# UCirKitBreadboardTop-08231908.net
KiCad netlist of a schematic drawn in EAGLE
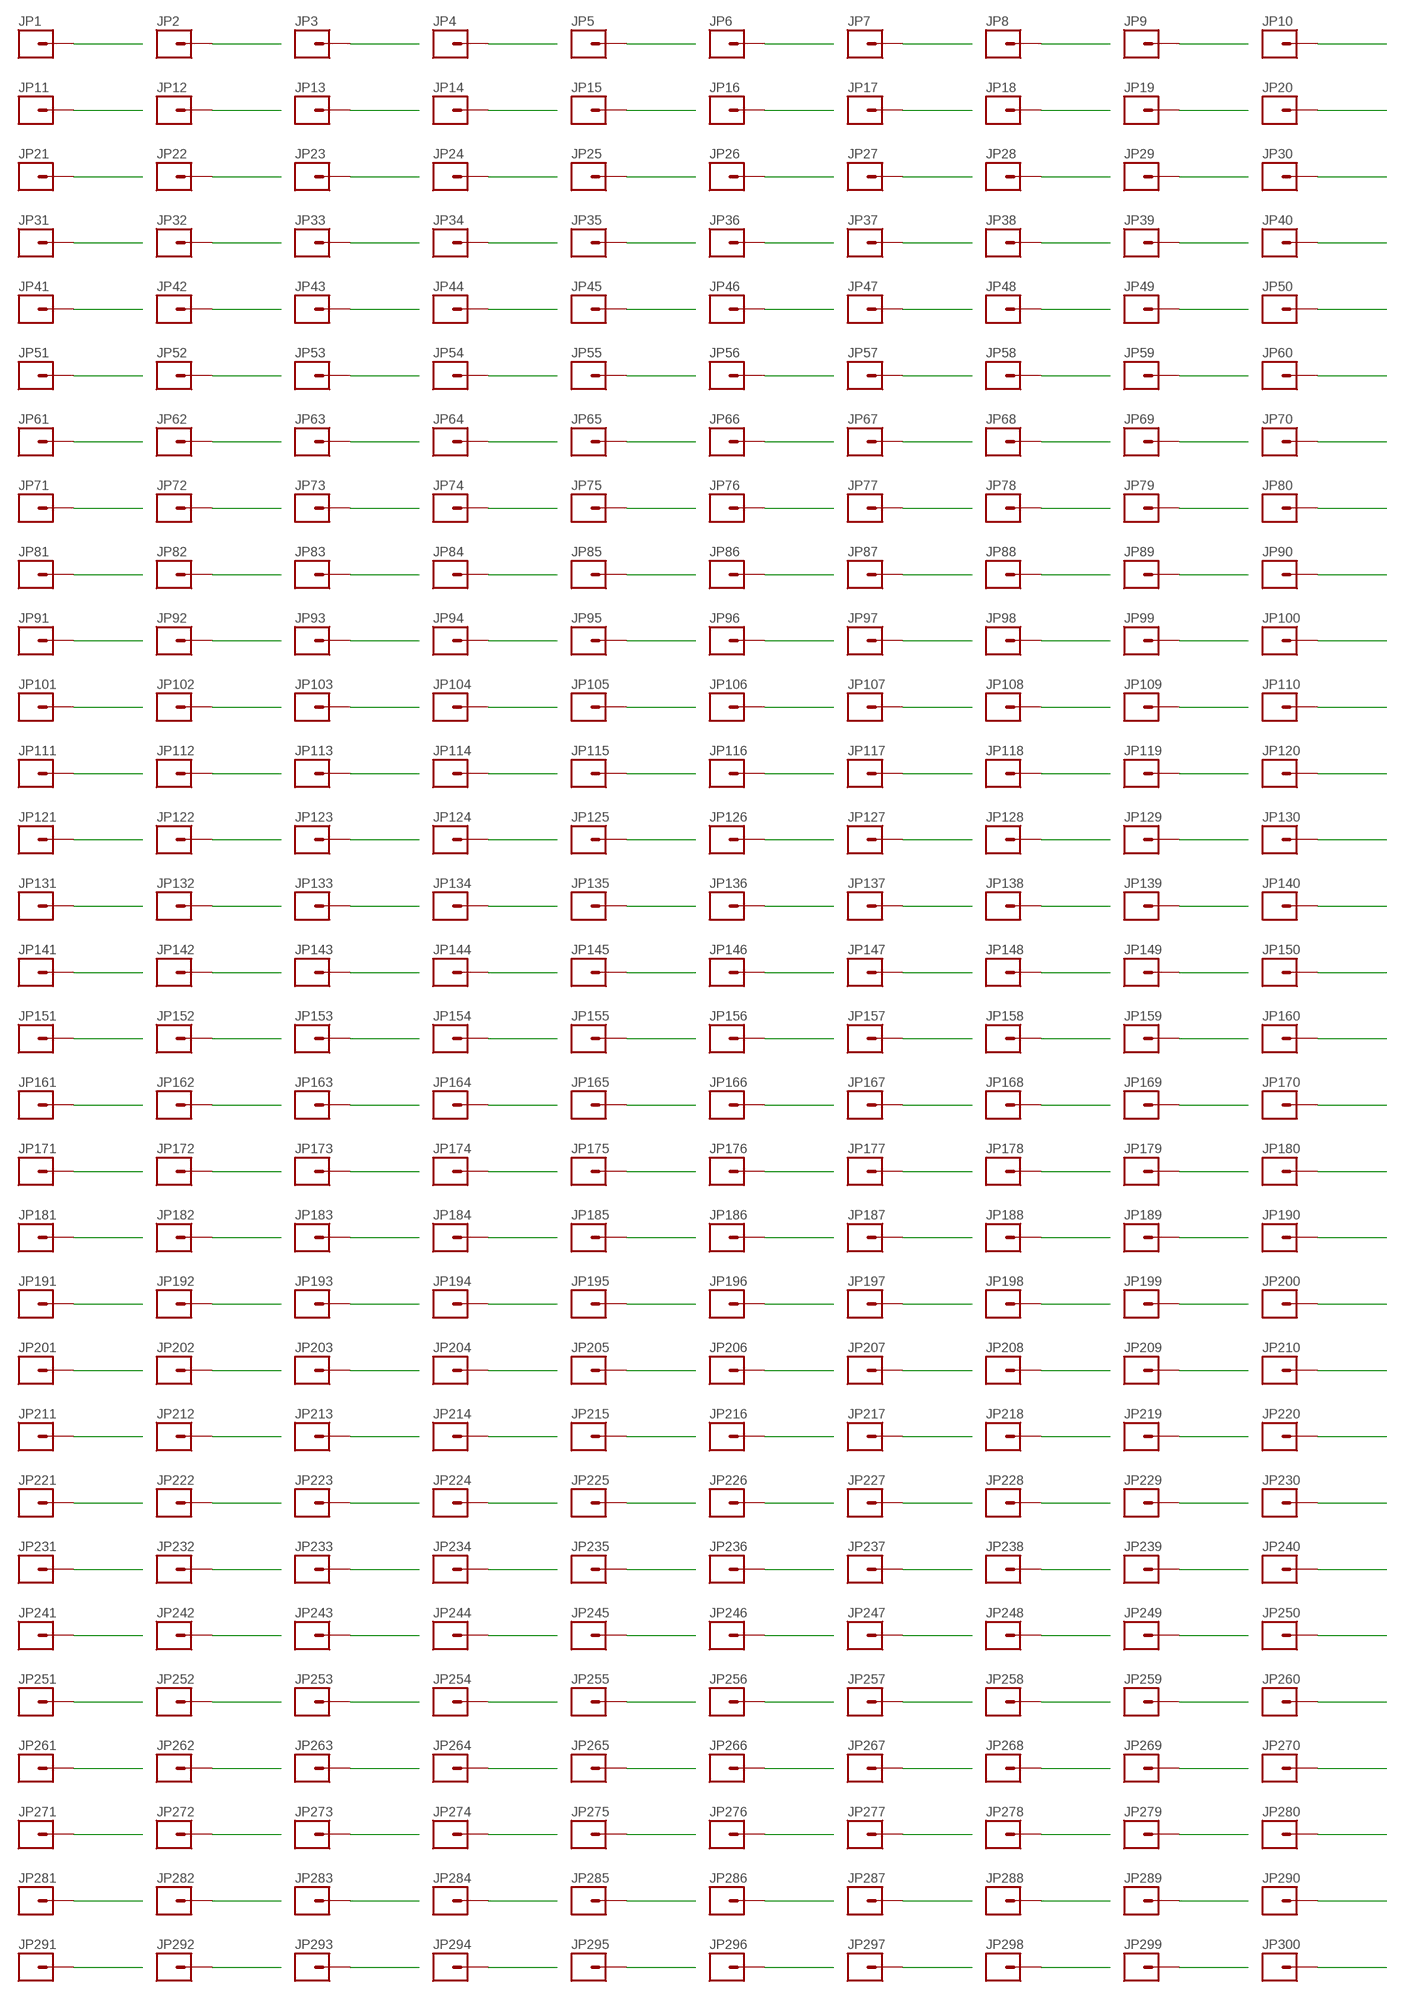
[diagram p0: schematic, sheet 1, part 1 of 2]
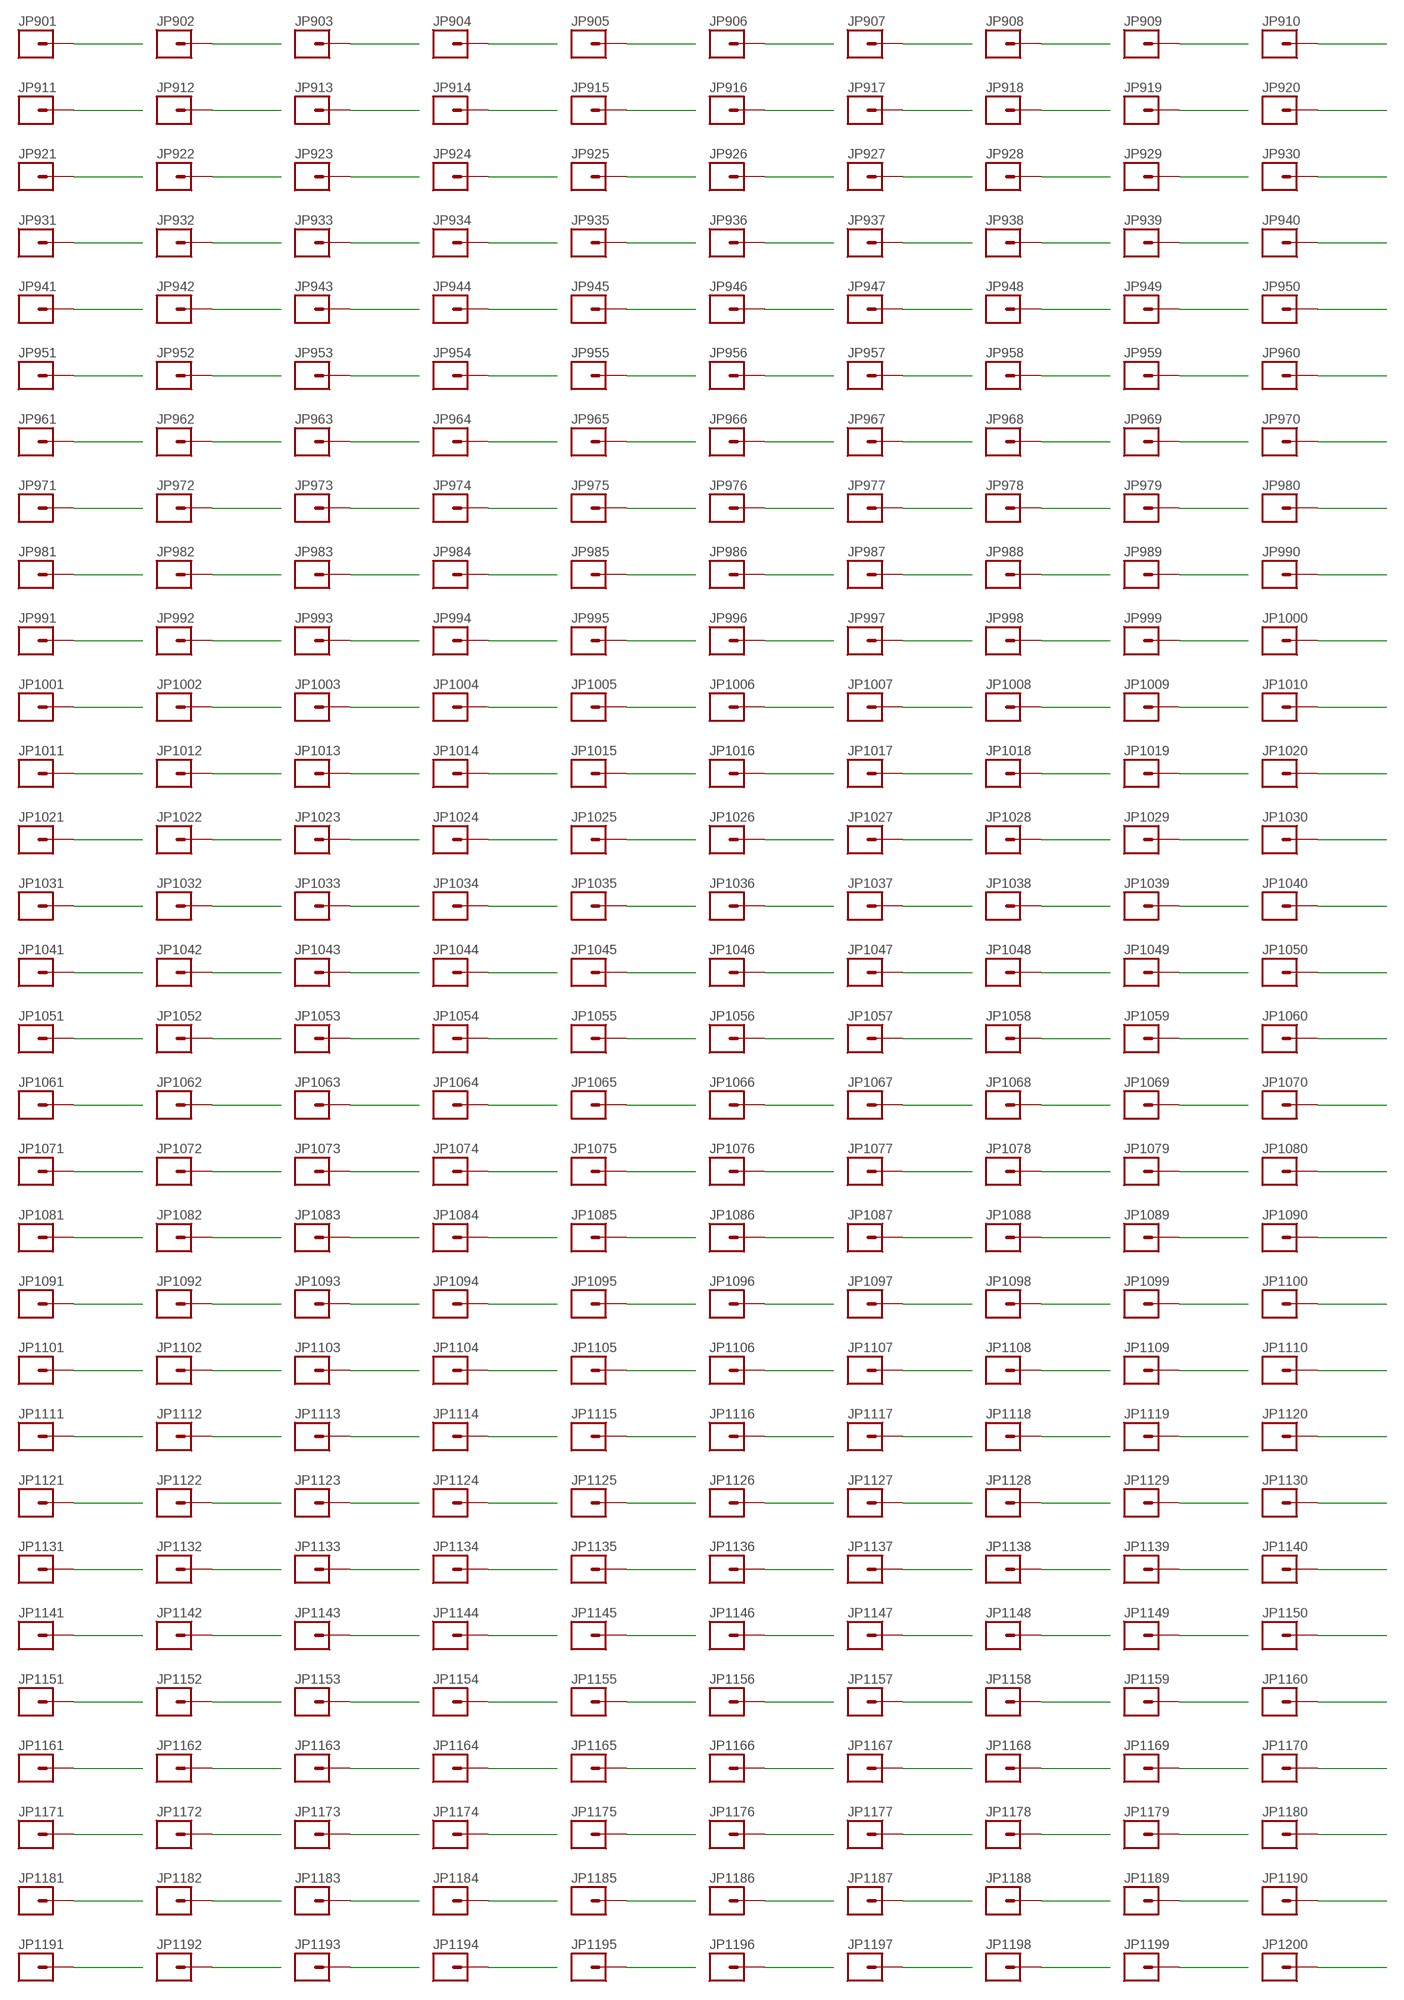
[diagram p1: schematic, sheet 1, part 2 of 2]

(export (version "E")
  (design (tool "Eeschema 10.0.6"))
  (components
    (comp (ref "JP1")
      (value "M01PTH_WITHOUT_TEXT")
      (footprint "eagle-import:1X01_WITHOUT_TEXT")
      (libsource (lib "eagle-import") (part "M01PTH_WITHOUT_TEXT"))
    )
    (comp (ref "JP2")
      (value "M01PTH_WITHOUT_TEXT")
      (footprint "eagle-import:1X01_WITHOUT_TEXT")
      (libsource (lib "eagle-import") (part "M01PTH_WITHOUT_TEXT"))
    )
    (comp (ref "JP3")
      (value "M01PTH_WITHOUT_TEXT")
      (footprint "eagle-import:1X01_WITHOUT_TEXT")
      (libsource (lib "eagle-import") (part "M01PTH_WITHOUT_TEXT"))
    )
    (comp (ref "JP4")
      (value "M01PTH_WITHOUT_TEXT")
      (footprint "eagle-import:1X01_WITHOUT_TEXT")
      (libsource (lib "eagle-import") (part "M01PTH_WITHOUT_TEXT"))
    )
    (comp (ref "JP5")
      (value "M01PTH_WITHOUT_TEXT")
      (footprint "eagle-import:1X01_WITHOUT_TEXT")
      (libsource (lib "eagle-import") (part "M01PTH_WITHOUT_TEXT"))
    )
    (comp (ref "JP6")
      (value "M01PTH_WITHOUT_TEXT")
      (footprint "eagle-import:1X01_WITHOUT_TEXT")
      (libsource (lib "eagle-import") (part "M01PTH_WITHOUT_TEXT"))
    )
    (comp (ref "JP7")
      (value "M01PTH_WITHOUT_TEXT")
      (footprint "eagle-import:1X01_WITHOUT_TEXT")
      (libsource (lib "eagle-import") (part "M01PTH_WITHOUT_TEXT"))
    )
    (comp (ref "JP8")
      (value "M01PTH_WITHOUT_TEXT")
      (footprint "eagle-import:1X01_WITHOUT_TEXT")
      (libsource (lib "eagle-import") (part "M01PTH_WITHOUT_TEXT"))
    )
    (comp (ref "JP9")
      (value "M01PTH_WITHOUT_TEXT")
      (footprint "eagle-import:1X01_WITHOUT_TEXT")
      (libsource (lib "eagle-import") (part "M01PTH_WITHOUT_TEXT"))
    )
    (comp (ref "JP10")
      (value "M01PTH_WITHOUT_TEXT")
      (footprint "eagle-import:1X01_WITHOUT_TEXT")
      (libsource (lib "eagle-import") (part "M01PTH_WITHOUT_TEXT"))
    )
    (comp (ref "JP11")
      (value "M01PTH_WITHOUT_TEXT")
      (footprint "eagle-import:1X01_WITHOUT_TEXT")
      (libsource (lib "eagle-import") (part "M01PTH_WITHOUT_TEXT"))
    )
    (comp (ref "JP12")
      (value "M01PTH_WITHOUT_TEXT")
      (footprint "eagle-import:1X01_WITHOUT_TEXT")
      (libsource (lib "eagle-import") (part "M01PTH_WITHOUT_TEXT"))
    )
    (comp (ref "JP13")
      (value "M01PTH_WITHOUT_TEXT")
      (footprint "eagle-import:1X01_WITHOUT_TEXT")
      (libsource (lib "eagle-import") (part "M01PTH_WITHOUT_TEXT"))
    )
    (comp (ref "JP14")
      (value "M01PTH_WITHOUT_TEXT")
      (footprint "eagle-import:1X01_WITHOUT_TEXT")
      (libsource (lib "eagle-import") (part "M01PTH_WITHOUT_TEXT"))
    )
    (comp (ref "JP15")
      (value "M01PTH_WITHOUT_TEXT")
      (footprint "eagle-import:1X01_WITHOUT_TEXT")
      (libsource (lib "eagle-import") (part "M01PTH_WITHOUT_TEXT"))
    )
    (comp (ref "JP16")
      (value "M01PTH_WITHOUT_TEXT")
      (footprint "eagle-import:1X01_WITHOUT_TEXT")
      (libsource (lib "eagle-import") (part "M01PTH_WITHOUT_TEXT"))
    )
    (comp (ref "JP17")
      (value "M01PTH_WITHOUT_TEXT")
      (footprint "eagle-import:1X01_WITHOUT_TEXT")
      (libsource (lib "eagle-import") (part "M01PTH_WITHOUT_TEXT"))
    )
    (comp (ref "JP18")
      (value "M01PTH_WITHOUT_TEXT")
      (footprint "eagle-import:1X01_WITHOUT_TEXT")
      (libsource (lib "eagle-import") (part "M01PTH_WITHOUT_TEXT"))
    )
    (comp (ref "JP19")
      (value "M01PTH_WITHOUT_TEXT")
      (footprint "eagle-import:1X01_WITHOUT_TEXT")
      (libsource (lib "eagle-import") (part "M01PTH_WITHOUT_TEXT"))
    )
    (comp (ref "JP20")
      (value "M01PTH_WITHOUT_TEXT")
      (footprint "eagle-import:1X01_WITHOUT_TEXT")
      (libsource (lib "eagle-import") (part "M01PTH_WITHOUT_TEXT"))
    )
    (comp (ref "JP21")
      (value "M01PTH_WITHOUT_TEXT")
      (footprint "eagle-import:1X01_WITHOUT_TEXT")
      (libsource (lib "eagle-import") (part "M01PTH_WITHOUT_TEXT"))
    )
    (comp (ref "JP22")
      (value "M01PTH_WITHOUT_TEXT")
      (footprint "eagle-import:1X01_WITHOUT_TEXT")
      (libsource (lib "eagle-import") (part "M01PTH_WITHOUT_TEXT"))
    )
    (comp (ref "JP23")
      (value "M01PTH_WITHOUT_TEXT")
      (footprint "eagle-import:1X01_WITHOUT_TEXT")
      (libsource (lib "eagle-import") (part "M01PTH_WITHOUT_TEXT"))
    )
    (comp (ref "JP24")
      (value "M01PTH_WITHOUT_TEXT")
      (footprint "eagle-import:1X01_WITHOUT_TEXT")
      (libsource (lib "eagle-import") (part "M01PTH_WITHOUT_TEXT"))
    )
    (comp (ref "JP25")
      (value "M01PTH_WITHOUT_TEXT")
      (footprint "eagle-import:1X01_WITHOUT_TEXT")
      (libsource (lib "eagle-import") (part "M01PTH_WITHOUT_TEXT"))
    )
    (comp (ref "JP26")
      (value "M01PTH_WITHOUT_TEXT")
      (footprint "eagle-import:1X01_WITHOUT_TEXT")
      (libsource (lib "eagle-import") (part "M01PTH_WITHOUT_TEXT"))
    )
    (comp (ref "JP27")
      (value "M01PTH_WITHOUT_TEXT")
      (footprint "eagle-import:1X01_WITHOUT_TEXT")
      (libsource (lib "eagle-import") (part "M01PTH_WITHOUT_TEXT"))
    )
    (comp (ref "JP28")
      (value "M01PTH_WITHOUT_TEXT")
      (footprint "eagle-import:1X01_WITHOUT_TEXT")
      (libsource (lib "eagle-import") (part "M01PTH_WITHOUT_TEXT"))
    )
    (comp (ref "JP29")
      (value "M01PTH_WITHOUT_TEXT")
      (footprint "eagle-import:1X01_WITHOUT_TEXT")
      (libsource (lib "eagle-import") (part "M01PTH_WITHOUT_TEXT"))
    )
    (comp (ref "JP30")
      (value "M01PTH_WITHOUT_TEXT")
      (footprint "eagle-import:1X01_WITHOUT_TEXT")
      (libsource (lib "eagle-import") (part "M01PTH_WITHOUT_TEXT"))
    )
    (comp (ref "JP31")
      (value "M01PTH_WITHOUT_TEXT")
      (footprint "eagle-import:1X01_WITHOUT_TEXT")
      (libsource (lib "eagle-import") (part "M01PTH_WITHOUT_TEXT"))
    )
    (comp (ref "JP32")
      (value "M01PTH_WITHOUT_TEXT")
      (footprint "eagle-import:1X01_WITHOUT_TEXT")
      (libsource (lib "eagle-import") (part "M01PTH_WITHOUT_TEXT"))
    )
    (comp (ref "JP33")
      (value "M01PTH_WITHOUT_TEXT")
      (footprint "eagle-import:1X01_WITHOUT_TEXT")
      (libsource (lib "eagle-import") (part "M01PTH_WITHOUT_TEXT"))
    )
    (comp (ref "JP34")
      (value "M01PTH_WITHOUT_TEXT")
      (footprint "eagle-import:1X01_WITHOUT_TEXT")
      (libsource (lib "eagle-import") (part "M01PTH_WITHOUT_TEXT"))
    )
    (comp (ref "JP35")
      (value "M01PTH_WITHOUT_TEXT")
      (footprint "eagle-import:1X01_WITHOUT_TEXT")
      (libsource (lib "eagle-import") (part "M01PTH_WITHOUT_TEXT"))
    )
    (comp (ref "JP36")
      (value "M01PTH_WITHOUT_TEXT")
      (footprint "eagle-import:1X01_WITHOUT_TEXT")
      (libsource (lib "eagle-import") (part "M01PTH_WITHOUT_TEXT"))
    )
    (comp (ref "JP37")
      (value "M01PTH_WITHOUT_TEXT")
      (footprint "eagle-import:1X01_WITHOUT_TEXT")
      (libsource (lib "eagle-import") (part "M01PTH_WITHOUT_TEXT"))
    )
    (comp (ref "JP38")
      (value "M01PTH_WITHOUT_TEXT")
      (footprint "eagle-import:1X01_WITHOUT_TEXT")
      (libsource (lib "eagle-import") (part "M01PTH_WITHOUT_TEXT"))
    )
    (comp (ref "JP39")
      (value "M01PTH_WITHOUT_TEXT")
      (footprint "eagle-import:1X01_WITHOUT_TEXT")
      (libsource (lib "eagle-import") (part "M01PTH_WITHOUT_TEXT"))
    )
    (comp (ref "JP40")
      (value "M01PTH_WITHOUT_TEXT")
      (footprint "eagle-import:1X01_WITHOUT_TEXT")
      (libsource (lib "eagle-import") (part "M01PTH_WITHOUT_TEXT"))
    )
    (comp (ref "JP41")
      (value "M01PTH_WITHOUT_TEXT")
      (footprint "eagle-import:1X01_WITHOUT_TEXT")
      (libsource (lib "eagle-import") (part "M01PTH_WITHOUT_TEXT"))
    )
    (comp (ref "JP42")
      (value "M01PTH_WITHOUT_TEXT")
      (footprint "eagle-import:1X01_WITHOUT_TEXT")
      (libsource (lib "eagle-import") (part "M01PTH_WITHOUT_TEXT"))
    )
    (comp (ref "JP43")
      (value "M01PTH_WITHOUT_TEXT")
      (footprint "eagle-import:1X01_WITHOUT_TEXT")
      (libsource (lib "eagle-import") (part "M01PTH_WITHOUT_TEXT"))
    )
    (comp (ref "JP44")
      (value "M01PTH_WITHOUT_TEXT")
      (footprint "eagle-import:1X01_WITHOUT_TEXT")
      (libsource (lib "eagle-import") (part "M01PTH_WITHOUT_TEXT"))
    )
    (comp (ref "JP45")
      (value "M01PTH_WITHOUT_TEXT")
      (footprint "eagle-import:1X01_WITHOUT_TEXT")
      (libsource (lib "eagle-import") (part "M01PTH_WITHOUT_TEXT"))
    )
    (comp (ref "JP46")
      (value "M01PTH_WITHOUT_TEXT")
      (footprint "eagle-import:1X01_WITHOUT_TEXT")
      (libsource (lib "eagle-import") (part "M01PTH_WITHOUT_TEXT"))
    )
    (comp (ref "JP47")
      (value "M01PTH_WITHOUT_TEXT")
      (footprint "eagle-import:1X01_WITHOUT_TEXT")
      (libsource (lib "eagle-import") (part "M01PTH_WITHOUT_TEXT"))
    )
    (comp (ref "JP48")
      (value "M01PTH_WITHOUT_TEXT")
      (footprint "eagle-import:1X01_WITHOUT_TEXT")
      (libsource (lib "eagle-import") (part "M01PTH_WITHOUT_TEXT"))
    )
    (comp (ref "JP49")
      (value "M01PTH_WITHOUT_TEXT")
      (footprint "eagle-import:1X01_WITHOUT_TEXT")
      (libsource (lib "eagle-import") (part "M01PTH_WITHOUT_TEXT"))
    )
    (comp (ref "JP50")
      (value "M01PTH_WITHOUT_TEXT")
      (footprint "eagle-import:1X01_WITHOUT_TEXT")
      (libsource (lib "eagle-import") (part "M01PTH_WITHOUT_TEXT"))
    )
    (comp (ref "JP51")
      (value "M01PTH_WITHOUT_TEXT")
      (footprint "eagle-import:1X01_WITHOUT_TEXT")
      (libsource (lib "eagle-import") (part "M01PTH_WITHOUT_TEXT"))
    )
    (comp (ref "JP52")
      (value "M01PTH_WITHOUT_TEXT")
      (footprint "eagle-import:1X01_WITHOUT_TEXT")
      (libsource (lib "eagle-import") (part "M01PTH_WITHOUT_TEXT"))
    )
    (comp (ref "JP53")
      (value "M01PTH_WITHOUT_TEXT")
      (footprint "eagle-import:1X01_WITHOUT_TEXT")
      (libsource (lib "eagle-import") (part "M01PTH_WITHOUT_TEXT"))
    )
    (comp (ref "JP54")
      (value "M01PTH_WITHOUT_TEXT")
      (footprint "eagle-import:1X01_WITHOUT_TEXT")
      (libsource (lib "eagle-import") (part "M01PTH_WITHOUT_TEXT"))
    )
    (comp (ref "JP55")
      (value "M01PTH_WITHOUT_TEXT")
      (footprint "eagle-import:1X01_WITHOUT_TEXT")
      (libsource (lib "eagle-import") (part "M01PTH_WITHOUT_TEXT"))
    )
    (comp (ref "JP56")
      (value "M01PTH_WITHOUT_TEXT")
      (footprint "eagle-import:1X01_WITHOUT_TEXT")
      (libsource (lib "eagle-import") (part "M01PTH_WITHOUT_TEXT"))
    )
    (comp (ref "JP57")
      (value "M01PTH_WITHOUT_TEXT")
      (footprint "eagle-import:1X01_WITHOUT_TEXT")
      (libsource (lib "eagle-import") (part "M01PTH_WITHOUT_TEXT"))
    )
    (comp (ref "JP58")
      (value "M01PTH_WITHOUT_TEXT")
      (footprint "eagle-import:1X01_WITHOUT_TEXT")
      (libsource (lib "eagle-import") (part "M01PTH_WITHOUT_TEXT"))
    )
    (comp (ref "JP59")
      (value "M01PTH_WITHOUT_TEXT")
      (footprint "eagle-import:1X01_WITHOUT_TEXT")
      (libsource (lib "eagle-import") (part "M01PTH_WITHOUT_TEXT"))
    )
    (comp (ref "JP60")
      (value "M01PTH_WITHOUT_TEXT")
      (footprint "eagle-import:1X01_WITHOUT_TEXT")
      (libsource (lib "eagle-import") (part "M01PTH_WITHOUT_TEXT"))
    )
    (comp (ref "JP61")
      (value "M01PTH_WITHOUT_TEXT")
      (footprint "eagle-import:1X01_WITHOUT_TEXT")
      (libsource (lib "eagle-import") (part "M01PTH_WITHOUT_TEXT"))
    )
    (comp (ref "JP62")
      (value "M01PTH_WITHOUT_TEXT")
      (footprint "eagle-import:1X01_WITHOUT_TEXT")
      (libsource (lib "eagle-import") (part "M01PTH_WITHOUT_TEXT"))
    )
    (comp (ref "JP63")
      (value "M01PTH_WITHOUT_TEXT")
      (footprint "eagle-import:1X01_WITHOUT_TEXT")
      (libsource (lib "eagle-import") (part "M01PTH_WITHOUT_TEXT"))
    )
    (comp (ref "JP64")
      (value "M01PTH_WITHOUT_TEXT")
      (footprint "eagle-import:1X01_WITHOUT_TEXT")
      (libsource (lib "eagle-import") (part "M01PTH_WITHOUT_TEXT"))
    )
    (comp (ref "JP65")
      (value "M01PTH_WITHOUT_TEXT")
      (footprint "eagle-import:1X01_WITHOUT_TEXT")
      (libsource (lib "eagle-import") (part "M01PTH_WITHOUT_TEXT"))
    )
    (comp (ref "JP66")
      (value "M01PTH_WITHOUT_TEXT")
      (footprint "eagle-import:1X01_WITHOUT_TEXT")
      (libsource (lib "eagle-import") (part "M01PTH_WITHOUT_TEXT"))
    )
    (comp (ref "JP67")
      (value "M01PTH_WITHOUT_TEXT")
      (footprint "eagle-import:1X01_WITHOUT_TEXT")
      (libsource (lib "eagle-import") (part "M01PTH_WITHOUT_TEXT"))
    )
    (comp (ref "JP68")
      (value "M01PTH_WITHOUT_TEXT")
      (footprint "eagle-import:1X01_WITHOUT_TEXT")
      (libsource (lib "eagle-import") (part "M01PTH_WITHOUT_TEXT"))
    )
    (comp (ref "JP69")
      (value "M01PTH_WITHOUT_TEXT")
      (footprint "eagle-import:1X01_WITHOUT_TEXT")
      (libsource (lib "eagle-import") (part "M01PTH_WITHOUT_TEXT"))
    )
    (comp (ref "JP70")
      (value "M01PTH_WITHOUT_TEXT")
      (footprint "eagle-import:1X01_WITHOUT_TEXT")
      (libsource (lib "eagle-import") (part "M01PTH_WITHOUT_TEXT"))
    )
    (comp (ref "JP71")
      (value "M01PTH_WITHOUT_TEXT")
      (footprint "eagle-import:1X01_WITHOUT_TEXT")
      (libsource (lib "eagle-import") (part "M01PTH_WITHOUT_TEXT"))
    )
    (comp (ref "JP72")
      (value "M01PTH_WITHOUT_TEXT")
      (footprint "eagle-import:1X01_WITHOUT_TEXT")
      (libsource (lib "eagle-import") (part "M01PTH_WITHOUT_TEXT"))
    )
    (comp (ref "JP73")
      (value "M01PTH_WITHOUT_TEXT")
      (footprint "eagle-import:1X01_WITHOUT_TEXT")
      (libsource (lib "eagle-import") (part "M01PTH_WITHOUT_TEXT"))
    )
    (comp (ref "JP74")
      (value "M01PTH_WITHOUT_TEXT")
      (footprint "eagle-import:1X01_WITHOUT_TEXT")
      (libsource (lib "eagle-import") (part "M01PTH_WITHOUT_TEXT"))
    )
    (comp (ref "JP75")
      (value "M01PTH_WITHOUT_TEXT")
      (footprint "eagle-import:1X01_WITHOUT_TEXT")
      (libsource (lib "eagle-import") (part "M01PTH_WITHOUT_TEXT"))
    )
    (comp (ref "JP76")
      (value "M01PTH_WITHOUT_TEXT")
      (footprint "eagle-import:1X01_WITHOUT_TEXT")
      (libsource (lib "eagle-import") (part "M01PTH_WITHOUT_TEXT"))
    )
    (comp (ref "JP77")
      (value "M01PTH_WITHOUT_TEXT")
      (footprint "eagle-import:1X01_WITHOUT_TEXT")
      (libsource (lib "eagle-import") (part "M01PTH_WITHOUT_TEXT"))
    )
    (comp (ref "JP78")
      (value "M01PTH_WITHOUT_TEXT")
      (footprint "eagle-import:1X01_WITHOUT_TEXT")
      (libsource (lib "eagle-import") (part "M01PTH_WITHOUT_TEXT"))
    )
    (comp (ref "JP79")
      (value "M01PTH_WITHOUT_TEXT")
      (footprint "eagle-import:1X01_WITHOUT_TEXT")
      (libsource (lib "eagle-import") (part "M01PTH_WITHOUT_TEXT"))
    )
    (comp (ref "JP80")
      (value "M01PTH_WITHOUT_TEXT")
      (footprint "eagle-import:1X01_WITHOUT_TEXT")
      (libsource (lib "eagle-import") (part "M01PTH_WITHOUT_TEXT"))
    )
    (comp (ref "JP81")
      (value "M01PTH_WITHOUT_TEXT")
      (footprint "eagle-import:1X01_WITHOUT_TEXT")
      (libsource (lib "eagle-import") (part "M01PTH_WITHOUT_TEXT"))
    )
    (comp (ref "JP82")
      (value "M01PTH_WITHOUT_TEXT")
      (footprint "eagle-import:1X01_WITHOUT_TEXT")
      (libsource (lib "eagle-import") (part "M01PTH_WITHOUT_TEXT"))
    )
    (comp (ref "JP83")
      (value "M01PTH_WITHOUT_TEXT")
      (footprint "eagle-import:1X01_WITHOUT_TEXT")
      (libsource (lib "eagle-import") (part "M01PTH_WITHOUT_TEXT"))
    )
    (comp (ref "JP84")
      (value "M01PTH_WITHOUT_TEXT")
      (footprint "eagle-import:1X01_WITHOUT_TEXT")
      (libsource (lib "eagle-import") (part "M01PTH_WITHOUT_TEXT"))
    )
    (comp (ref "JP85")
      (value "M01PTH_WITHOUT_TEXT")
      (footprint "eagle-import:1X01_WITHOUT_TEXT")
      (libsource (lib "eagle-import") (part "M01PTH_WITHOUT_TEXT"))
    )
    (comp (ref "JP86")
      (value "M01PTH_WITHOUT_TEXT")
      (footprint "eagle-import:1X01_WITHOUT_TEXT")
      (libsource (lib "eagle-import") (part "M01PTH_WITHOUT_TEXT"))
    )
    (comp (ref "JP87")
      (value "M01PTH_WITHOUT_TEXT")
      (footprint "eagle-import:1X01_WITHOUT_TEXT")
      (libsource (lib "eagle-import") (part "M01PTH_WITHOUT_TEXT"))
    )
    (comp (ref "JP88")
      (value "M01PTH_WITHOUT_TEXT")
      (footprint "eagle-import:1X01_WITHOUT_TEXT")
      (libsource (lib "eagle-import") (part "M01PTH_WITHOUT_TEXT"))
    )
    (comp (ref "JP89")
      (value "M01PTH_WITHOUT_TEXT")
      (footprint "eagle-import:1X01_WITHOUT_TEXT")
      (libsource (lib "eagle-import") (part "M01PTH_WITHOUT_TEXT"))
    )
    (comp (ref "JP90")
      (value "M01PTH_WITHOUT_TEXT")
      (footprint "eagle-import:1X01_WITHOUT_TEXT")
      (libsource (lib "eagle-import") (part "M01PTH_WITHOUT_TEXT"))
    )
    (comp (ref "JP91")
      (value "M01PTH_WITHOUT_TEXT")
      (footprint "eagle-import:1X01_WITHOUT_TEXT")
      (libsource (lib "eagle-import") (part "M01PTH_WITHOUT_TEXT"))
    )
    (comp (ref "JP92")
      (value "M01PTH_WITHOUT_TEXT")
      (footprint "eagle-import:1X01_WITHOUT_TEXT")
      (libsource (lib "eagle-import") (part "M01PTH_WITHOUT_TEXT"))
    )
    (comp (ref "JP93")
      (value "M01PTH_WITHOUT_TEXT")
      (footprint "eagle-import:1X01_WITHOUT_TEXT")
      (libsource (lib "eagle-import") (part "M01PTH_WITHOUT_TEXT"))
    )
    (comp (ref "JP94")
      (value "M01PTH_WITHOUT_TEXT")
      (footprint "eagle-import:1X01_WITHOUT_TEXT")
      (libsource (lib "eagle-import") (part "M01PTH_WITHOUT_TEXT"))
    )
    (comp (ref "JP95")
      (value "M01PTH_WITHOUT_TEXT")
      (footprint "eagle-import:1X01_WITHOUT_TEXT")
      (libsource (lib "eagle-import") (part "M01PTH_WITHOUT_TEXT"))
    )
    (comp (ref "JP96")
      (value "M01PTH_WITHOUT_TEXT")
      (footprint "eagle-import:1X01_WITHOUT_TEXT")
      (libsource (lib "eagle-import") (part "M01PTH_WITHOUT_TEXT"))
    )
    (comp (ref "JP97")
      (value "M01PTH_WITHOUT_TEXT")
      (footprint "eagle-import:1X01_WITHOUT_TEXT")
      (libsource (lib "eagle-import") (part "M01PTH_WITHOUT_TEXT"))
    )
    (comp (ref "JP98")
      (value "M01PTH_WITHOUT_TEXT")
      (footprint "eagle-import:1X01_WITHOUT_TEXT")
      (libsource (lib "eagle-import") (part "M01PTH_WITHOUT_TEXT"))
    )
    (comp (ref "JP99")
      (value "M01PTH_WITHOUT_TEXT")
      (footprint "eagle-import:1X01_WITHOUT_TEXT")
      (libsource (lib "eagle-import") (part "M01PTH_WITHOUT_TEXT"))
    )
    (comp (ref "JP100")
      (value "M01PTH_WITHOUT_TEXT")
      (footprint "eagle-import:1X01_WITHOUT_TEXT")
      (libsource (lib "eagle-import") (part "M01PTH_WITHOUT_TEXT"))
    )
    (comp (ref "JP101")
      (value "M01PTH_WITHOUT_TEXT")
      (footprint "eagle-import:1X01_WITHOUT_TEXT")
      (libsource (lib "eagle-import") (part "M01PTH_WITHOUT_TEXT"))
    )
    (comp (ref "JP102")
      (value "M01PTH_WITHOUT_TEXT")
      (footprint "eagle-import:1X01_WITHOUT_TEXT")
      (libsource (lib "eagle-import") (part "M01PTH_WITHOUT_TEXT"))
    )
    (comp (ref "JP103")
      (value "M01PTH_WITHOUT_TEXT")
      (footprint "eagle-import:1X01_WITHOUT_TEXT")
      (libsource (lib "eagle-import") (part "M01PTH_WITHOUT_TEXT"))
    )
    (comp (ref "JP104")
      (value "M01PTH_WITHOUT_TEXT")
      (footprint "eagle-import:1X01_WITHOUT_TEXT")
      (libsource (lib "eagle-import") (part "M01PTH_WITHOUT_TEXT"))
    )
    (comp (ref "JP105")
      (value "M01PTH_WITHOUT_TEXT")
      (footprint "eagle-import:1X01_WITHOUT_TEXT")
      (libsource (lib "eagle-import") (part "M01PTH_WITHOUT_TEXT"))
    )
    (comp (ref "JP106")
      (value "M01PTH_WITHOUT_TEXT")
      (footprint "eagle-import:1X01_WITHOUT_TEXT")
      (libsource (lib "eagle-import") (part "M01PTH_WITHOUT_TEXT"))
    )
    (comp (ref "JP107")
      (value "M01PTH_WITHOUT_TEXT")
      (footprint "eagle-import:1X01_WITHOUT_TEXT")
      (libsource (lib "eagle-import") (part "M01PTH_WITHOUT_TEXT"))
    )
    (comp (ref "JP108")
      (value "M01PTH_WITHOUT_TEXT")
      (footprint "eagle-import:1X01_WITHOUT_TEXT")
      (libsource (lib "eagle-import") (part "M01PTH_WITHOUT_TEXT"))
    )
    (comp (ref "JP109")
      (value "M01PTH_WITHOUT_TEXT")
      (footprint "eagle-import:1X01_WITHOUT_TEXT")
      (libsource (lib "eagle-import") (part "M01PTH_WITHOUT_TEXT"))
    )
    (comp (ref "JP110")
      (value "M01PTH_WITHOUT_TEXT")
      (footprint "eagle-import:1X01_WITHOUT_TEXT")
      (libsource (lib "eagle-import") (part "M01PTH_WITHOUT_TEXT"))
    )
    (comp (ref "JP111")
      (value "M01PTH_WITHOUT_TEXT")
      (footprint "eagle-import:1X01_WITHOUT_TEXT")
      (libsource (lib "eagle-import") (part "M01PTH_WITHOUT_TEXT"))
    )
    (comp (ref "JP112")
      (value "M01PTH_WITHOUT_TEXT")
      (footprint "eagle-import:1X01_WITHOUT_TEXT")
      (libsource (lib "eagle-import") (part "M01PTH_WITHOUT_TEXT"))
    )
    (comp (ref "JP113")
      (value "M01PTH_WITHOUT_TEXT")
      (footprint "eagle-import:1X01_WITHOUT_TEXT")
      (libsource (lib "eagle-import") (part "M01PTH_WITHOUT_TEXT"))
    )
    (comp (ref "JP114")
      (value "M01PTH_WITHOUT_TEXT")
      (footprint "eagle-import:1X01_WITHOUT_TEXT")
      (libsource (lib "eagle-import") (part "M01PTH_WITHOUT_TEXT"))
    )
    (comp (ref "JP115")
      (value "M01PTH_WITHOUT_TEXT")
      (footprint "eagle-import:1X01_WITHOUT_TEXT")
      (libsource (lib "eagle-import") (part "M01PTH_WITHOUT_TEXT"))
    )
    (comp (ref "JP116")
      (value "M01PTH_WITHOUT_TEXT")
      (footprint "eagle-import:1X01_WITHOUT_TEXT")
      (libsource (lib "eagle-import") (part "M01PTH_WITHOUT_TEXT"))
    )
    (comp (ref "JP117")
      (value "M01PTH_WITHOUT_TEXT")
      (footprint "eagle-import:1X01_WITHOUT_TEXT")
      (libsource (lib "eagle-import") (part "M01PTH_WITHOUT_TEXT"))
    )
    (comp (ref "JP118")
      (value "M01PTH_WITHOUT_TEXT")
      (footprint "eagle-import:1X01_WITHOUT_TEXT")
      (libsource (lib "eagle-import") (part "M01PTH_WITHOUT_TEXT"))
    )
    (comp (ref "JP119")
      (value "M01PTH_WITHOUT_TEXT")
      (footprint "eagle-import:1X01_WITHOUT_TEXT")
      (libsource (lib "eagle-import") (part "M01PTH_WITHOUT_TEXT"))
    )
    (comp (ref "JP120")
      (value "M01PTH_WITHOUT_TEXT")
      (footprint "eagle-import:1X01_WITHOUT_TEXT")
      (libsource (lib "eagle-import") (part "M01PTH_WITHOUT_TEXT"))
    )
    (comp (ref "JP121")
      (value "M01PTH_WITHOUT_TEXT")
      (footprint "eagle-import:1X01_WITHOUT_TEXT")
      (libsource (lib "eagle-import") (part "M01PTH_WITHOUT_TEXT"))
    )
    (comp (ref "JP122")
      (value "M01PTH_WITHOUT_TEXT")
      (footprint "eagle-import:1X01_WITHOUT_TEXT")
      (libsource (lib "eagle-import") (part "M01PTH_WITHOUT_TEXT"))
    )
    (comp (ref "JP123")
      (value "M01PTH_WITHOUT_TEXT")
      (footprint "eagle-import:1X01_WITHOUT_TEXT")
      (libsource (lib "eagle-import") (part "M01PTH_WITHOUT_TEXT"))
    )
    (comp (ref "JP124")
      (value "M01PTH_WITHOUT_TEXT")
      (footprint "eagle-import:1X01_WITHOUT_TEXT")
      (libsource (lib "eagle-import") (part "M01PTH_WITHOUT_TEXT"))
    )
    (comp (ref "JP125")
      (value "M01PTH_WITHOUT_TEXT")
      (footprint "eagle-import:1X01_WITHOUT_TEXT")
      (libsource (lib "eagle-import") (part "M01PTH_WITHOUT_TEXT"))
    )
    (comp (ref "JP126")
      (value "M01PTH_WITHOUT_TEXT")
      (footprint "eagle-import:1X01_WITHOUT_TEXT")
      (libsource (lib "eagle-import") (part "M01PTH_WITHOUT_TEXT"))
    )
    (comp (ref "JP127")
      (value "M01PTH_WITHOUT_TEXT")
      (footprint "eagle-import:1X01_WITHOUT_TEXT")
      (libsource (lib "eagle-import") (part "M01PTH_WITHOUT_TEXT"))
    )
    (comp (ref "JP128")
      (value "M01PTH_WITHOUT_TEXT")
      (footprint "eagle-import:1X01_WITHOUT_TEXT")
      (libsource (lib "eagle-import") (part "M01PTH_WITHOUT_TEXT"))
    )
    (comp (ref "JP129")
      (value "M01PTH_WITHOUT_TEXT")
      (footprint "eagle-import:1X01_WITHOUT_TEXT")
      (libsource (lib "eagle-import") (part "M01PTH_WITHOUT_TEXT"))
    )
    (comp (ref "JP130")
      (value "M01PTH_WITHOUT_TEXT")
      (footprint "eagle-import:1X01_WITHOUT_TEXT")
      (libsource (lib "eagle-import") (part "M01PTH_WITHOUT_TEXT"))
    )
    (comp (ref "JP131")
      (value "M01PTH_WITHOUT_TEXT")
      (footprint "eagle-import:1X01_WITHOUT_TEXT")
      (libsource (lib "eagle-import") (part "M01PTH_WITHOUT_TEXT"))
    )
    (comp (ref "JP132")
      (value "M01PTH_WITHOUT_TEXT")
      (footprint "eagle-import:1X01_WITHOUT_TEXT")
      (libsource (lib "eagle-import") (part "M01PTH_WITHOUT_TEXT"))
    )
    (comp (ref "JP133")
      (value "M01PTH_WITHOUT_TEXT")
      (footprint "eagle-import:1X01_WITHOUT_TEXT")
      (libsource (lib "eagle-import") (part "M01PTH_WITHOUT_TEXT"))
    )
    (comp (ref "JP134")
      (value "M01PTH_WITHOUT_TEXT")
      (footprint "eagle-import:1X01_WITHOUT_TEXT")
      (libsource (lib "eagle-import") (part "M01PTH_WITHOUT_TEXT"))
    )
    (comp (ref "JP135")
      (value "M01PTH_WITHOUT_TEXT")
      (footprint "eagle-import:1X01_WITHOUT_TEXT")
      (libsource (lib "eagle-import") (part "M01PTH_WITHOUT_TEXT"))
    )
    (comp (ref "JP136")
      (value "M01PTH_WITHOUT_TEXT")
      (footprint "eagle-import:1X01_WITHOUT_TEXT")
      (libsource (lib "eagle-import") (part "M01PTH_WITHOUT_TEXT"))
    )
    (comp (ref "JP137")
      (value "M01PTH_WITHOUT_TEXT")
      (footprint "eagle-import:1X01_WITHOUT_TEXT")
      (libsource (lib "eagle-import") (part "M01PTH_WITHOUT_TEXT"))
    )
    (comp (ref "JP138")
      (value "M01PTH_WITHOUT_TEXT")
      (footprint "eagle-import:1X01_WITHOUT_TEXT")
      (libsource (lib "eagle-import") (part "M01PTH_WITHOUT_TEXT"))
    )
    (comp (ref "JP139")
      (value "M01PTH_WITHOUT_TEXT")
      (footprint "eagle-import:1X01_WITHOUT_TEXT")
      (libsource (lib "eagle-import") (part "M01PTH_WITHOUT_TEXT"))
    )
    (comp (ref "JP140")
      (value "M01PTH_WITHOUT_TEXT")
      (footprint "eagle-import:1X01_WITHOUT_TEXT")
      (libsource (lib "eagle-import") (part "M01PTH_WITHOUT_TEXT"))
    )
    (comp (ref "JP141")
      (value "M01PTH_WITHOUT_TEXT")
      (footprint "eagle-import:1X01_WITHOUT_TEXT")
      (libsource (lib "eagle-import") (part "M01PTH_WITHOUT_TEXT"))
    )
    (comp (ref "JP142")
      (value "M01PTH_WITHOUT_TEXT")
      (footprint "eagle-import:1X01_WITHOUT_TEXT")
      (libsource (lib "eagle-import") (part "M01PTH_WITHOUT_TEXT"))
    )
    (comp (ref "JP143")
      (value "M01PTH_WITHOUT_TEXT")
      (footprint "eagle-import:1X01_WITHOUT_TEXT")
      (libsource (lib "eagle-import") (part "M01PTH_WITHOUT_TEXT"))
    )
    (comp (ref "JP144")
      (value "M01PTH_WITHOUT_TEXT")
      (footprint "eagle-import:1X01_WITHOUT_TEXT")
      (libsource (lib "eagle-import") (part "M01PTH_WITHOUT_TEXT"))
    )
    (comp (ref "JP145")
      (value "M01PTH_WITHOUT_TEXT")
      (footprint "eagle-import:1X01_WITHOUT_TEXT")
      (libsource (lib "eagle-import") (part "M01PTH_WITHOUT_TEXT"))
    )
    (comp (ref "JP146")
      (value "M01PTH_WITHOUT_TEXT")
      (footprint "eagle-import:1X01_WITHOUT_TEXT")
      (libsource (lib "eagle-import") (part "M01PTH_WITHOUT_TEXT"))
    )
    (comp (ref "JP147")
      (value "M01PTH_WITHOUT_TEXT")
      (footprint "eagle-import:1X01_WITHOUT_TEXT")
      (libsource (lib "eagle-import") (part "M01PTH_WITHOUT_TEXT"))
    )
    (comp (ref "JP148")
      (value "M01PTH_WITHOUT_TEXT")
      (footprint "eagle-import:1X01_WITHOUT_TEXT")
      (libsource (lib "eagle-import") (part "M01PTH_WITHOUT_TEXT"))
    )
    (comp (ref "JP149")
      (value "M01PTH_WITHOUT_TEXT")
      (footprint "eagle-import:1X01_WITHOUT_TEXT")
      (libsource (lib "eagle-import") (part "M01PTH_WITHOUT_TEXT"))
    )
    (comp (ref "JP150")
      (value "M01PTH_WITHOUT_TEXT")
      (footprint "eagle-import:1X01_WITHOUT_TEXT")
      (libsource (lib "eagle-import") (part "M01PTH_WITHOUT_TEXT"))
    )
    (comp (ref "JP151")
      (value "M01PTH_WITHOUT_TEXT")
      (footprint "eagle-import:1X01_WITHOUT_TEXT")
      (libsource (lib "eagle-import") (part "M01PTH_WITHOUT_TEXT"))
    )
    (comp (ref "JP152")
      (value "M01PTH_WITHOUT_TEXT")
      (footprint "eagle-import:1X01_WITHOUT_TEXT")
      (libsource (lib "eagle-import") (part "M01PTH_WITHOUT_TEXT"))
    )
    (comp (ref "JP153")
      (value "M01PTH_WITHOUT_TEXT")
      (footprint "eagle-import:1X01_WITHOUT_TEXT")
      (libsource (lib "eagle-import") (part "M01PTH_WITHOUT_TEXT"))
    )
    (comp (ref "JP154")
      (value "M01PTH_WITHOUT_TEXT")
      (footprint "eagle-import:1X01_WITHOUT_TEXT")
      (libsource (lib "eagle-import") (part "M01PTH_WITHOUT_TEXT"))
    )
    (comp (ref "JP155")
      (value "M01PTH_WITHOUT_TEXT")
      (footprint "eagle-import:1X01_WITHOUT_TEXT")
      (libsource (lib "eagle-import") (part "M01PTH_WITHOUT_TEXT"))
    )
    (comp (ref "JP156")
      (value "M01PTH_WITHOUT_TEXT")
      (footprint "eagle-import:1X01_WITHOUT_TEXT")
      (libsource (lib "eagle-import") (part "M01PTH_WITHOUT_TEXT"))
    )
    (comp (ref "JP157")
      (value "M01PTH_WITHOUT_TEXT")
      (footprint "eagle-import:1X01_WITHOUT_TEXT")
      (libsource (lib "eagle-import") (part "M01PTH_WITHOUT_TEXT"))
    )
    (comp (ref "JP158")
      (value "M01PTH_WITHOUT_TEXT")
      (footprint "eagle-import:1X01_WITHOUT_TEXT")
      (libsource (lib "eagle-import") (part "M01PTH_WITHOUT_TEXT"))
    )
    (comp (ref "JP159")
      (value "M01PTH_WITHOUT_TEXT")
      (footprint "eagle-import:1X01_WITHOUT_TEXT")
      (libsource (lib "eagle-import") (part "M01PTH_WITHOUT_TEXT"))
    )
    (comp (ref "JP160")
      (value "M01PTH_WITHOUT_TEXT")
      (footprint "eagle-import:1X01_WITHOUT_TEXT")
      (libsource (lib "eagle-import") (part "M01PTH_WITHOUT_TEXT"))
    )
    (comp (ref "JP161")
      (value "M01PTH_WITHOUT_TEXT")
      (footprint "eagle-import:1X01_WITHOUT_TEXT")
      (libsource (lib "eagle-import") (part "M01PTH_WITHOUT_TEXT"))
    )
    (comp (ref "JP162")
      (value "M01PTH_WITHOUT_TEXT")
      (footprint "eagle-import:1X01_WITHOUT_TEXT")
      (libsource (lib "eagle-import") (part "M01PTH_WITHOUT_TEXT"))
    )
    (comp (ref "JP163")
      (value "M01PTH_WITHOUT_TEXT")
      (footprint "eagle-import:1X01_WITHOUT_TEXT")
      (libsource (lib "eagle-import") (part "M01PTH_WITHOUT_TEXT"))
    )
    (comp (ref "JP164")
      (value "M01PTH_WITHOUT_TEXT")
      (footprint "eagle-import:1X01_WITHOUT_TEXT")
      (libsource (lib "eagle-import") (part "M01PTH_WITHOUT_TEXT"))
    )
    (comp (ref "JP165")
      (value "M01PTH_WITHOUT_TEXT")
      (footprint "eagle-import:1X01_WITHOUT_TEXT")
      (libsource (lib "eagle-import") (part "M01PTH_WITHOUT_TEXT"))
    )
    (comp (ref "JP166")
      (value "M01PTH_WITHOUT_TEXT")
      (footprint "eagle-import:1X01_WITHOUT_TEXT")
      (libsource (lib "eagle-import") (part "M01PTH_WITHOUT_TEXT"))
    )
    (comp (ref "JP167")
      (value "M01PTH_WITHOUT_TEXT")
      (footprint "eagle-import:1X01_WITHOUT_TEXT")
      (libsource (lib "eagle-import") (part "M01PTH_WITHOUT_TEXT"))
    )
    (comp (ref "JP168")
      (value "M01PTH_WITHOUT_TEXT")
      (footprint "eagle-import:1X01_WITHOUT_TEXT")
      (libsource (lib "eagle-import") (part "M01PTH_WITHOUT_TEXT"))
    )
    (comp (ref "JP169")
      (value "M01PTH_WITHOUT_TEXT")
      (footprint "eagle-import:1X01_WITHOUT_TEXT")
      (libsource (lib "eagle-import") (part "M01PTH_WITHOUT_TEXT"))
    )
    (comp (ref "JP170")
      (value "M01PTH_WITHOUT_TEXT")
      (footprint "eagle-import:1X01_WITHOUT_TEXT")
      (libsource (lib "eagle-import") (part "M01PTH_WITHOUT_TEXT"))
    )
    (comp (ref "JP171")
      (value "M01PTH_WITHOUT_TEXT")
      (footprint "eagle-import:1X01_WITHOUT_TEXT")
      (libsource (lib "eagle-import") (part "M01PTH_WITHOUT_TEXT"))
    )
    (comp (ref "JP172")
      (value "M01PTH_WITHOUT_TEXT")
      (footprint "eagle-import:1X01_WITHOUT_TEXT")
      (libsource (lib "eagle-import") (part "M01PTH_WITHOUT_TEXT"))
    )
    (comp (ref "JP173")
      (value "M01PTH_WITHOUT_TEXT")
      (footprint "eagle-import:1X01_WITHOUT_TEXT")
      (libsource (lib "eagle-import") (part "M01PTH_WITHOUT_TEXT"))
    )
    (comp (ref "JP174")
      (value "M01PTH_WITHOUT_TEXT")
      (footprint "eagle-import:1X01_WITHOUT_TEXT")
      (libsource (lib "eagle-import") (part "M01PTH_WITHOUT_TEXT"))
    )
    (comp (ref "JP175")
      (value "M01PTH_WITHOUT_TEXT")
      (footprint "eagle-import:1X01_WITHOUT_TEXT")
      (libsource (lib "eagle-import") (part "M01PTH_WITHOUT_TEXT"))
    )
    (comp (ref "JP176")
      (value "M01PTH_WITHOUT_TEXT")
      (footprint "eagle-import:1X01_WITHOUT_TEXT")
      (libsource (lib "eagle-import") (part "M01PTH_WITHOUT_TEXT"))
    )
    (comp (ref "JP177")
      (value "M01PTH_WITHOUT_TEXT")
      (footprint "eagle-import:1X01_WITHOUT_TEXT")
      (libsource (lib "eagle-import") (part "M01PTH_WITHOUT_TEXT"))
    )
    (comp (ref "JP178")
      (value "M01PTH_WITHOUT_TEXT")
      (footprint "eagle-import:1X01_WITHOUT_TEXT")
      (libsource (lib "eagle-import") (part "M01PTH_WITHOUT_TEXT"))
    )
    (comp (ref "JP179")
      (value "M01PTH_WITHOUT_TEXT")
      (footprint "eagle-import:1X01_WITHOUT_TEXT")
      (libsource (lib "eagle-import") (part "M01PTH_WITHOUT_TEXT"))
    )
    (comp (ref "JP180")
      (value "M01PTH_WITHOUT_TEXT")
      (footprint "eagle-import:1X01_WITHOUT_TEXT")
      (libsource (lib "eagle-import") (part "M01PTH_WITHOUT_TEXT"))
    )
    (comp (ref "JP181")
      (value "M01PTH_WITHOUT_TEXT")
      (footprint "eagle-import:1X01_WITHOUT_TEXT")
      (libsource (lib "eagle-import") (part "M01PTH_WITHOUT_TEXT"))
    )
    (comp (ref "JP182")
      (value "M01PTH_WITHOUT_TEXT")
      (footprint "eagle-import:1X01_WITHOUT_TEXT")
      (libsource (lib "eagle-import") (part "M01PTH_WITHOUT_TEXT"))
    )
    (comp (ref "JP183")
      (value "M01PTH_WITHOUT_TEXT")
      (footprint "eagle-import:1X01_WITHOUT_TEXT")
      (libsource (lib "eagle-import") (part "M01PTH_WITHOUT_TEXT"))
    )
    (comp (ref "JP184")
      (value "M01PTH_WITHOUT_TEXT")
      (footprint "eagle-import:1X01_WITHOUT_TEXT")
      (libsource (lib "eagle-import") (part "M01PTH_WITHOUT_TEXT"))
    )
    (comp (ref "JP185")
      (value "M01PTH_WITHOUT_TEXT")
      (footprint "eagle-import:1X01_WITHOUT_TEXT")
      (libsource (lib "eagle-import") (part "M01PTH_WITHOUT_TEXT"))
    )
    (comp (ref "JP186")
      (value "M01PTH_WITHOUT_TEXT")
      (footprint "eagle-import:1X01_WITHOUT_TEXT")
      (libsource (lib "eagle-import") (part "M01PTH_WITHOUT_TEXT"))
    )
    (comp (ref "JP187")
      (value "M01PTH_WITHOUT_TEXT")
      (footprint "eagle-import:1X01_WITHOUT_TEXT")
      (libsource (lib "eagle-import") (part "M01PTH_WITHOUT_TEXT"))
    )
    (comp (ref "JP188")
      (value "M01PTH_WITHOUT_TEXT")
      (footprint "eagle-import:1X01_WITHOUT_TEXT")
      (libsource (lib "eagle-import") (part "M01PTH_WITHOUT_TEXT"))
    )
    (comp (ref "JP189")
      (value "M01PTH_WITHOUT_TEXT")
      (footprint "eagle-import:1X01_WITHOUT_TEXT")
      (libsource (lib "eagle-import") (part "M01PTH_WITHOUT_TEXT"))
    )
    (comp (ref "JP190")
      (value "M01PTH_WITHOUT_TEXT")
      (footprint "eagle-import:1X01_WITHOUT_TEXT")
      (libsource (lib "eagle-import") (part "M01PTH_WITHOUT_TEXT"))
    )
    (comp (ref "JP191")
      (value "M01PTH_WITHOUT_TEXT")
      (footprint "eagle-import:1X01_WITHOUT_TEXT")
      (libsource (lib "eagle-import") (part "M01PTH_WITHOUT_TEXT"))
    )
    (comp (ref "JP192")
      (value "M01PTH_WITHOUT_TEXT")
      (footprint "eagle-import:1X01_WITHOUT_TEXT")
      (libsource (lib "eagle-import") (part "M01PTH_WITHOUT_TEXT"))
    )
    (comp (ref "JP193")
      (value "M01PTH_WITHOUT_TEXT")
      (footprint "eagle-import:1X01_WITHOUT_TEXT")
      (libsource (lib "eagle-import") (part "M01PTH_WITHOUT_TEXT"))
    )
    (comp (ref "JP194")
      (value "M01PTH_WITHOUT_TEXT")
      (footprint "eagle-import:1X01_WITHOUT_TEXT")
      (libsource (lib "eagle-import") (part "M01PTH_WITHOUT_TEXT"))
    )
    (comp (ref "JP195")
      (value "M01PTH_WITHOUT_TEXT")
      (footprint "eagle-import:1X01_WITHOUT_TEXT")
      (libsource (lib "eagle-import") (part "M01PTH_WITHOUT_TEXT"))
    )
    (comp (ref "JP196")
      (value "M01PTH_WITHOUT_TEXT")
      (footprint "eagle-import:1X01_WITHOUT_TEXT")
      (libsource (lib "eagle-import") (part "M01PTH_WITHOUT_TEXT"))
    )
    (comp (ref "JP197")
      (value "M01PTH_WITHOUT_TEXT")
      (footprint "eagle-import:1X01_WITHOUT_TEXT")
      (libsource (lib "eagle-import") (part "M01PTH_WITHOUT_TEXT"))
    )
    (comp (ref "JP198")
      (value "M01PTH_WITHOUT_TEXT")
      (footprint "eagle-import:1X01_WITHOUT_TEXT")
      (libsource (lib "eagle-import") (part "M01PTH_WITHOUT_TEXT"))
    )
    (comp (ref "JP199")
      (value "M01PTH_WITHOUT_TEXT")
      (footprint "eagle-import:1X01_WITHOUT_TEXT")
      (libsource (lib "eagle-import") (part "M01PTH_WITHOUT_TEXT"))
    )
    (comp (ref "JP200")
      (value "M01PTH_WITHOUT_TEXT")
      (footprint "eagle-import:1X01_WITHOUT_TEXT")
      (libsource (lib "eagle-import") (part "M01PTH_WITHOUT_TEXT"))
    )
    (comp (ref "JP201")
      (value "M01PTH_WITHOUT_TEXT")
      (footprint "eagle-import:1X01_WITHOUT_TEXT")
      (libsource (lib "eagle-import") (part "M01PTH_WITHOUT_TEXT"))
    )
    (comp (ref "JP202")
      (value "M01PTH_WITHOUT_TEXT")
      (footprint "eagle-import:1X01_WITHOUT_TEXT")
      (libsource (lib "eagle-import") (part "M01PTH_WITHOUT_TEXT"))
    )
    (comp (ref "JP203")
      (value "M01PTH_WITHOUT_TEXT")
      (footprint "eagle-import:1X01_WITHOUT_TEXT")
      (libsource (lib "eagle-import") (part "M01PTH_WITHOUT_TEXT"))
    )
    (comp (ref "JP204")
      (value "M01PTH_WITHOUT_TEXT")
      (footprint "eagle-import:1X01_WITHOUT_TEXT")
      (libsource (lib "eagle-import") (part "M01PTH_WITHOUT_TEXT"))
    )
    (comp (ref "JP205")
      (value "M01PTH_WITHOUT_TEXT")
      (footprint "eagle-import:1X01_WITHOUT_TEXT")
      (libsource (lib "eagle-import") (part "M01PTH_WITHOUT_TEXT"))
    )
    (comp (ref "JP206")
      (value "M01PTH_WITHOUT_TEXT")
      (footprint "eagle-import:1X01_WITHOUT_TEXT")
      (libsource (lib "eagle-import") (part "M01PTH_WITHOUT_TEXT"))
    )
    (comp (ref "JP207")
      (value "M01PTH_WITHOUT_TEXT")
      (footprint "eagle-import:1X01_WITHOUT_TEXT")
      (libsource (lib "eagle-import") (part "M01PTH_WITHOUT_TEXT"))
    )
    (comp (ref "JP208")
      (value "M01PTH_WITHOUT_TEXT")
      (footprint "eagle-import:1X01_WITHOUT_TEXT")
      (libsource (lib "eagle-import") (part "M01PTH_WITHOUT_TEXT"))
    )
    (comp (ref "JP209")
      (value "M01PTH_WITHOUT_TEXT")
      (footprint "eagle-import:1X01_WITHOUT_TEXT")
      (libsource (lib "eagle-import") (part "M01PTH_WITHOUT_TEXT"))
    )
    (comp (ref "JP210")
      (value "M01PTH_WITHOUT_TEXT")
      (footprint "eagle-import:1X01_WITHOUT_TEXT")
      (libsource (lib "eagle-import") (part "M01PTH_WITHOUT_TEXT"))
    )
    (comp (ref "JP211")
      (value "M01PTH_WITHOUT_TEXT")
      (footprint "eagle-import:1X01_WITHOUT_TEXT")
      (libsource (lib "eagle-import") (part "M01PTH_WITHOUT_TEXT"))
    )
    (comp (ref "JP212")
      (value "M01PTH_WITHOUT_TEXT")
      (footprint "eagle-import:1X01_WITHOUT_TEXT")
      (libsource (lib "eagle-import") (part "M01PTH_WITHOUT_TEXT"))
    )
    (comp (ref "JP213")
      (value "M01PTH_WITHOUT_TEXT")
      (footprint "eagle-import:1X01_WITHOUT_TEXT")
      (libsource (lib "eagle-import") (part "M01PTH_WITHOUT_TEXT"))
    )
    (comp (ref "JP214")
      (value "M01PTH_WITHOUT_TEXT")
      (footprint "eagle-import:1X01_WITHOUT_TEXT")
      (libsource (lib "eagle-import") (part "M01PTH_WITHOUT_TEXT"))
    )
    (comp (ref "JP215")
      (value "M01PTH_WITHOUT_TEXT")
      (footprint "eagle-import:1X01_WITHOUT_TEXT")
      (libsource (lib "eagle-import") (part "M01PTH_WITHOUT_TEXT"))
    )
    (comp (ref "JP216")
      (value "M01PTH_WITHOUT_TEXT")
      (footprint "eagle-import:1X01_WITHOUT_TEXT")
      (libsource (lib "eagle-import") (part "M01PTH_WITHOUT_TEXT"))
    )
    (comp (ref "JP217")
      (value "M01PTH_WITHOUT_TEXT")
      (footprint "eagle-import:1X01_WITHOUT_TEXT")
      (libsource (lib "eagle-import") (part "M01PTH_WITHOUT_TEXT"))
    )
    (comp (ref "JP218")
      (value "M01PTH_WITHOUT_TEXT")
      (footprint "eagle-import:1X01_WITHOUT_TEXT")
      (libsource (lib "eagle-import") (part "M01PTH_WITHOUT_TEXT"))
    )
    (comp (ref "JP219")
      (value "M01PTH_WITHOUT_TEXT")
      (footprint "eagle-import:1X01_WITHOUT_TEXT")
      (libsource (lib "eagle-import") (part "M01PTH_WITHOUT_TEXT"))
    )
    (comp (ref "JP220")
      (value "M01PTH_WITHOUT_TEXT")
      (footprint "eagle-import:1X01_WITHOUT_TEXT")
      (libsource (lib "eagle-import") (part "M01PTH_WITHOUT_TEXT"))
    )
    (comp (ref "JP221")
      (value "M01PTH_WITHOUT_TEXT")
      (footprint "eagle-import:1X01_WITHOUT_TEXT")
      (libsource (lib "eagle-import") (part "M01PTH_WITHOUT_TEXT"))
    )
    (comp (ref "JP222")
      (value "M01PTH_WITHOUT_TEXT")
      (footprint "eagle-import:1X01_WITHOUT_TEXT")
      (libsource (lib "eagle-import") (part "M01PTH_WITHOUT_TEXT"))
    )
    (comp (ref "JP223")
      (value "M01PTH_WITHOUT_TEXT")
      (footprint "eagle-import:1X01_WITHOUT_TEXT")
      (libsource (lib "eagle-import") (part "M01PTH_WITHOUT_TEXT"))
    )
    (comp (ref "JP224")
      (value "M01PTH_WITHOUT_TEXT")
      (footprint "eagle-import:1X01_WITHOUT_TEXT")
      (libsource (lib "eagle-import") (part "M01PTH_WITHOUT_TEXT"))
    )
    (comp (ref "JP225")
      (value "M01PTH_WITHOUT_TEXT")
      (footprint "eagle-import:1X01_WITHOUT_TEXT")
      (libsource (lib "eagle-import") (part "M01PTH_WITHOUT_TEXT"))
    )
    (comp (ref "JP226")
      (value "M01PTH_WITHOUT_TEXT")
      (footprint "eagle-import:1X01_WITHOUT_TEXT")
      (libsource (lib "eagle-import") (part "M01PTH_WITHOUT_TEXT"))
    )
    (comp (ref "JP227")
      (value "M01PTH_WITHOUT_TEXT")
      (footprint "eagle-import:1X01_WITHOUT_TEXT")
      (libsource (lib "eagle-import") (part "M01PTH_WITHOUT_TEXT"))
    )
    (comp (ref "JP228")
      (value "M01PTH_WITHOUT_TEXT")
      (footprint "eagle-import:1X01_WITHOUT_TEXT")
      (libsource (lib "eagle-import") (part "M01PTH_WITHOUT_TEXT"))
    )
    (comp (ref "JP229")
      (value "M01PTH_WITHOUT_TEXT")
      (footprint "eagle-import:1X01_WITHOUT_TEXT")
      (libsource (lib "eagle-import") (part "M01PTH_WITHOUT_TEXT"))
    )
    (comp (ref "JP230")
      (value "M01PTH_WITHOUT_TEXT")
      (footprint "eagle-import:1X01_WITHOUT_TEXT")
      (libsource (lib "eagle-import") (part "M01PTH_WITHOUT_TEXT"))
    )
    (comp (ref "JP231")
      (value "M01PTH_WITHOUT_TEXT")
      (footprint "eagle-import:1X01_WITHOUT_TEXT")
      (libsource (lib "eagle-import") (part "M01PTH_WITHOUT_TEXT"))
    )
    (comp (ref "JP232")
      (value "M01PTH_WITHOUT_TEXT")
      (footprint "eagle-import:1X01_WITHOUT_TEXT")
      (libsource (lib "eagle-import") (part "M01PTH_WITHOUT_TEXT"))
    )
    (comp (ref "JP233")
      (value "M01PTH_WITHOUT_TEXT")
      (footprint "eagle-import:1X01_WITHOUT_TEXT")
      (libsource (lib "eagle-import") (part "M01PTH_WITHOUT_TEXT"))
    )
    (comp (ref "JP234")
      (value "M01PTH_WITHOUT_TEXT")
      (footprint "eagle-import:1X01_WITHOUT_TEXT")
      (libsource (lib "eagle-import") (part "M01PTH_WITHOUT_TEXT"))
    )
    (comp (ref "JP235")
      (value "M01PTH_WITHOUT_TEXT")
      (footprint "eagle-import:1X01_WITHOUT_TEXT")
      (libsource (lib "eagle-import") (part "M01PTH_WITHOUT_TEXT"))
    )
    (comp (ref "JP236")
      (value "M01PTH_WITHOUT_TEXT")
      (footprint "eagle-import:1X01_WITHOUT_TEXT")
      (libsource (lib "eagle-import") (part "M01PTH_WITHOUT_TEXT"))
    )
    (comp (ref "JP237")
      (value "M01PTH_WITHOUT_TEXT")
      (footprint "eagle-import:1X01_WITHOUT_TEXT")
      (libsource (lib "eagle-import") (part "M01PTH_WITHOUT_TEXT"))
    )
    (comp (ref "JP238")
      (value "M01PTH_WITHOUT_TEXT")
      (footprint "eagle-import:1X01_WITHOUT_TEXT")
      (libsource (lib "eagle-import") (part "M01PTH_WITHOUT_TEXT"))
    )
    (comp (ref "JP239")
      (value "M01PTH_WITHOUT_TEXT")
      (footprint "eagle-import:1X01_WITHOUT_TEXT")
      (libsource (lib "eagle-import") (part "M01PTH_WITHOUT_TEXT"))
    )
    (comp (ref "JP240")
      (value "M01PTH_WITHOUT_TEXT")
      (footprint "eagle-import:1X01_WITHOUT_TEXT")
      (libsource (lib "eagle-import") (part "M01PTH_WITHOUT_TEXT"))
    )
    (comp (ref "JP241")
      (value "M01PTH_WITHOUT_TEXT")
      (footprint "eagle-import:1X01_WITHOUT_TEXT")
      (libsource (lib "eagle-import") (part "M01PTH_WITHOUT_TEXT"))
    )
    (comp (ref "JP242")
      (value "M01PTH_WITHOUT_TEXT")
      (footprint "eagle-import:1X01_WITHOUT_TEXT")
      (libsource (lib "eagle-import") (part "M01PTH_WITHOUT_TEXT"))
    )
    (comp (ref "JP243")
      (value "M01PTH_WITHOUT_TEXT")
      (footprint "eagle-import:1X01_WITHOUT_TEXT")
      (libsource (lib "eagle-import") (part "M01PTH_WITHOUT_TEXT"))
    )
    (comp (ref "JP244")
      (value "M01PTH_WITHOUT_TEXT")
      (footprint "eagle-import:1X01_WITHOUT_TEXT")
      (libsource (lib "eagle-import") (part "M01PTH_WITHOUT_TEXT"))
    )
    (comp (ref "JP245")
      (value "M01PTH_WITHOUT_TEXT")
      (footprint "eagle-import:1X01_WITHOUT_TEXT")
      (libsource (lib "eagle-import") (part "M01PTH_WITHOUT_TEXT"))
    )
    (comp (ref "JP246")
      (value "M01PTH_WITHOUT_TEXT")
      (footprint "eagle-import:1X01_WITHOUT_TEXT")
      (libsource (lib "eagle-import") (part "M01PTH_WITHOUT_TEXT"))
    )
    (comp (ref "JP247")
      (value "M01PTH_WITHOUT_TEXT")
      (footprint "eagle-import:1X01_WITHOUT_TEXT")
      (libsource (lib "eagle-import") (part "M01PTH_WITHOUT_TEXT"))
    )
    (comp (ref "JP248")
      (value "M01PTH_WITHOUT_TEXT")
      (footprint "eagle-import:1X01_WITHOUT_TEXT")
      (libsource (lib "eagle-import") (part "M01PTH_WITHOUT_TEXT"))
    )
    (comp (ref "JP249")
      (value "M01PTH_WITHOUT_TEXT")
      (footprint "eagle-import:1X01_WITHOUT_TEXT")
      (libsource (lib "eagle-import") (part "M01PTH_WITHOUT_TEXT"))
    )
    (comp (ref "JP250")
      (value "M01PTH_WITHOUT_TEXT")
      (footprint "eagle-import:1X01_WITHOUT_TEXT")
      (libsource (lib "eagle-import") (part "M01PTH_WITHOUT_TEXT"))
    )
    (comp (ref "JP251")
      (value "M01PTH_WITHOUT_TEXT")
      (footprint "eagle-import:1X01_WITHOUT_TEXT")
      (libsource (lib "eagle-import") (part "M01PTH_WITHOUT_TEXT"))
    )
    (comp (ref "JP252")
      (value "M01PTH_WITHOUT_TEXT")
      (footprint "eagle-import:1X01_WITHOUT_TEXT")
      (libsource (lib "eagle-import") (part "M01PTH_WITHOUT_TEXT"))
    )
    (comp (ref "JP253")
      (value "M01PTH_WITHOUT_TEXT")
      (footprint "eagle-import:1X01_WITHOUT_TEXT")
      (libsource (lib "eagle-import") (part "M01PTH_WITHOUT_TEXT"))
    )
    (comp (ref "JP254")
      (value "M01PTH_WITHOUT_TEXT")
      (footprint "eagle-import:1X01_WITHOUT_TEXT")
      (libsource (lib "eagle-import") (part "M01PTH_WITHOUT_TEXT"))
    )
    (comp (ref "JP255")
      (value "M01PTH_WITHOUT_TEXT")
      (footprint "eagle-import:1X01_WITHOUT_TEXT")
      (libsource (lib "eagle-import") (part "M01PTH_WITHOUT_TEXT"))
    )
    (comp (ref "JP256")
      (value "M01PTH_WITHOUT_TEXT")
      (footprint "eagle-import:1X01_WITHOUT_TEXT")
      (libsource (lib "eagle-import") (part "M01PTH_WITHOUT_TEXT"))
    )
    (comp (ref "JP257")
      (value "M01PTH_WITHOUT_TEXT")
      (footprint "eagle-import:1X01_WITHOUT_TEXT")
      (libsource (lib "eagle-import") (part "M01PTH_WITHOUT_TEXT"))
    )
    (comp (ref "JP258")
      (value "M01PTH_WITHOUT_TEXT")
      (footprint "eagle-import:1X01_WITHOUT_TEXT")
      (libsource (lib "eagle-import") (part "M01PTH_WITHOUT_TEXT"))
    )
    (comp (ref "JP259")
      (value "M01PTH_WITHOUT_TEXT")
      (footprint "eagle-import:1X01_WITHOUT_TEXT")
      (libsource (lib "eagle-import") (part "M01PTH_WITHOUT_TEXT"))
    )
    (comp (ref "JP260")
      (value "M01PTH_WITHOUT_TEXT")
      (footprint "eagle-import:1X01_WITHOUT_TEXT")
      (libsource (lib "eagle-import") (part "M01PTH_WITHOUT_TEXT"))
    )
    (comp (ref "JP261")
      (value "M01PTH_WITHOUT_TEXT")
      (footprint "eagle-import:1X01_WITHOUT_TEXT")
      (libsource (lib "eagle-import") (part "M01PTH_WITHOUT_TEXT"))
    )
    (comp (ref "JP262")
      (value "M01PTH_WITHOUT_TEXT")
      (footprint "eagle-import:1X01_WITHOUT_TEXT")
      (libsource (lib "eagle-import") (part "M01PTH_WITHOUT_TEXT"))
    )
    (comp (ref "JP263")
      (value "M01PTH_WITHOUT_TEXT")
      (footprint "eagle-import:1X01_WITHOUT_TEXT")
      (libsource (lib "eagle-import") (part "M01PTH_WITHOUT_TEXT"))
    )
    (comp (ref "JP264")
      (value "M01PTH_WITHOUT_TEXT")
      (footprint "eagle-import:1X01_WITHOUT_TEXT")
      (libsource (lib "eagle-import") (part "M01PTH_WITHOUT_TEXT"))
    )
    (comp (ref "JP265")
      (value "M01PTH_WITHOUT_TEXT")
      (footprint "eagle-import:1X01_WITHOUT_TEXT")
      (libsource (lib "eagle-import") (part "M01PTH_WITHOUT_TEXT"))
    )
    (comp (ref "JP266")
      (value "M01PTH_WITHOUT_TEXT")
      (footprint "eagle-import:1X01_WITHOUT_TEXT")
      (libsource (lib "eagle-import") (part "M01PTH_WITHOUT_TEXT"))
    )
    (comp (ref "JP267")
      (value "M01PTH_WITHOUT_TEXT")
      (footprint "eagle-import:1X01_WITHOUT_TEXT")
      (libsource (lib "eagle-import") (part "M01PTH_WITHOUT_TEXT"))
    )
    (comp (ref "JP268")
      (value "M01PTH_WITHOUT_TEXT")
      (footprint "eagle-import:1X01_WITHOUT_TEXT")
      (libsource (lib "eagle-import") (part "M01PTH_WITHOUT_TEXT"))
    )
    (comp (ref "JP269")
      (value "M01PTH_WITHOUT_TEXT")
      (footprint "eagle-import:1X01_WITHOUT_TEXT")
      (libsource (lib "eagle-import") (part "M01PTH_WITHOUT_TEXT"))
    )
    (comp (ref "JP270")
      (value "M01PTH_WITHOUT_TEXT")
      (footprint "eagle-import:1X01_WITHOUT_TEXT")
      (libsource (lib "eagle-import") (part "M01PTH_WITHOUT_TEXT"))
    )
    (comp (ref "JP271")
      (value "M01PTH_WITHOUT_TEXT")
      (footprint "eagle-import:1X01_WITHOUT_TEXT")
      (libsource (lib "eagle-import") (part "M01PTH_WITHOUT_TEXT"))
    )
    (comp (ref "JP272")
      (value "M01PTH_WITHOUT_TEXT")
      (footprint "eagle-import:1X01_WITHOUT_TEXT")
      (libsource (lib "eagle-import") (part "M01PTH_WITHOUT_TEXT"))
    )
    (comp (ref "JP273")
      (value "M01PTH_WITHOUT_TEXT")
      (footprint "eagle-import:1X01_WITHOUT_TEXT")
      (libsource (lib "eagle-import") (part "M01PTH_WITHOUT_TEXT"))
    )
    (comp (ref "JP274")
      (value "M01PTH_WITHOUT_TEXT")
      (footprint "eagle-import:1X01_WITHOUT_TEXT")
      (libsource (lib "eagle-import") (part "M01PTH_WITHOUT_TEXT"))
    )
    (comp (ref "JP275")
      (value "M01PTH_WITHOUT_TEXT")
      (footprint "eagle-import:1X01_WITHOUT_TEXT")
      (libsource (lib "eagle-import") (part "M01PTH_WITHOUT_TEXT"))
    )
    (comp (ref "JP276")
      (value "M01PTH_WITHOUT_TEXT")
      (footprint "eagle-import:1X01_WITHOUT_TEXT")
      (libsource (lib "eagle-import") (part "M01PTH_WITHOUT_TEXT"))
    )
    (comp (ref "JP277")
      (value "M01PTH_WITHOUT_TEXT")
      (footprint "eagle-import:1X01_WITHOUT_TEXT")
      (libsource (lib "eagle-import") (part "M01PTH_WITHOUT_TEXT"))
    )
    (comp (ref "JP278")
      (value "M01PTH_WITHOUT_TEXT")
      (footprint "eagle-import:1X01_WITHOUT_TEXT")
      (libsource (lib "eagle-import") (part "M01PTH_WITHOUT_TEXT"))
    )
    (comp (ref "JP279")
      (value "M01PTH_WITHOUT_TEXT")
      (footprint "eagle-import:1X01_WITHOUT_TEXT")
      (libsource (lib "eagle-import") (part "M01PTH_WITHOUT_TEXT"))
    )
    (comp (ref "JP280")
      (value "M01PTH_WITHOUT_TEXT")
      (footprint "eagle-import:1X01_WITHOUT_TEXT")
      (libsource (lib "eagle-import") (part "M01PTH_WITHOUT_TEXT"))
    )
    (comp (ref "JP281")
      (value "M01PTH_WITHOUT_TEXT")
      (footprint "eagle-import:1X01_WITHOUT_TEXT")
      (libsource (lib "eagle-import") (part "M01PTH_WITHOUT_TEXT"))
    )
    (comp (ref "JP282")
      (value "M01PTH_WITHOUT_TEXT")
      (footprint "eagle-import:1X01_WITHOUT_TEXT")
      (libsource (lib "eagle-import") (part "M01PTH_WITHOUT_TEXT"))
    )
    (comp (ref "JP283")
      (value "M01PTH_WITHOUT_TEXT")
      (footprint "eagle-import:1X01_WITHOUT_TEXT")
      (libsource (lib "eagle-import") (part "M01PTH_WITHOUT_TEXT"))
    )
    (comp (ref "JP284")
      (value "M01PTH_WITHOUT_TEXT")
      (footprint "eagle-import:1X01_WITHOUT_TEXT")
      (libsource (lib "eagle-import") (part "M01PTH_WITHOUT_TEXT"))
    )
    (comp (ref "JP285")
      (value "M01PTH_WITHOUT_TEXT")
      (footprint "eagle-import:1X01_WITHOUT_TEXT")
      (libsource (lib "eagle-import") (part "M01PTH_WITHOUT_TEXT"))
    )
    (comp (ref "JP286")
      (value "M01PTH_WITHOUT_TEXT")
      (footprint "eagle-import:1X01_WITHOUT_TEXT")
      (libsource (lib "eagle-import") (part "M01PTH_WITHOUT_TEXT"))
    )
    (comp (ref "JP287")
      (value "M01PTH_WITHOUT_TEXT")
      (footprint "eagle-import:1X01_WITHOUT_TEXT")
      (libsource (lib "eagle-import") (part "M01PTH_WITHOUT_TEXT"))
    )
    (comp (ref "JP288")
      (value "M01PTH_WITHOUT_TEXT")
      (footprint "eagle-import:1X01_WITHOUT_TEXT")
      (libsource (lib "eagle-import") (part "M01PTH_WITHOUT_TEXT"))
    )
    (comp (ref "JP289")
      (value "M01PTH_WITHOUT_TEXT")
      (footprint "eagle-import:1X01_WITHOUT_TEXT")
      (libsource (lib "eagle-import") (part "M01PTH_WITHOUT_TEXT"))
    )
    (comp (ref "JP290")
      (value "M01PTH_WITHOUT_TEXT")
      (footprint "eagle-import:1X01_WITHOUT_TEXT")
      (libsource (lib "eagle-import") (part "M01PTH_WITHOUT_TEXT"))
    )
    (comp (ref "JP291")
      (value "M01PTH_WITHOUT_TEXT")
      (footprint "eagle-import:1X01_WITHOUT_TEXT")
      (libsource (lib "eagle-import") (part "M01PTH_WITHOUT_TEXT"))
    )
    (comp (ref "JP292")
      (value "M01PTH_WITHOUT_TEXT")
      (footprint "eagle-import:1X01_WITHOUT_TEXT")
      (libsource (lib "eagle-import") (part "M01PTH_WITHOUT_TEXT"))
    )
    (comp (ref "JP293")
      (value "M01PTH_WITHOUT_TEXT")
      (footprint "eagle-import:1X01_WITHOUT_TEXT")
      (libsource (lib "eagle-import") (part "M01PTH_WITHOUT_TEXT"))
    )
    (comp (ref "JP294")
      (value "M01PTH_WITHOUT_TEXT")
      (footprint "eagle-import:1X01_WITHOUT_TEXT")
      (libsource (lib "eagle-import") (part "M01PTH_WITHOUT_TEXT"))
    )
    (comp (ref "JP295")
      (value "M01PTH_WITHOUT_TEXT")
      (footprint "eagle-import:1X01_WITHOUT_TEXT")
      (libsource (lib "eagle-import") (part "M01PTH_WITHOUT_TEXT"))
    )
    (comp (ref "JP296")
      (value "M01PTH_WITHOUT_TEXT")
      (footprint "eagle-import:1X01_WITHOUT_TEXT")
      (libsource (lib "eagle-import") (part "M01PTH_WITHOUT_TEXT"))
    )
    (comp (ref "JP297")
      (value "M01PTH_WITHOUT_TEXT")
      (footprint "eagle-import:1X01_WITHOUT_TEXT")
      (libsource (lib "eagle-import") (part "M01PTH_WITHOUT_TEXT"))
    )
    (comp (ref "JP298")
      (value "M01PTH_WITHOUT_TEXT")
      (footprint "eagle-import:1X01_WITHOUT_TEXT")
      (libsource (lib "eagle-import") (part "M01PTH_WITHOUT_TEXT"))
    )
    (comp (ref "JP299")
      (value "M01PTH_WITHOUT_TEXT")
      (footprint "eagle-import:1X01_WITHOUT_TEXT")
      (libsource (lib "eagle-import") (part "M01PTH_WITHOUT_TEXT"))
    )
    (comp (ref "JP300")
      (value "M01PTH_WITHOUT_TEXT")
      (footprint "eagle-import:1X01_WITHOUT_TEXT")
      (libsource (lib "eagle-import") (part "M01PTH_WITHOUT_TEXT"))
    )
    (comp (ref "JP901")
      (value "M01PTH_SMD_3.25X0.85MM_NO_SILK")
      (footprint "eagle-import:1X01_SMD_3.25X0.85MM_NO_SILK")
      (libsource (lib "eagle-import") (part "M01PTH_SMD_3.25X0.85MM_NO_SILK"))
    )
    (comp (ref "JP902")
      (value "M01PTH_SMD_3.25X0.85MM_NO_SILK")
      (footprint "eagle-import:1X01_SMD_3.25X0.85MM_NO_SILK")
      (libsource (lib "eagle-import") (part "M01PTH_SMD_3.25X0.85MM_NO_SILK"))
    )
    (comp (ref "JP903")
      (value "M01PTH_SMD_3.25X0.85MM_NO_SILK")
      (footprint "eagle-import:1X01_SMD_3.25X0.85MM_NO_SILK")
      (libsource (lib "eagle-import") (part "M01PTH_SMD_3.25X0.85MM_NO_SILK"))
    )
    (comp (ref "JP904")
      (value "M01PTH_SMD_3.25X0.85MM_NO_SILK")
      (footprint "eagle-import:1X01_SMD_3.25X0.85MM_NO_SILK")
      (libsource (lib "eagle-import") (part "M01PTH_SMD_3.25X0.85MM_NO_SILK"))
    )
    (comp (ref "JP905")
      (value "M01PTH_SMD_3.25X0.85MM_NO_SILK")
      (footprint "eagle-import:1X01_SMD_3.25X0.85MM_NO_SILK")
      (libsource (lib "eagle-import") (part "M01PTH_SMD_3.25X0.85MM_NO_SILK"))
    )
    (comp (ref "JP906")
      (value "M01PTH_SMD_3.25X0.85MM_NO_SILK")
      (footprint "eagle-import:1X01_SMD_3.25X0.85MM_NO_SILK")
      (libsource (lib "eagle-import") (part "M01PTH_SMD_3.25X0.85MM_NO_SILK"))
    )
    (comp (ref "JP907")
      (value "M01PTH_SMD_3.25X0.85MM_NO_SILK")
      (footprint "eagle-import:1X01_SMD_3.25X0.85MM_NO_SILK")
      (libsource (lib "eagle-import") (part "M01PTH_SMD_3.25X0.85MM_NO_SILK"))
    )
    (comp (ref "JP908")
      (value "M01PTH_SMD_3.25X0.85MM_NO_SILK")
      (footprint "eagle-import:1X01_SMD_3.25X0.85MM_NO_SILK")
      (libsource (lib "eagle-import") (part "M01PTH_SMD_3.25X0.85MM_NO_SILK"))
    )
    (comp (ref "JP909")
      (value "M01PTH_SMD_3.25X0.85MM_NO_SILK")
      (footprint "eagle-import:1X01_SMD_3.25X0.85MM_NO_SILK")
      (libsource (lib "eagle-import") (part "M01PTH_SMD_3.25X0.85MM_NO_SILK"))
    )
    (comp (ref "JP910")
      (value "M01PTH_SMD_3.25X0.85MM_NO_SILK")
      (footprint "eagle-import:1X01_SMD_3.25X0.85MM_NO_SILK")
      (libsource (lib "eagle-import") (part "M01PTH_SMD_3.25X0.85MM_NO_SILK"))
    )
    (comp (ref "JP911")
      (value "M01PTH_SMD_3.25X0.85MM_NO_SILK")
      (footprint "eagle-import:1X01_SMD_3.25X0.85MM_NO_SILK")
      (libsource (lib "eagle-import") (part "M01PTH_SMD_3.25X0.85MM_NO_SILK"))
    )
    (comp (ref "JP912")
      (value "M01PTH_SMD_3.25X0.85MM_NO_SILK")
      (footprint "eagle-import:1X01_SMD_3.25X0.85MM_NO_SILK")
      (libsource (lib "eagle-import") (part "M01PTH_SMD_3.25X0.85MM_NO_SILK"))
    )
    (comp (ref "JP913")
      (value "M01PTH_SMD_3.25X0.85MM_NO_SILK")
      (footprint "eagle-import:1X01_SMD_3.25X0.85MM_NO_SILK")
      (libsource (lib "eagle-import") (part "M01PTH_SMD_3.25X0.85MM_NO_SILK"))
    )
    (comp (ref "JP914")
      (value "M01PTH_SMD_3.25X0.85MM_NO_SILK")
      (footprint "eagle-import:1X01_SMD_3.25X0.85MM_NO_SILK")
      (libsource (lib "eagle-import") (part "M01PTH_SMD_3.25X0.85MM_NO_SILK"))
    )
    (comp (ref "JP915")
      (value "M01PTH_SMD_3.25X0.85MM_NO_SILK")
      (footprint "eagle-import:1X01_SMD_3.25X0.85MM_NO_SILK")
      (libsource (lib "eagle-import") (part "M01PTH_SMD_3.25X0.85MM_NO_SILK"))
    )
    (comp (ref "JP916")
      (value "M01PTH_SMD_3.25X0.85MM_NO_SILK")
      (footprint "eagle-import:1X01_SMD_3.25X0.85MM_NO_SILK")
      (libsource (lib "eagle-import") (part "M01PTH_SMD_3.25X0.85MM_NO_SILK"))
    )
    (comp (ref "JP917")
      (value "M01PTH_SMD_3.25X0.85MM_NO_SILK")
      (footprint "eagle-import:1X01_SMD_3.25X0.85MM_NO_SILK")
      (libsource (lib "eagle-import") (part "M01PTH_SMD_3.25X0.85MM_NO_SILK"))
    )
    (comp (ref "JP918")
      (value "M01PTH_SMD_3.25X0.85MM_NO_SILK")
      (footprint "eagle-import:1X01_SMD_3.25X0.85MM_NO_SILK")
      (libsource (lib "eagle-import") (part "M01PTH_SMD_3.25X0.85MM_NO_SILK"))
    )
    (comp (ref "JP919")
      (value "M01PTH_SMD_3.25X0.85MM_NO_SILK")
      (footprint "eagle-import:1X01_SMD_3.25X0.85MM_NO_SILK")
      (libsource (lib "eagle-import") (part "M01PTH_SMD_3.25X0.85MM_NO_SILK"))
    )
    (comp (ref "JP920")
      (value "M01PTH_SMD_3.25X0.85MM_NO_SILK")
      (footprint "eagle-import:1X01_SMD_3.25X0.85MM_NO_SILK")
      (libsource (lib "eagle-import") (part "M01PTH_SMD_3.25X0.85MM_NO_SILK"))
    )
    (comp (ref "JP921")
      (value "M01PTH_SMD_3.25X0.85MM_NO_SILK")
      (footprint "eagle-import:1X01_SMD_3.25X0.85MM_NO_SILK")
      (libsource (lib "eagle-import") (part "M01PTH_SMD_3.25X0.85MM_NO_SILK"))
    )
    (comp (ref "JP922")
      (value "M01PTH_SMD_3.25X0.85MM_NO_SILK")
      (footprint "eagle-import:1X01_SMD_3.25X0.85MM_NO_SILK")
      (libsource (lib "eagle-import") (part "M01PTH_SMD_3.25X0.85MM_NO_SILK"))
    )
    (comp (ref "JP923")
      (value "M01PTH_SMD_3.25X0.85MM_NO_SILK")
      (footprint "eagle-import:1X01_SMD_3.25X0.85MM_NO_SILK")
      (libsource (lib "eagle-import") (part "M01PTH_SMD_3.25X0.85MM_NO_SILK"))
    )
    (comp (ref "JP924")
      (value "M01PTH_SMD_3.25X0.85MM_NO_SILK")
      (footprint "eagle-import:1X01_SMD_3.25X0.85MM_NO_SILK")
      (libsource (lib "eagle-import") (part "M01PTH_SMD_3.25X0.85MM_NO_SILK"))
    )
    (comp (ref "JP925")
      (value "M01PTH_SMD_3.25X0.85MM_NO_SILK")
      (footprint "eagle-import:1X01_SMD_3.25X0.85MM_NO_SILK")
      (libsource (lib "eagle-import") (part "M01PTH_SMD_3.25X0.85MM_NO_SILK"))
    )
    (comp (ref "JP926")
      (value "M01PTH_SMD_3.25X0.85MM_NO_SILK")
      (footprint "eagle-import:1X01_SMD_3.25X0.85MM_NO_SILK")
      (libsource (lib "eagle-import") (part "M01PTH_SMD_3.25X0.85MM_NO_SILK"))
    )
    (comp (ref "JP927")
      (value "M01PTH_SMD_3.25X0.85MM_NO_SILK")
      (footprint "eagle-import:1X01_SMD_3.25X0.85MM_NO_SILK")
      (libsource (lib "eagle-import") (part "M01PTH_SMD_3.25X0.85MM_NO_SILK"))
    )
    (comp (ref "JP928")
      (value "M01PTH_SMD_3.25X0.85MM_NO_SILK")
      (footprint "eagle-import:1X01_SMD_3.25X0.85MM_NO_SILK")
      (libsource (lib "eagle-import") (part "M01PTH_SMD_3.25X0.85MM_NO_SILK"))
    )
    (comp (ref "JP929")
      (value "M01PTH_SMD_3.25X0.85MM_NO_SILK")
      (footprint "eagle-import:1X01_SMD_3.25X0.85MM_NO_SILK")
      (libsource (lib "eagle-import") (part "M01PTH_SMD_3.25X0.85MM_NO_SILK"))
    )
    (comp (ref "JP930")
      (value "M01PTH_SMD_3.25X0.85MM_NO_SILK")
      (footprint "eagle-import:1X01_SMD_3.25X0.85MM_NO_SILK")
      (libsource (lib "eagle-import") (part "M01PTH_SMD_3.25X0.85MM_NO_SILK"))
    )
    (comp (ref "JP931")
      (value "M01PTH_SMD_3.25X0.85MM_NO_SILK")
      (footprint "eagle-import:1X01_SMD_3.25X0.85MM_NO_SILK")
      (libsource (lib "eagle-import") (part "M01PTH_SMD_3.25X0.85MM_NO_SILK"))
    )
    (comp (ref "JP932")
      (value "M01PTH_SMD_3.25X0.85MM_NO_SILK")
      (footprint "eagle-import:1X01_SMD_3.25X0.85MM_NO_SILK")
      (libsource (lib "eagle-import") (part "M01PTH_SMD_3.25X0.85MM_NO_SILK"))
    )
    (comp (ref "JP933")
      (value "M01PTH_SMD_3.25X0.85MM_NO_SILK")
      (footprint "eagle-import:1X01_SMD_3.25X0.85MM_NO_SILK")
      (libsource (lib "eagle-import") (part "M01PTH_SMD_3.25X0.85MM_NO_SILK"))
    )
    (comp (ref "JP934")
      (value "M01PTH_SMD_3.25X0.85MM_NO_SILK")
      (footprint "eagle-import:1X01_SMD_3.25X0.85MM_NO_SILK")
      (libsource (lib "eagle-import") (part "M01PTH_SMD_3.25X0.85MM_NO_SILK"))
    )
    (comp (ref "JP935")
      (value "M01PTH_SMD_3.25X0.85MM_NO_SILK")
      (footprint "eagle-import:1X01_SMD_3.25X0.85MM_NO_SILK")
      (libsource (lib "eagle-import") (part "M01PTH_SMD_3.25X0.85MM_NO_SILK"))
    )
    (comp (ref "JP936")
      (value "M01PTH_SMD_3.25X0.85MM_NO_SILK")
      (footprint "eagle-import:1X01_SMD_3.25X0.85MM_NO_SILK")
      (libsource (lib "eagle-import") (part "M01PTH_SMD_3.25X0.85MM_NO_SILK"))
    )
    (comp (ref "JP937")
      (value "M01PTH_SMD_3.25X0.85MM_NO_SILK")
      (footprint "eagle-import:1X01_SMD_3.25X0.85MM_NO_SILK")
      (libsource (lib "eagle-import") (part "M01PTH_SMD_3.25X0.85MM_NO_SILK"))
    )
    (comp (ref "JP938")
      (value "M01PTH_SMD_3.25X0.85MM_NO_SILK")
      (footprint "eagle-import:1X01_SMD_3.25X0.85MM_NO_SILK")
      (libsource (lib "eagle-import") (part "M01PTH_SMD_3.25X0.85MM_NO_SILK"))
    )
    (comp (ref "JP939")
      (value "M01PTH_SMD_3.25X0.85MM_NO_SILK")
      (footprint "eagle-import:1X01_SMD_3.25X0.85MM_NO_SILK")
      (libsource (lib "eagle-import") (part "M01PTH_SMD_3.25X0.85MM_NO_SILK"))
    )
    (comp (ref "JP940")
      (value "M01PTH_SMD_3.25X0.85MM_NO_SILK")
      (footprint "eagle-import:1X01_SMD_3.25X0.85MM_NO_SILK")
      (libsource (lib "eagle-import") (part "M01PTH_SMD_3.25X0.85MM_NO_SILK"))
    )
    (comp (ref "JP941")
      (value "M01PTH_SMD_3.25X0.85MM_NO_SILK")
      (footprint "eagle-import:1X01_SMD_3.25X0.85MM_NO_SILK")
      (libsource (lib "eagle-import") (part "M01PTH_SMD_3.25X0.85MM_NO_SILK"))
    )
    (comp (ref "JP942")
      (value "M01PTH_SMD_3.25X0.85MM_NO_SILK")
      (footprint "eagle-import:1X01_SMD_3.25X0.85MM_NO_SILK")
      (libsource (lib "eagle-import") (part "M01PTH_SMD_3.25X0.85MM_NO_SILK"))
    )
    (comp (ref "JP943")
      (value "M01PTH_SMD_3.25X0.85MM_NO_SILK")
      (footprint "eagle-import:1X01_SMD_3.25X0.85MM_NO_SILK")
      (libsource (lib "eagle-import") (part "M01PTH_SMD_3.25X0.85MM_NO_SILK"))
    )
    (comp (ref "JP944")
      (value "M01PTH_SMD_3.25X0.85MM_NO_SILK")
      (footprint "eagle-import:1X01_SMD_3.25X0.85MM_NO_SILK")
      (libsource (lib "eagle-import") (part "M01PTH_SMD_3.25X0.85MM_NO_SILK"))
    )
    (comp (ref "JP945")
      (value "M01PTH_SMD_3.25X0.85MM_NO_SILK")
      (footprint "eagle-import:1X01_SMD_3.25X0.85MM_NO_SILK")
      (libsource (lib "eagle-import") (part "M01PTH_SMD_3.25X0.85MM_NO_SILK"))
    )
    (comp (ref "JP946")
      (value "M01PTH_SMD_3.25X0.85MM_NO_SILK")
      (footprint "eagle-import:1X01_SMD_3.25X0.85MM_NO_SILK")
      (libsource (lib "eagle-import") (part "M01PTH_SMD_3.25X0.85MM_NO_SILK"))
    )
    (comp (ref "JP947")
      (value "M01PTH_SMD_3.25X0.85MM_NO_SILK")
      (footprint "eagle-import:1X01_SMD_3.25X0.85MM_NO_SILK")
      (libsource (lib "eagle-import") (part "M01PTH_SMD_3.25X0.85MM_NO_SILK"))
    )
    (comp (ref "JP948")
      (value "M01PTH_SMD_3.25X0.85MM_NO_SILK")
      (footprint "eagle-import:1X01_SMD_3.25X0.85MM_NO_SILK")
      (libsource (lib "eagle-import") (part "M01PTH_SMD_3.25X0.85MM_NO_SILK"))
    )
    (comp (ref "JP949")
      (value "M01PTH_SMD_3.25X0.85MM_NO_SILK")
      (footprint "eagle-import:1X01_SMD_3.25X0.85MM_NO_SILK")
      (libsource (lib "eagle-import") (part "M01PTH_SMD_3.25X0.85MM_NO_SILK"))
    )
    (comp (ref "JP950")
      (value "M01PTH_SMD_3.25X0.85MM_NO_SILK")
      (footprint "eagle-import:1X01_SMD_3.25X0.85MM_NO_SILK")
      (libsource (lib "eagle-import") (part "M01PTH_SMD_3.25X0.85MM_NO_SILK"))
    )
    (comp (ref "JP951")
      (value "M01PTH_SMD_3.25X0.85MM_NO_SILK")
      (footprint "eagle-import:1X01_SMD_3.25X0.85MM_NO_SILK")
      (libsource (lib "eagle-import") (part "M01PTH_SMD_3.25X0.85MM_NO_SILK"))
    )
    (comp (ref "JP952")
      (value "M01PTH_SMD_3.25X0.85MM_NO_SILK")
      (footprint "eagle-import:1X01_SMD_3.25X0.85MM_NO_SILK")
      (libsource (lib "eagle-import") (part "M01PTH_SMD_3.25X0.85MM_NO_SILK"))
    )
    (comp (ref "JP953")
      (value "M01PTH_SMD_3.25X0.85MM_NO_SILK")
      (footprint "eagle-import:1X01_SMD_3.25X0.85MM_NO_SILK")
      (libsource (lib "eagle-import") (part "M01PTH_SMD_3.25X0.85MM_NO_SILK"))
    )
    (comp (ref "JP954")
      (value "M01PTH_SMD_3.25X0.85MM_NO_SILK")
      (footprint "eagle-import:1X01_SMD_3.25X0.85MM_NO_SILK")
      (libsource (lib "eagle-import") (part "M01PTH_SMD_3.25X0.85MM_NO_SILK"))
    )
    (comp (ref "JP955")
      (value "M01PTH_SMD_3.25X0.85MM_NO_SILK")
      (footprint "eagle-import:1X01_SMD_3.25X0.85MM_NO_SILK")
      (libsource (lib "eagle-import") (part "M01PTH_SMD_3.25X0.85MM_NO_SILK"))
    )
    (comp (ref "JP956")
      (value "M01PTH_SMD_3.25X0.85MM_NO_SILK")
      (footprint "eagle-import:1X01_SMD_3.25X0.85MM_NO_SILK")
      (libsource (lib "eagle-import") (part "M01PTH_SMD_3.25X0.85MM_NO_SILK"))
    )
    (comp (ref "JP957")
      (value "M01PTH_SMD_3.25X0.85MM_NO_SILK")
      (footprint "eagle-import:1X01_SMD_3.25X0.85MM_NO_SILK")
      (libsource (lib "eagle-import") (part "M01PTH_SMD_3.25X0.85MM_NO_SILK"))
    )
    (comp (ref "JP958")
      (value "M01PTH_SMD_3.25X0.85MM_NO_SILK")
      (footprint "eagle-import:1X01_SMD_3.25X0.85MM_NO_SILK")
      (libsource (lib "eagle-import") (part "M01PTH_SMD_3.25X0.85MM_NO_SILK"))
    )
    (comp (ref "JP959")
      (value "M01PTH_SMD_3.25X0.85MM_NO_SILK")
      (footprint "eagle-import:1X01_SMD_3.25X0.85MM_NO_SILK")
      (libsource (lib "eagle-import") (part "M01PTH_SMD_3.25X0.85MM_NO_SILK"))
    )
    (comp (ref "JP960")
      (value "M01PTH_SMD_3.25X0.85MM_NO_SILK")
      (footprint "eagle-import:1X01_SMD_3.25X0.85MM_NO_SILK")
      (libsource (lib "eagle-import") (part "M01PTH_SMD_3.25X0.85MM_NO_SILK"))
    )
    (comp (ref "JP961")
      (value "M01PTH_SMD_3.25X0.85MM_NO_SILK")
      (footprint "eagle-import:1X01_SMD_3.25X0.85MM_NO_SILK")
      (libsource (lib "eagle-import") (part "M01PTH_SMD_3.25X0.85MM_NO_SILK"))
    )
    (comp (ref "JP962")
      (value "M01PTH_SMD_3.25X0.85MM_NO_SILK")
      (footprint "eagle-import:1X01_SMD_3.25X0.85MM_NO_SILK")
      (libsource (lib "eagle-import") (part "M01PTH_SMD_3.25X0.85MM_NO_SILK"))
    )
    (comp (ref "JP963")
      (value "M01PTH_SMD_3.25X0.85MM_NO_SILK")
      (footprint "eagle-import:1X01_SMD_3.25X0.85MM_NO_SILK")
      (libsource (lib "eagle-import") (part "M01PTH_SMD_3.25X0.85MM_NO_SILK"))
    )
    (comp (ref "JP964")
      (value "M01PTH_SMD_3.25X0.85MM_NO_SILK")
      (footprint "eagle-import:1X01_SMD_3.25X0.85MM_NO_SILK")
      (libsource (lib "eagle-import") (part "M01PTH_SMD_3.25X0.85MM_NO_SILK"))
    )
    (comp (ref "JP965")
      (value "M01PTH_SMD_3.25X0.85MM_NO_SILK")
      (footprint "eagle-import:1X01_SMD_3.25X0.85MM_NO_SILK")
      (libsource (lib "eagle-import") (part "M01PTH_SMD_3.25X0.85MM_NO_SILK"))
    )
    (comp (ref "JP966")
      (value "M01PTH_SMD_3.25X0.85MM_NO_SILK")
      (footprint "eagle-import:1X01_SMD_3.25X0.85MM_NO_SILK")
      (libsource (lib "eagle-import") (part "M01PTH_SMD_3.25X0.85MM_NO_SILK"))
    )
    (comp (ref "JP967")
      (value "M01PTH_SMD_3.25X0.85MM_NO_SILK")
      (footprint "eagle-import:1X01_SMD_3.25X0.85MM_NO_SILK")
      (libsource (lib "eagle-import") (part "M01PTH_SMD_3.25X0.85MM_NO_SILK"))
    )
    (comp (ref "JP968")
      (value "M01PTH_SMD_3.25X0.85MM_NO_SILK")
      (footprint "eagle-import:1X01_SMD_3.25X0.85MM_NO_SILK")
      (libsource (lib "eagle-import") (part "M01PTH_SMD_3.25X0.85MM_NO_SILK"))
    )
    (comp (ref "JP969")
      (value "M01PTH_SMD_3.25X0.85MM_NO_SILK")
      (footprint "eagle-import:1X01_SMD_3.25X0.85MM_NO_SILK")
      (libsource (lib "eagle-import") (part "M01PTH_SMD_3.25X0.85MM_NO_SILK"))
    )
    (comp (ref "JP970")
      (value "M01PTH_SMD_3.25X0.85MM_NO_SILK")
      (footprint "eagle-import:1X01_SMD_3.25X0.85MM_NO_SILK")
      (libsource (lib "eagle-import") (part "M01PTH_SMD_3.25X0.85MM_NO_SILK"))
    )
    (comp (ref "JP971")
      (value "M01PTH_SMD_3.25X0.85MM_NO_SILK")
      (footprint "eagle-import:1X01_SMD_3.25X0.85MM_NO_SILK")
      (libsource (lib "eagle-import") (part "M01PTH_SMD_3.25X0.85MM_NO_SILK"))
    )
    (comp (ref "JP972")
      (value "M01PTH_SMD_3.25X0.85MM_NO_SILK")
      (footprint "eagle-import:1X01_SMD_3.25X0.85MM_NO_SILK")
      (libsource (lib "eagle-import") (part "M01PTH_SMD_3.25X0.85MM_NO_SILK"))
    )
    (comp (ref "JP973")
      (value "M01PTH_SMD_3.25X0.85MM_NO_SILK")
      (footprint "eagle-import:1X01_SMD_3.25X0.85MM_NO_SILK")
      (libsource (lib "eagle-import") (part "M01PTH_SMD_3.25X0.85MM_NO_SILK"))
    )
    (comp (ref "JP974")
      (value "M01PTH_SMD_3.25X0.85MM_NO_SILK")
      (footprint "eagle-import:1X01_SMD_3.25X0.85MM_NO_SILK")
      (libsource (lib "eagle-import") (part "M01PTH_SMD_3.25X0.85MM_NO_SILK"))
    )
    (comp (ref "JP975")
      (value "M01PTH_SMD_3.25X0.85MM_NO_SILK")
      (footprint "eagle-import:1X01_SMD_3.25X0.85MM_NO_SILK")
      (libsource (lib "eagle-import") (part "M01PTH_SMD_3.25X0.85MM_NO_SILK"))
    )
    (comp (ref "JP976")
      (value "M01PTH_SMD_3.25X0.85MM_NO_SILK")
      (footprint "eagle-import:1X01_SMD_3.25X0.85MM_NO_SILK")
      (libsource (lib "eagle-import") (part "M01PTH_SMD_3.25X0.85MM_NO_SILK"))
    )
    (comp (ref "JP977")
      (value "M01PTH_SMD_3.25X0.85MM_NO_SILK")
      (footprint "eagle-import:1X01_SMD_3.25X0.85MM_NO_SILK")
      (libsource (lib "eagle-import") (part "M01PTH_SMD_3.25X0.85MM_NO_SILK"))
    )
    (comp (ref "JP978")
      (value "M01PTH_SMD_3.25X0.85MM_NO_SILK")
      (footprint "eagle-import:1X01_SMD_3.25X0.85MM_NO_SILK")
      (libsource (lib "eagle-import") (part "M01PTH_SMD_3.25X0.85MM_NO_SILK"))
    )
    (comp (ref "JP979")
      (value "M01PTH_SMD_3.25X0.85MM_NO_SILK")
      (footprint "eagle-import:1X01_SMD_3.25X0.85MM_NO_SILK")
      (libsource (lib "eagle-import") (part "M01PTH_SMD_3.25X0.85MM_NO_SILK"))
    )
    (comp (ref "JP980")
      (value "M01PTH_SMD_3.25X0.85MM_NO_SILK")
      (footprint "eagle-import:1X01_SMD_3.25X0.85MM_NO_SILK")
      (libsource (lib "eagle-import") (part "M01PTH_SMD_3.25X0.85MM_NO_SILK"))
    )
    (comp (ref "JP981")
      (value "M01PTH_SMD_3.25X0.85MM_NO_SILK")
      (footprint "eagle-import:1X01_SMD_3.25X0.85MM_NO_SILK")
      (libsource (lib "eagle-import") (part "M01PTH_SMD_3.25X0.85MM_NO_SILK"))
    )
    (comp (ref "JP982")
      (value "M01PTH_SMD_3.25X0.85MM_NO_SILK")
      (footprint "eagle-import:1X01_SMD_3.25X0.85MM_NO_SILK")
      (libsource (lib "eagle-import") (part "M01PTH_SMD_3.25X0.85MM_NO_SILK"))
    )
    (comp (ref "JP983")
      (value "M01PTH_SMD_3.25X0.85MM_NO_SILK")
      (footprint "eagle-import:1X01_SMD_3.25X0.85MM_NO_SILK")
      (libsource (lib "eagle-import") (part "M01PTH_SMD_3.25X0.85MM_NO_SILK"))
    )
    (comp (ref "JP984")
      (value "M01PTH_SMD_3.25X0.85MM_NO_SILK")
      (footprint "eagle-import:1X01_SMD_3.25X0.85MM_NO_SILK")
      (libsource (lib "eagle-import") (part "M01PTH_SMD_3.25X0.85MM_NO_SILK"))
    )
    (comp (ref "JP985")
      (value "M01PTH_SMD_3.25X0.85MM_NO_SILK")
      (footprint "eagle-import:1X01_SMD_3.25X0.85MM_NO_SILK")
      (libsource (lib "eagle-import") (part "M01PTH_SMD_3.25X0.85MM_NO_SILK"))
    )
    (comp (ref "JP986")
      (value "M01PTH_SMD_3.25X0.85MM_NO_SILK")
      (footprint "eagle-import:1X01_SMD_3.25X0.85MM_NO_SILK")
      (libsource (lib "eagle-import") (part "M01PTH_SMD_3.25X0.85MM_NO_SILK"))
    )
    (comp (ref "JP987")
      (value "M01PTH_SMD_3.25X0.85MM_NO_SILK")
      (footprint "eagle-import:1X01_SMD_3.25X0.85MM_NO_SILK")
      (libsource (lib "eagle-import") (part "M01PTH_SMD_3.25X0.85MM_NO_SILK"))
    )
    (comp (ref "JP988")
      (value "M01PTH_SMD_3.25X0.85MM_NO_SILK")
      (footprint "eagle-import:1X01_SMD_3.25X0.85MM_NO_SILK")
      (libsource (lib "eagle-import") (part "M01PTH_SMD_3.25X0.85MM_NO_SILK"))
    )
    (comp (ref "JP989")
      (value "M01PTH_SMD_3.25X0.85MM_NO_SILK")
      (footprint "eagle-import:1X01_SMD_3.25X0.85MM_NO_SILK")
      (libsource (lib "eagle-import") (part "M01PTH_SMD_3.25X0.85MM_NO_SILK"))
    )
    (comp (ref "JP990")
      (value "M01PTH_SMD_3.25X0.85MM_NO_SILK")
      (footprint "eagle-import:1X01_SMD_3.25X0.85MM_NO_SILK")
      (libsource (lib "eagle-import") (part "M01PTH_SMD_3.25X0.85MM_NO_SILK"))
    )
    (comp (ref "JP991")
      (value "M01PTH_SMD_3.25X0.85MM_NO_SILK")
      (footprint "eagle-import:1X01_SMD_3.25X0.85MM_NO_SILK")
      (libsource (lib "eagle-import") (part "M01PTH_SMD_3.25X0.85MM_NO_SILK"))
    )
    (comp (ref "JP992")
      (value "M01PTH_SMD_3.25X0.85MM_NO_SILK")
      (footprint "eagle-import:1X01_SMD_3.25X0.85MM_NO_SILK")
      (libsource (lib "eagle-import") (part "M01PTH_SMD_3.25X0.85MM_NO_SILK"))
    )
    (comp (ref "JP993")
      (value "M01PTH_SMD_3.25X0.85MM_NO_SILK")
      (footprint "eagle-import:1X01_SMD_3.25X0.85MM_NO_SILK")
      (libsource (lib "eagle-import") (part "M01PTH_SMD_3.25X0.85MM_NO_SILK"))
    )
    (comp (ref "JP994")
      (value "M01PTH_SMD_3.25X0.85MM_NO_SILK")
      (footprint "eagle-import:1X01_SMD_3.25X0.85MM_NO_SILK")
      (libsource (lib "eagle-import") (part "M01PTH_SMD_3.25X0.85MM_NO_SILK"))
    )
    (comp (ref "JP995")
      (value "M01PTH_SMD_3.25X0.85MM_NO_SILK")
      (footprint "eagle-import:1X01_SMD_3.25X0.85MM_NO_SILK")
      (libsource (lib "eagle-import") (part "M01PTH_SMD_3.25X0.85MM_NO_SILK"))
    )
    (comp (ref "JP996")
      (value "M01PTH_SMD_3.25X0.85MM_NO_SILK")
      (footprint "eagle-import:1X01_SMD_3.25X0.85MM_NO_SILK")
      (libsource (lib "eagle-import") (part "M01PTH_SMD_3.25X0.85MM_NO_SILK"))
    )
    (comp (ref "JP997")
      (value "M01PTH_SMD_3.25X0.85MM_NO_SILK")
      (footprint "eagle-import:1X01_SMD_3.25X0.85MM_NO_SILK")
      (libsource (lib "eagle-import") (part "M01PTH_SMD_3.25X0.85MM_NO_SILK"))
    )
    (comp (ref "JP998")
      (value "M01PTH_SMD_3.25X0.85MM_NO_SILK")
      (footprint "eagle-import:1X01_SMD_3.25X0.85MM_NO_SILK")
      (libsource (lib "eagle-import") (part "M01PTH_SMD_3.25X0.85MM_NO_SILK"))
    )
    (comp (ref "JP999")
      (value "M01PTH_SMD_3.25X0.85MM_NO_SILK")
      (footprint "eagle-import:1X01_SMD_3.25X0.85MM_NO_SILK")
      (libsource (lib "eagle-import") (part "M01PTH_SMD_3.25X0.85MM_NO_SILK"))
    )
    (comp (ref "JP1000")
      (value "M01PTH_SMD_3.25X0.85MM_NO_SILK")
      (footprint "eagle-import:1X01_SMD_3.25X0.85MM_NO_SILK")
      (libsource (lib "eagle-import") (part "M01PTH_SMD_3.25X0.85MM_NO_SILK"))
    )
    (comp (ref "JP1001")
      (value "M01PTH_SMD_3.25X0.85MM_NO_SILK")
      (footprint "eagle-import:1X01_SMD_3.25X0.85MM_NO_SILK")
      (libsource (lib "eagle-import") (part "M01PTH_SMD_3.25X0.85MM_NO_SILK"))
    )
    (comp (ref "JP1002")
      (value "M01PTH_SMD_3.25X0.85MM_NO_SILK")
      (footprint "eagle-import:1X01_SMD_3.25X0.85MM_NO_SILK")
      (libsource (lib "eagle-import") (part "M01PTH_SMD_3.25X0.85MM_NO_SILK"))
    )
    (comp (ref "JP1003")
      (value "M01PTH_SMD_3.25X0.85MM_NO_SILK")
      (footprint "eagle-import:1X01_SMD_3.25X0.85MM_NO_SILK")
      (libsource (lib "eagle-import") (part "M01PTH_SMD_3.25X0.85MM_NO_SILK"))
    )
    (comp (ref "JP1004")
      (value "M01PTH_SMD_3.25X0.85MM_NO_SILK")
      (footprint "eagle-import:1X01_SMD_3.25X0.85MM_NO_SILK")
      (libsource (lib "eagle-import") (part "M01PTH_SMD_3.25X0.85MM_NO_SILK"))
    )
    (comp (ref "JP1005")
      (value "M01PTH_SMD_3.25X0.85MM_NO_SILK")
      (footprint "eagle-import:1X01_SMD_3.25X0.85MM_NO_SILK")
      (libsource (lib "eagle-import") (part "M01PTH_SMD_3.25X0.85MM_NO_SILK"))
    )
    (comp (ref "JP1006")
      (value "M01PTH_SMD_3.25X0.85MM_NO_SILK")
      (footprint "eagle-import:1X01_SMD_3.25X0.85MM_NO_SILK")
      (libsource (lib "eagle-import") (part "M01PTH_SMD_3.25X0.85MM_NO_SILK"))
    )
    (comp (ref "JP1007")
      (value "M01PTH_SMD_3.25X0.85MM_NO_SILK")
      (footprint "eagle-import:1X01_SMD_3.25X0.85MM_NO_SILK")
      (libsource (lib "eagle-import") (part "M01PTH_SMD_3.25X0.85MM_NO_SILK"))
    )
    (comp (ref "JP1008")
      (value "M01PTH_SMD_3.25X0.85MM_NO_SILK")
      (footprint "eagle-import:1X01_SMD_3.25X0.85MM_NO_SILK")
      (libsource (lib "eagle-import") (part "M01PTH_SMD_3.25X0.85MM_NO_SILK"))
    )
    (comp (ref "JP1009")
      (value "M01PTH_SMD_3.25X0.85MM_NO_SILK")
      (footprint "eagle-import:1X01_SMD_3.25X0.85MM_NO_SILK")
      (libsource (lib "eagle-import") (part "M01PTH_SMD_3.25X0.85MM_NO_SILK"))
    )
    (comp (ref "JP1010")
      (value "M01PTH_SMD_3.25X0.85MM_NO_SILK")
      (footprint "eagle-import:1X01_SMD_3.25X0.85MM_NO_SILK")
      (libsource (lib "eagle-import") (part "M01PTH_SMD_3.25X0.85MM_NO_SILK"))
    )
    (comp (ref "JP1011")
      (value "M01PTH_SMD_3.25X0.85MM_NO_SILK")
      (footprint "eagle-import:1X01_SMD_3.25X0.85MM_NO_SILK")
      (libsource (lib "eagle-import") (part "M01PTH_SMD_3.25X0.85MM_NO_SILK"))
    )
    (comp (ref "JP1012")
      (value "M01PTH_SMD_3.25X0.85MM_NO_SILK")
      (footprint "eagle-import:1X01_SMD_3.25X0.85MM_NO_SILK")
      (libsource (lib "eagle-import") (part "M01PTH_SMD_3.25X0.85MM_NO_SILK"))
    )
    (comp (ref "JP1013")
      (value "M01PTH_SMD_3.25X0.85MM_NO_SILK")
      (footprint "eagle-import:1X01_SMD_3.25X0.85MM_NO_SILK")
      (libsource (lib "eagle-import") (part "M01PTH_SMD_3.25X0.85MM_NO_SILK"))
    )
    (comp (ref "JP1014")
      (value "M01PTH_SMD_3.25X0.85MM_NO_SILK")
      (footprint "eagle-import:1X01_SMD_3.25X0.85MM_NO_SILK")
      (libsource (lib "eagle-import") (part "M01PTH_SMD_3.25X0.85MM_NO_SILK"))
    )
    (comp (ref "JP1015")
      (value "M01PTH_SMD_3.25X0.85MM_NO_SILK")
      (footprint "eagle-import:1X01_SMD_3.25X0.85MM_NO_SILK")
      (libsource (lib "eagle-import") (part "M01PTH_SMD_3.25X0.85MM_NO_SILK"))
    )
    (comp (ref "JP1016")
      (value "M01PTH_SMD_3.25X0.85MM_NO_SILK")
      (footprint "eagle-import:1X01_SMD_3.25X0.85MM_NO_SILK")
      (libsource (lib "eagle-import") (part "M01PTH_SMD_3.25X0.85MM_NO_SILK"))
    )
    (comp (ref "JP1017")
      (value "M01PTH_SMD_3.25X0.85MM_NO_SILK")
      (footprint "eagle-import:1X01_SMD_3.25X0.85MM_NO_SILK")
      (libsource (lib "eagle-import") (part "M01PTH_SMD_3.25X0.85MM_NO_SILK"))
    )
    (comp (ref "JP1018")
      (value "M01PTH_SMD_3.25X0.85MM_NO_SILK")
      (footprint "eagle-import:1X01_SMD_3.25X0.85MM_NO_SILK")
      (libsource (lib "eagle-import") (part "M01PTH_SMD_3.25X0.85MM_NO_SILK"))
    )
    (comp (ref "JP1019")
      (value "M01PTH_SMD_3.25X0.85MM_NO_SILK")
      (footprint "eagle-import:1X01_SMD_3.25X0.85MM_NO_SILK")
      (libsource (lib "eagle-import") (part "M01PTH_SMD_3.25X0.85MM_NO_SILK"))
    )
    (comp (ref "JP1020")
      (value "M01PTH_SMD_3.25X0.85MM_NO_SILK")
      (footprint "eagle-import:1X01_SMD_3.25X0.85MM_NO_SILK")
      (libsource (lib "eagle-import") (part "M01PTH_SMD_3.25X0.85MM_NO_SILK"))
    )
    (comp (ref "JP1021")
      (value "M01PTH_SMD_3.25X0.85MM_NO_SILK")
      (footprint "eagle-import:1X01_SMD_3.25X0.85MM_NO_SILK")
      (libsource (lib "eagle-import") (part "M01PTH_SMD_3.25X0.85MM_NO_SILK"))
    )
    (comp (ref "JP1022")
      (value "M01PTH_SMD_3.25X0.85MM_NO_SILK")
      (footprint "eagle-import:1X01_SMD_3.25X0.85MM_NO_SILK")
      (libsource (lib "eagle-import") (part "M01PTH_SMD_3.25X0.85MM_NO_SILK"))
    )
    (comp (ref "JP1023")
      (value "M01PTH_SMD_3.25X0.85MM_NO_SILK")
      (footprint "eagle-import:1X01_SMD_3.25X0.85MM_NO_SILK")
      (libsource (lib "eagle-import") (part "M01PTH_SMD_3.25X0.85MM_NO_SILK"))
    )
    (comp (ref "JP1024")
      (value "M01PTH_SMD_3.25X0.85MM_NO_SILK")
      (footprint "eagle-import:1X01_SMD_3.25X0.85MM_NO_SILK")
      (libsource (lib "eagle-import") (part "M01PTH_SMD_3.25X0.85MM_NO_SILK"))
    )
    (comp (ref "JP1025")
      (value "M01PTH_SMD_3.25X0.85MM_NO_SILK")
      (footprint "eagle-import:1X01_SMD_3.25X0.85MM_NO_SILK")
      (libsource (lib "eagle-import") (part "M01PTH_SMD_3.25X0.85MM_NO_SILK"))
    )
    (comp (ref "JP1026")
      (value "M01PTH_SMD_3.25X0.85MM_NO_SILK")
      (footprint "eagle-import:1X01_SMD_3.25X0.85MM_NO_SILK")
      (libsource (lib "eagle-import") (part "M01PTH_SMD_3.25X0.85MM_NO_SILK"))
    )
    (comp (ref "JP1027")
      (value "M01PTH_SMD_3.25X0.85MM_NO_SILK")
      (footprint "eagle-import:1X01_SMD_3.25X0.85MM_NO_SILK")
      (libsource (lib "eagle-import") (part "M01PTH_SMD_3.25X0.85MM_NO_SILK"))
    )
    (comp (ref "JP1028")
      (value "M01PTH_SMD_3.25X0.85MM_NO_SILK")
      (footprint "eagle-import:1X01_SMD_3.25X0.85MM_NO_SILK")
      (libsource (lib "eagle-import") (part "M01PTH_SMD_3.25X0.85MM_NO_SILK"))
    )
    (comp (ref "JP1029")
      (value "M01PTH_SMD_3.25X0.85MM_NO_SILK")
      (footprint "eagle-import:1X01_SMD_3.25X0.85MM_NO_SILK")
      (libsource (lib "eagle-import") (part "M01PTH_SMD_3.25X0.85MM_NO_SILK"))
    )
    (comp (ref "JP1030")
      (value "M01PTH_SMD_3.25X0.85MM_NO_SILK")
      (footprint "eagle-import:1X01_SMD_3.25X0.85MM_NO_SILK")
      (libsource (lib "eagle-import") (part "M01PTH_SMD_3.25X0.85MM_NO_SILK"))
    )
    (comp (ref "JP1031")
      (value "M01PTH_SMD_3.25X0.85MM_NO_SILK")
      (footprint "eagle-import:1X01_SMD_3.25X0.85MM_NO_SILK")
      (libsource (lib "eagle-import") (part "M01PTH_SMD_3.25X0.85MM_NO_SILK"))
    )
    (comp (ref "JP1032")
      (value "M01PTH_SMD_3.25X0.85MM_NO_SILK")
      (footprint "eagle-import:1X01_SMD_3.25X0.85MM_NO_SILK")
      (libsource (lib "eagle-import") (part "M01PTH_SMD_3.25X0.85MM_NO_SILK"))
    )
    (comp (ref "JP1033")
      (value "M01PTH_SMD_3.25X0.85MM_NO_SILK")
      (footprint "eagle-import:1X01_SMD_3.25X0.85MM_NO_SILK")
      (libsource (lib "eagle-import") (part "M01PTH_SMD_3.25X0.85MM_NO_SILK"))
    )
    (comp (ref "JP1034")
      (value "M01PTH_SMD_3.25X0.85MM_NO_SILK")
      (footprint "eagle-import:1X01_SMD_3.25X0.85MM_NO_SILK")
      (libsource (lib "eagle-import") (part "M01PTH_SMD_3.25X0.85MM_NO_SILK"))
    )
    (comp (ref "JP1035")
      (value "M01PTH_SMD_3.25X0.85MM_NO_SILK")
      (footprint "eagle-import:1X01_SMD_3.25X0.85MM_NO_SILK")
      (libsource (lib "eagle-import") (part "M01PTH_SMD_3.25X0.85MM_NO_SILK"))
    )
    (comp (ref "JP1036")
      (value "M01PTH_SMD_3.25X0.85MM_NO_SILK")
      (footprint "eagle-import:1X01_SMD_3.25X0.85MM_NO_SILK")
      (libsource (lib "eagle-import") (part "M01PTH_SMD_3.25X0.85MM_NO_SILK"))
    )
    (comp (ref "JP1037")
      (value "M01PTH_SMD_3.25X0.85MM_NO_SILK")
      (footprint "eagle-import:1X01_SMD_3.25X0.85MM_NO_SILK")
      (libsource (lib "eagle-import") (part "M01PTH_SMD_3.25X0.85MM_NO_SILK"))
    )
    (comp (ref "JP1038")
      (value "M01PTH_SMD_3.25X0.85MM_NO_SILK")
      (footprint "eagle-import:1X01_SMD_3.25X0.85MM_NO_SILK")
      (libsource (lib "eagle-import") (part "M01PTH_SMD_3.25X0.85MM_NO_SILK"))
    )
    (comp (ref "JP1039")
      (value "M01PTH_SMD_3.25X0.85MM_NO_SILK")
      (footprint "eagle-import:1X01_SMD_3.25X0.85MM_NO_SILK")
      (libsource (lib "eagle-import") (part "M01PTH_SMD_3.25X0.85MM_NO_SILK"))
    )
    (comp (ref "JP1040")
      (value "M01PTH_SMD_3.25X0.85MM_NO_SILK")
      (footprint "eagle-import:1X01_SMD_3.25X0.85MM_NO_SILK")
      (libsource (lib "eagle-import") (part "M01PTH_SMD_3.25X0.85MM_NO_SILK"))
    )
    (comp (ref "JP1041")
      (value "M01PTH_SMD_3.25X0.85MM_NO_SILK")
      (footprint "eagle-import:1X01_SMD_3.25X0.85MM_NO_SILK")
      (libsource (lib "eagle-import") (part "M01PTH_SMD_3.25X0.85MM_NO_SILK"))
    )
    (comp (ref "JP1042")
      (value "M01PTH_SMD_3.25X0.85MM_NO_SILK")
      (footprint "eagle-import:1X01_SMD_3.25X0.85MM_NO_SILK")
      (libsource (lib "eagle-import") (part "M01PTH_SMD_3.25X0.85MM_NO_SILK"))
    )
    (comp (ref "JP1043")
      (value "M01PTH_SMD_3.25X0.85MM_NO_SILK")
      (footprint "eagle-import:1X01_SMD_3.25X0.85MM_NO_SILK")
      (libsource (lib "eagle-import") (part "M01PTH_SMD_3.25X0.85MM_NO_SILK"))
    )
    (comp (ref "JP1044")
      (value "M01PTH_SMD_3.25X0.85MM_NO_SILK")
      (footprint "eagle-import:1X01_SMD_3.25X0.85MM_NO_SILK")
      (libsource (lib "eagle-import") (part "M01PTH_SMD_3.25X0.85MM_NO_SILK"))
    )
    (comp (ref "JP1045")
      (value "M01PTH_SMD_3.25X0.85MM_NO_SILK")
      (footprint "eagle-import:1X01_SMD_3.25X0.85MM_NO_SILK")
      (libsource (lib "eagle-import") (part "M01PTH_SMD_3.25X0.85MM_NO_SILK"))
    )
    (comp (ref "JP1046")
      (value "M01PTH_SMD_3.25X0.85MM_NO_SILK")
      (footprint "eagle-import:1X01_SMD_3.25X0.85MM_NO_SILK")
      (libsource (lib "eagle-import") (part "M01PTH_SMD_3.25X0.85MM_NO_SILK"))
    )
    (comp (ref "JP1047")
      (value "M01PTH_SMD_3.25X0.85MM_NO_SILK")
      (footprint "eagle-import:1X01_SMD_3.25X0.85MM_NO_SILK")
      (libsource (lib "eagle-import") (part "M01PTH_SMD_3.25X0.85MM_NO_SILK"))
    )
    (comp (ref "JP1048")
      (value "M01PTH_SMD_3.25X0.85MM_NO_SILK")
      (footprint "eagle-import:1X01_SMD_3.25X0.85MM_NO_SILK")
      (libsource (lib "eagle-import") (part "M01PTH_SMD_3.25X0.85MM_NO_SILK"))
    )
    (comp (ref "JP1049")
      (value "M01PTH_SMD_3.25X0.85MM_NO_SILK")
      (footprint "eagle-import:1X01_SMD_3.25X0.85MM_NO_SILK")
      (libsource (lib "eagle-import") (part "M01PTH_SMD_3.25X0.85MM_NO_SILK"))
    )
    (comp (ref "JP1050")
      (value "M01PTH_SMD_3.25X0.85MM_NO_SILK")
      (footprint "eagle-import:1X01_SMD_3.25X0.85MM_NO_SILK")
      (libsource (lib "eagle-import") (part "M01PTH_SMD_3.25X0.85MM_NO_SILK"))
    )
    (comp (ref "JP1051")
      (value "M01PTH_SMD_3.25X0.85MM_NO_SILK")
      (footprint "eagle-import:1X01_SMD_3.25X0.85MM_NO_SILK")
      (libsource (lib "eagle-import") (part "M01PTH_SMD_3.25X0.85MM_NO_SILK"))
    )
    (comp (ref "JP1052")
      (value "M01PTH_SMD_3.25X0.85MM_NO_SILK")
      (footprint "eagle-import:1X01_SMD_3.25X0.85MM_NO_SILK")
      (libsource (lib "eagle-import") (part "M01PTH_SMD_3.25X0.85MM_NO_SILK"))
    )
    (comp (ref "JP1053")
      (value "M01PTH_SMD_3.25X0.85MM_NO_SILK")
      (footprint "eagle-import:1X01_SMD_3.25X0.85MM_NO_SILK")
      (libsource (lib "eagle-import") (part "M01PTH_SMD_3.25X0.85MM_NO_SILK"))
    )
    (comp (ref "JP1054")
      (value "M01PTH_SMD_3.25X0.85MM_NO_SILK")
      (footprint "eagle-import:1X01_SMD_3.25X0.85MM_NO_SILK")
      (libsource (lib "eagle-import") (part "M01PTH_SMD_3.25X0.85MM_NO_SILK"))
    )
    (comp (ref "JP1055")
      (value "M01PTH_SMD_3.25X0.85MM_NO_SILK")
      (footprint "eagle-import:1X01_SMD_3.25X0.85MM_NO_SILK")
      (libsource (lib "eagle-import") (part "M01PTH_SMD_3.25X0.85MM_NO_SILK"))
    )
    (comp (ref "JP1056")
      (value "M01PTH_SMD_3.25X0.85MM_NO_SILK")
      (footprint "eagle-import:1X01_SMD_3.25X0.85MM_NO_SILK")
      (libsource (lib "eagle-import") (part "M01PTH_SMD_3.25X0.85MM_NO_SILK"))
    )
    (comp (ref "JP1057")
      (value "M01PTH_SMD_3.25X0.85MM_NO_SILK")
      (footprint "eagle-import:1X01_SMD_3.25X0.85MM_NO_SILK")
      (libsource (lib "eagle-import") (part "M01PTH_SMD_3.25X0.85MM_NO_SILK"))
    )
    (comp (ref "JP1058")
      (value "M01PTH_SMD_3.25X0.85MM_NO_SILK")
      (footprint "eagle-import:1X01_SMD_3.25X0.85MM_NO_SILK")
      (libsource (lib "eagle-import") (part "M01PTH_SMD_3.25X0.85MM_NO_SILK"))
    )
    (comp (ref "JP1059")
      (value "M01PTH_SMD_3.25X0.85MM_NO_SILK")
      (footprint "eagle-import:1X01_SMD_3.25X0.85MM_NO_SILK")
      (libsource (lib "eagle-import") (part "M01PTH_SMD_3.25X0.85MM_NO_SILK"))
    )
    (comp (ref "JP1060")
      (value "M01PTH_SMD_3.25X0.85MM_NO_SILK")
      (footprint "eagle-import:1X01_SMD_3.25X0.85MM_NO_SILK")
      (libsource (lib "eagle-import") (part "M01PTH_SMD_3.25X0.85MM_NO_SILK"))
    )
    (comp (ref "JP1061")
      (value "M01PTH_SMD_3.25X0.85MM_NO_SILK")
      (footprint "eagle-import:1X01_SMD_3.25X0.85MM_NO_SILK")
      (libsource (lib "eagle-import") (part "M01PTH_SMD_3.25X0.85MM_NO_SILK"))
    )
    (comp (ref "JP1062")
      (value "M01PTH_SMD_3.25X0.85MM_NO_SILK")
      (footprint "eagle-import:1X01_SMD_3.25X0.85MM_NO_SILK")
      (libsource (lib "eagle-import") (part "M01PTH_SMD_3.25X0.85MM_NO_SILK"))
    )
    (comp (ref "JP1063")
      (value "M01PTH_SMD_3.25X0.85MM_NO_SILK")
      (footprint "eagle-import:1X01_SMD_3.25X0.85MM_NO_SILK")
      (libsource (lib "eagle-import") (part "M01PTH_SMD_3.25X0.85MM_NO_SILK"))
    )
    (comp (ref "JP1064")
      (value "M01PTH_SMD_3.25X0.85MM_NO_SILK")
      (footprint "eagle-import:1X01_SMD_3.25X0.85MM_NO_SILK")
      (libsource (lib "eagle-import") (part "M01PTH_SMD_3.25X0.85MM_NO_SILK"))
    )
    (comp (ref "JP1065")
      (value "M01PTH_SMD_3.25X0.85MM_NO_SILK")
      (footprint "eagle-import:1X01_SMD_3.25X0.85MM_NO_SILK")
      (libsource (lib "eagle-import") (part "M01PTH_SMD_3.25X0.85MM_NO_SILK"))
    )
    (comp (ref "JP1066")
      (value "M01PTH_SMD_3.25X0.85MM_NO_SILK")
      (footprint "eagle-import:1X01_SMD_3.25X0.85MM_NO_SILK")
      (libsource (lib "eagle-import") (part "M01PTH_SMD_3.25X0.85MM_NO_SILK"))
    )
    (comp (ref "JP1067")
      (value "M01PTH_SMD_3.25X0.85MM_NO_SILK")
      (footprint "eagle-import:1X01_SMD_3.25X0.85MM_NO_SILK")
      (libsource (lib "eagle-import") (part "M01PTH_SMD_3.25X0.85MM_NO_SILK"))
    )
    (comp (ref "JP1068")
      (value "M01PTH_SMD_3.25X0.85MM_NO_SILK")
      (footprint "eagle-import:1X01_SMD_3.25X0.85MM_NO_SILK")
      (libsource (lib "eagle-import") (part "M01PTH_SMD_3.25X0.85MM_NO_SILK"))
    )
    (comp (ref "JP1069")
      (value "M01PTH_SMD_3.25X0.85MM_NO_SILK")
      (footprint "eagle-import:1X01_SMD_3.25X0.85MM_NO_SILK")
      (libsource (lib "eagle-import") (part "M01PTH_SMD_3.25X0.85MM_NO_SILK"))
    )
    (comp (ref "JP1070")
      (value "M01PTH_SMD_3.25X0.85MM_NO_SILK")
      (footprint "eagle-import:1X01_SMD_3.25X0.85MM_NO_SILK")
      (libsource (lib "eagle-import") (part "M01PTH_SMD_3.25X0.85MM_NO_SILK"))
    )
    (comp (ref "JP1071")
      (value "M01PTH_SMD_3.25X0.85MM_NO_SILK")
      (footprint "eagle-import:1X01_SMD_3.25X0.85MM_NO_SILK")
      (libsource (lib "eagle-import") (part "M01PTH_SMD_3.25X0.85MM_NO_SILK"))
    )
    (comp (ref "JP1072")
      (value "M01PTH_SMD_3.25X0.85MM_NO_SILK")
      (footprint "eagle-import:1X01_SMD_3.25X0.85MM_NO_SILK")
      (libsource (lib "eagle-import") (part "M01PTH_SMD_3.25X0.85MM_NO_SILK"))
    )
    (comp (ref "JP1073")
      (value "M01PTH_SMD_3.25X0.85MM_NO_SILK")
      (footprint "eagle-import:1X01_SMD_3.25X0.85MM_NO_SILK")
      (libsource (lib "eagle-import") (part "M01PTH_SMD_3.25X0.85MM_NO_SILK"))
    )
    (comp (ref "JP1074")
      (value "M01PTH_SMD_3.25X0.85MM_NO_SILK")
      (footprint "eagle-import:1X01_SMD_3.25X0.85MM_NO_SILK")
      (libsource (lib "eagle-import") (part "M01PTH_SMD_3.25X0.85MM_NO_SILK"))
    )
    (comp (ref "JP1075")
      (value "M01PTH_SMD_3.25X0.85MM_NO_SILK")
      (footprint "eagle-import:1X01_SMD_3.25X0.85MM_NO_SILK")
      (libsource (lib "eagle-import") (part "M01PTH_SMD_3.25X0.85MM_NO_SILK"))
    )
    (comp (ref "JP1076")
      (value "M01PTH_SMD_3.25X0.85MM_NO_SILK")
      (footprint "eagle-import:1X01_SMD_3.25X0.85MM_NO_SILK")
      (libsource (lib "eagle-import") (part "M01PTH_SMD_3.25X0.85MM_NO_SILK"))
    )
    (comp (ref "JP1077")
      (value "M01PTH_SMD_3.25X0.85MM_NO_SILK")
      (footprint "eagle-import:1X01_SMD_3.25X0.85MM_NO_SILK")
      (libsource (lib "eagle-import") (part "M01PTH_SMD_3.25X0.85MM_NO_SILK"))
    )
    (comp (ref "JP1078")
      (value "M01PTH_SMD_3.25X0.85MM_NO_SILK")
      (footprint "eagle-import:1X01_SMD_3.25X0.85MM_NO_SILK")
      (libsource (lib "eagle-import") (part "M01PTH_SMD_3.25X0.85MM_NO_SILK"))
    )
    (comp (ref "JP1079")
      (value "M01PTH_SMD_3.25X0.85MM_NO_SILK")
      (footprint "eagle-import:1X01_SMD_3.25X0.85MM_NO_SILK")
      (libsource (lib "eagle-import") (part "M01PTH_SMD_3.25X0.85MM_NO_SILK"))
    )
    (comp (ref "JP1080")
      (value "M01PTH_SMD_3.25X0.85MM_NO_SILK")
      (footprint "eagle-import:1X01_SMD_3.25X0.85MM_NO_SILK")
      (libsource (lib "eagle-import") (part "M01PTH_SMD_3.25X0.85MM_NO_SILK"))
    )
    (comp (ref "JP1081")
      (value "M01PTH_SMD_3.25X0.85MM_NO_SILK")
      (footprint "eagle-import:1X01_SMD_3.25X0.85MM_NO_SILK")
      (libsource (lib "eagle-import") (part "M01PTH_SMD_3.25X0.85MM_NO_SILK"))
    )
    (comp (ref "JP1082")
      (value "M01PTH_SMD_3.25X0.85MM_NO_SILK")
      (footprint "eagle-import:1X01_SMD_3.25X0.85MM_NO_SILK")
      (libsource (lib "eagle-import") (part "M01PTH_SMD_3.25X0.85MM_NO_SILK"))
    )
    (comp (ref "JP1083")
      (value "M01PTH_SMD_3.25X0.85MM_NO_SILK")
      (footprint "eagle-import:1X01_SMD_3.25X0.85MM_NO_SILK")
      (libsource (lib "eagle-import") (part "M01PTH_SMD_3.25X0.85MM_NO_SILK"))
    )
    (comp (ref "JP1084")
      (value "M01PTH_SMD_3.25X0.85MM_NO_SILK")
      (footprint "eagle-import:1X01_SMD_3.25X0.85MM_NO_SILK")
      (libsource (lib "eagle-import") (part "M01PTH_SMD_3.25X0.85MM_NO_SILK"))
    )
    (comp (ref "JP1085")
      (value "M01PTH_SMD_3.25X0.85MM_NO_SILK")
      (footprint "eagle-import:1X01_SMD_3.25X0.85MM_NO_SILK")
      (libsource (lib "eagle-import") (part "M01PTH_SMD_3.25X0.85MM_NO_SILK"))
    )
    (comp (ref "JP1086")
      (value "M01PTH_SMD_3.25X0.85MM_NO_SILK")
      (footprint "eagle-import:1X01_SMD_3.25X0.85MM_NO_SILK")
      (libsource (lib "eagle-import") (part "M01PTH_SMD_3.25X0.85MM_NO_SILK"))
    )
    (comp (ref "JP1087")
      (value "M01PTH_SMD_3.25X0.85MM_NO_SILK")
      (footprint "eagle-import:1X01_SMD_3.25X0.85MM_NO_SILK")
      (libsource (lib "eagle-import") (part "M01PTH_SMD_3.25X0.85MM_NO_SILK"))
    )
    (comp (ref "JP1088")
      (value "M01PTH_SMD_3.25X0.85MM_NO_SILK")
      (footprint "eagle-import:1X01_SMD_3.25X0.85MM_NO_SILK")
      (libsource (lib "eagle-import") (part "M01PTH_SMD_3.25X0.85MM_NO_SILK"))
    )
    (comp (ref "JP1089")
      (value "M01PTH_SMD_3.25X0.85MM_NO_SILK")
      (footprint "eagle-import:1X01_SMD_3.25X0.85MM_NO_SILK")
      (libsource (lib "eagle-import") (part "M01PTH_SMD_3.25X0.85MM_NO_SILK"))
    )
    (comp (ref "JP1090")
      (value "M01PTH_SMD_3.25X0.85MM_NO_SILK")
      (footprint "eagle-import:1X01_SMD_3.25X0.85MM_NO_SILK")
      (libsource (lib "eagle-import") (part "M01PTH_SMD_3.25X0.85MM_NO_SILK"))
    )
    (comp (ref "JP1091")
      (value "M01PTH_SMD_3.25X0.85MM_NO_SILK")
      (footprint "eagle-import:1X01_SMD_3.25X0.85MM_NO_SILK")
      (libsource (lib "eagle-import") (part "M01PTH_SMD_3.25X0.85MM_NO_SILK"))
    )
    (comp (ref "JP1092")
      (value "M01PTH_SMD_3.25X0.85MM_NO_SILK")
      (footprint "eagle-import:1X01_SMD_3.25X0.85MM_NO_SILK")
      (libsource (lib "eagle-import") (part "M01PTH_SMD_3.25X0.85MM_NO_SILK"))
    )
    (comp (ref "JP1093")
      (value "M01PTH_SMD_3.25X0.85MM_NO_SILK")
      (footprint "eagle-import:1X01_SMD_3.25X0.85MM_NO_SILK")
      (libsource (lib "eagle-import") (part "M01PTH_SMD_3.25X0.85MM_NO_SILK"))
    )
    (comp (ref "JP1094")
      (value "M01PTH_SMD_3.25X0.85MM_NO_SILK")
      (footprint "eagle-import:1X01_SMD_3.25X0.85MM_NO_SILK")
      (libsource (lib "eagle-import") (part "M01PTH_SMD_3.25X0.85MM_NO_SILK"))
    )
    (comp (ref "JP1095")
      (value "M01PTH_SMD_3.25X0.85MM_NO_SILK")
      (footprint "eagle-import:1X01_SMD_3.25X0.85MM_NO_SILK")
      (libsource (lib "eagle-import") (part "M01PTH_SMD_3.25X0.85MM_NO_SILK"))
    )
    (comp (ref "JP1096")
      (value "M01PTH_SMD_3.25X0.85MM_NO_SILK")
      (footprint "eagle-import:1X01_SMD_3.25X0.85MM_NO_SILK")
      (libsource (lib "eagle-import") (part "M01PTH_SMD_3.25X0.85MM_NO_SILK"))
    )
    (comp (ref "JP1097")
      (value "M01PTH_SMD_3.25X0.85MM_NO_SILK")
      (footprint "eagle-import:1X01_SMD_3.25X0.85MM_NO_SILK")
      (libsource (lib "eagle-import") (part "M01PTH_SMD_3.25X0.85MM_NO_SILK"))
    )
    (comp (ref "JP1098")
      (value "M01PTH_SMD_3.25X0.85MM_NO_SILK")
      (footprint "eagle-import:1X01_SMD_3.25X0.85MM_NO_SILK")
      (libsource (lib "eagle-import") (part "M01PTH_SMD_3.25X0.85MM_NO_SILK"))
    )
    (comp (ref "JP1099")
      (value "M01PTH_SMD_3.25X0.85MM_NO_SILK")
      (footprint "eagle-import:1X01_SMD_3.25X0.85MM_NO_SILK")
      (libsource (lib "eagle-import") (part "M01PTH_SMD_3.25X0.85MM_NO_SILK"))
    )
    (comp (ref "JP1100")
      (value "M01PTH_SMD_3.25X0.85MM_NO_SILK")
      (footprint "eagle-import:1X01_SMD_3.25X0.85MM_NO_SILK")
      (libsource (lib "eagle-import") (part "M01PTH_SMD_3.25X0.85MM_NO_SILK"))
    )
    (comp (ref "JP1101")
      (value "M01PTH_SMD_3.25X0.85MM_NO_SILK")
      (footprint "eagle-import:1X01_SMD_3.25X0.85MM_NO_SILK")
      (libsource (lib "eagle-import") (part "M01PTH_SMD_3.25X0.85MM_NO_SILK"))
    )
    (comp (ref "JP1102")
      (value "M01PTH_SMD_3.25X0.85MM_NO_SILK")
      (footprint "eagle-import:1X01_SMD_3.25X0.85MM_NO_SILK")
      (libsource (lib "eagle-import") (part "M01PTH_SMD_3.25X0.85MM_NO_SILK"))
    )
    (comp (ref "JP1103")
      (value "M01PTH_SMD_3.25X0.85MM_NO_SILK")
      (footprint "eagle-import:1X01_SMD_3.25X0.85MM_NO_SILK")
      (libsource (lib "eagle-import") (part "M01PTH_SMD_3.25X0.85MM_NO_SILK"))
    )
    (comp (ref "JP1104")
      (value "M01PTH_SMD_3.25X0.85MM_NO_SILK")
      (footprint "eagle-import:1X01_SMD_3.25X0.85MM_NO_SILK")
      (libsource (lib "eagle-import") (part "M01PTH_SMD_3.25X0.85MM_NO_SILK"))
    )
    (comp (ref "JP1105")
      (value "M01PTH_SMD_3.25X0.85MM_NO_SILK")
      (footprint "eagle-import:1X01_SMD_3.25X0.85MM_NO_SILK")
      (libsource (lib "eagle-import") (part "M01PTH_SMD_3.25X0.85MM_NO_SILK"))
    )
    (comp (ref "JP1106")
      (value "M01PTH_SMD_3.25X0.85MM_NO_SILK")
      (footprint "eagle-import:1X01_SMD_3.25X0.85MM_NO_SILK")
      (libsource (lib "eagle-import") (part "M01PTH_SMD_3.25X0.85MM_NO_SILK"))
    )
    (comp (ref "JP1107")
      (value "M01PTH_SMD_3.25X0.85MM_NO_SILK")
      (footprint "eagle-import:1X01_SMD_3.25X0.85MM_NO_SILK")
      (libsource (lib "eagle-import") (part "M01PTH_SMD_3.25X0.85MM_NO_SILK"))
    )
    (comp (ref "JP1108")
      (value "M01PTH_SMD_3.25X0.85MM_NO_SILK")
      (footprint "eagle-import:1X01_SMD_3.25X0.85MM_NO_SILK")
      (libsource (lib "eagle-import") (part "M01PTH_SMD_3.25X0.85MM_NO_SILK"))
    )
    (comp (ref "JP1109")
      (value "M01PTH_SMD_3.25X0.85MM_NO_SILK")
      (footprint "eagle-import:1X01_SMD_3.25X0.85MM_NO_SILK")
      (libsource (lib "eagle-import") (part "M01PTH_SMD_3.25X0.85MM_NO_SILK"))
    )
    (comp (ref "JP1110")
      (value "M01PTH_SMD_3.25X0.85MM_NO_SILK")
      (footprint "eagle-import:1X01_SMD_3.25X0.85MM_NO_SILK")
      (libsource (lib "eagle-import") (part "M01PTH_SMD_3.25X0.85MM_NO_SILK"))
    )
    (comp (ref "JP1111")
      (value "M01PTH_SMD_3.25X0.85MM_NO_SILK")
      (footprint "eagle-import:1X01_SMD_3.25X0.85MM_NO_SILK")
      (libsource (lib "eagle-import") (part "M01PTH_SMD_3.25X0.85MM_NO_SILK"))
    )
    (comp (ref "JP1112")
      (value "M01PTH_SMD_3.25X0.85MM_NO_SILK")
      (footprint "eagle-import:1X01_SMD_3.25X0.85MM_NO_SILK")
      (libsource (lib "eagle-import") (part "M01PTH_SMD_3.25X0.85MM_NO_SILK"))
    )
    (comp (ref "JP1113")
      (value "M01PTH_SMD_3.25X0.85MM_NO_SILK")
      (footprint "eagle-import:1X01_SMD_3.25X0.85MM_NO_SILK")
      (libsource (lib "eagle-import") (part "M01PTH_SMD_3.25X0.85MM_NO_SILK"))
    )
    (comp (ref "JP1114")
      (value "M01PTH_SMD_3.25X0.85MM_NO_SILK")
      (footprint "eagle-import:1X01_SMD_3.25X0.85MM_NO_SILK")
      (libsource (lib "eagle-import") (part "M01PTH_SMD_3.25X0.85MM_NO_SILK"))
    )
    (comp (ref "JP1115")
      (value "M01PTH_SMD_3.25X0.85MM_NO_SILK")
      (footprint "eagle-import:1X01_SMD_3.25X0.85MM_NO_SILK")
      (libsource (lib "eagle-import") (part "M01PTH_SMD_3.25X0.85MM_NO_SILK"))
    )
    (comp (ref "JP1116")
      (value "M01PTH_SMD_3.25X0.85MM_NO_SILK")
      (footprint "eagle-import:1X01_SMD_3.25X0.85MM_NO_SILK")
      (libsource (lib "eagle-import") (part "M01PTH_SMD_3.25X0.85MM_NO_SILK"))
    )
    (comp (ref "JP1117")
      (value "M01PTH_SMD_3.25X0.85MM_NO_SILK")
      (footprint "eagle-import:1X01_SMD_3.25X0.85MM_NO_SILK")
      (libsource (lib "eagle-import") (part "M01PTH_SMD_3.25X0.85MM_NO_SILK"))
    )
    (comp (ref "JP1118")
      (value "M01PTH_SMD_3.25X0.85MM_NO_SILK")
      (footprint "eagle-import:1X01_SMD_3.25X0.85MM_NO_SILK")
      (libsource (lib "eagle-import") (part "M01PTH_SMD_3.25X0.85MM_NO_SILK"))
    )
    (comp (ref "JP1119")
      (value "M01PTH_SMD_3.25X0.85MM_NO_SILK")
      (footprint "eagle-import:1X01_SMD_3.25X0.85MM_NO_SILK")
      (libsource (lib "eagle-import") (part "M01PTH_SMD_3.25X0.85MM_NO_SILK"))
    )
    (comp (ref "JP1120")
      (value "M01PTH_SMD_3.25X0.85MM_NO_SILK")
      (footprint "eagle-import:1X01_SMD_3.25X0.85MM_NO_SILK")
      (libsource (lib "eagle-import") (part "M01PTH_SMD_3.25X0.85MM_NO_SILK"))
    )
    (comp (ref "JP1121")
      (value "M01PTH_SMD_3.25X0.85MM_NO_SILK")
      (footprint "eagle-import:1X01_SMD_3.25X0.85MM_NO_SILK")
      (libsource (lib "eagle-import") (part "M01PTH_SMD_3.25X0.85MM_NO_SILK"))
    )
    (comp (ref "JP1122")
      (value "M01PTH_SMD_3.25X0.85MM_NO_SILK")
      (footprint "eagle-import:1X01_SMD_3.25X0.85MM_NO_SILK")
      (libsource (lib "eagle-import") (part "M01PTH_SMD_3.25X0.85MM_NO_SILK"))
    )
    (comp (ref "JP1123")
      (value "M01PTH_SMD_3.25X0.85MM_NO_SILK")
      (footprint "eagle-import:1X01_SMD_3.25X0.85MM_NO_SILK")
      (libsource (lib "eagle-import") (part "M01PTH_SMD_3.25X0.85MM_NO_SILK"))
    )
    (comp (ref "JP1124")
      (value "M01PTH_SMD_3.25X0.85MM_NO_SILK")
      (footprint "eagle-import:1X01_SMD_3.25X0.85MM_NO_SILK")
      (libsource (lib "eagle-import") (part "M01PTH_SMD_3.25X0.85MM_NO_SILK"))
    )
    (comp (ref "JP1125")
      (value "M01PTH_SMD_3.25X0.85MM_NO_SILK")
      (footprint "eagle-import:1X01_SMD_3.25X0.85MM_NO_SILK")
      (libsource (lib "eagle-import") (part "M01PTH_SMD_3.25X0.85MM_NO_SILK"))
    )
    (comp (ref "JP1126")
      (value "M01PTH_SMD_3.25X0.85MM_NO_SILK")
      (footprint "eagle-import:1X01_SMD_3.25X0.85MM_NO_SILK")
      (libsource (lib "eagle-import") (part "M01PTH_SMD_3.25X0.85MM_NO_SILK"))
    )
    (comp (ref "JP1127")
      (value "M01PTH_SMD_3.25X0.85MM_NO_SILK")
      (footprint "eagle-import:1X01_SMD_3.25X0.85MM_NO_SILK")
      (libsource (lib "eagle-import") (part "M01PTH_SMD_3.25X0.85MM_NO_SILK"))
    )
    (comp (ref "JP1128")
      (value "M01PTH_SMD_3.25X0.85MM_NO_SILK")
      (footprint "eagle-import:1X01_SMD_3.25X0.85MM_NO_SILK")
      (libsource (lib "eagle-import") (part "M01PTH_SMD_3.25X0.85MM_NO_SILK"))
    )
    (comp (ref "JP1129")
      (value "M01PTH_SMD_3.25X0.85MM_NO_SILK")
      (footprint "eagle-import:1X01_SMD_3.25X0.85MM_NO_SILK")
      (libsource (lib "eagle-import") (part "M01PTH_SMD_3.25X0.85MM_NO_SILK"))
    )
    (comp (ref "JP1130")
      (value "M01PTH_SMD_3.25X0.85MM_NO_SILK")
      (footprint "eagle-import:1X01_SMD_3.25X0.85MM_NO_SILK")
      (libsource (lib "eagle-import") (part "M01PTH_SMD_3.25X0.85MM_NO_SILK"))
    )
    (comp (ref "JP1131")
      (value "M01PTH_SMD_3.25X0.85MM_NO_SILK")
      (footprint "eagle-import:1X01_SMD_3.25X0.85MM_NO_SILK")
      (libsource (lib "eagle-import") (part "M01PTH_SMD_3.25X0.85MM_NO_SILK"))
    )
    (comp (ref "JP1132")
      (value "M01PTH_SMD_3.25X0.85MM_NO_SILK")
      (footprint "eagle-import:1X01_SMD_3.25X0.85MM_NO_SILK")
      (libsource (lib "eagle-import") (part "M01PTH_SMD_3.25X0.85MM_NO_SILK"))
    )
    (comp (ref "JP1133")
      (value "M01PTH_SMD_3.25X0.85MM_NO_SILK")
      (footprint "eagle-import:1X01_SMD_3.25X0.85MM_NO_SILK")
      (libsource (lib "eagle-import") (part "M01PTH_SMD_3.25X0.85MM_NO_SILK"))
    )
    (comp (ref "JP1134")
      (value "M01PTH_SMD_3.25X0.85MM_NO_SILK")
      (footprint "eagle-import:1X01_SMD_3.25X0.85MM_NO_SILK")
      (libsource (lib "eagle-import") (part "M01PTH_SMD_3.25X0.85MM_NO_SILK"))
    )
    (comp (ref "JP1135")
      (value "M01PTH_SMD_3.25X0.85MM_NO_SILK")
      (footprint "eagle-import:1X01_SMD_3.25X0.85MM_NO_SILK")
      (libsource (lib "eagle-import") (part "M01PTH_SMD_3.25X0.85MM_NO_SILK"))
    )
    (comp (ref "JP1136")
      (value "M01PTH_SMD_3.25X0.85MM_NO_SILK")
      (footprint "eagle-import:1X01_SMD_3.25X0.85MM_NO_SILK")
      (libsource (lib "eagle-import") (part "M01PTH_SMD_3.25X0.85MM_NO_SILK"))
    )
    (comp (ref "JP1137")
      (value "M01PTH_SMD_3.25X0.85MM_NO_SILK")
      (footprint "eagle-import:1X01_SMD_3.25X0.85MM_NO_SILK")
      (libsource (lib "eagle-import") (part "M01PTH_SMD_3.25X0.85MM_NO_SILK"))
    )
    (comp (ref "JP1138")
      (value "M01PTH_SMD_3.25X0.85MM_NO_SILK")
      (footprint "eagle-import:1X01_SMD_3.25X0.85MM_NO_SILK")
      (libsource (lib "eagle-import") (part "M01PTH_SMD_3.25X0.85MM_NO_SILK"))
    )
    (comp (ref "JP1139")
      (value "M01PTH_SMD_3.25X0.85MM_NO_SILK")
      (footprint "eagle-import:1X01_SMD_3.25X0.85MM_NO_SILK")
      (libsource (lib "eagle-import") (part "M01PTH_SMD_3.25X0.85MM_NO_SILK"))
    )
    (comp (ref "JP1140")
      (value "M01PTH_SMD_3.25X0.85MM_NO_SILK")
      (footprint "eagle-import:1X01_SMD_3.25X0.85MM_NO_SILK")
      (libsource (lib "eagle-import") (part "M01PTH_SMD_3.25X0.85MM_NO_SILK"))
    )
    (comp (ref "JP1141")
      (value "M01PTH_SMD_3.25X0.85MM_NO_SILK")
      (footprint "eagle-import:1X01_SMD_3.25X0.85MM_NO_SILK")
      (libsource (lib "eagle-import") (part "M01PTH_SMD_3.25X0.85MM_NO_SILK"))
    )
    (comp (ref "JP1142")
      (value "M01PTH_SMD_3.25X0.85MM_NO_SILK")
      (footprint "eagle-import:1X01_SMD_3.25X0.85MM_NO_SILK")
      (libsource (lib "eagle-import") (part "M01PTH_SMD_3.25X0.85MM_NO_SILK"))
    )
    (comp (ref "JP1143")
      (value "M01PTH_SMD_3.25X0.85MM_NO_SILK")
      (footprint "eagle-import:1X01_SMD_3.25X0.85MM_NO_SILK")
      (libsource (lib "eagle-import") (part "M01PTH_SMD_3.25X0.85MM_NO_SILK"))
    )
    (comp (ref "JP1144")
      (value "M01PTH_SMD_3.25X0.85MM_NO_SILK")
      (footprint "eagle-import:1X01_SMD_3.25X0.85MM_NO_SILK")
      (libsource (lib "eagle-import") (part "M01PTH_SMD_3.25X0.85MM_NO_SILK"))
    )
    (comp (ref "JP1145")
      (value "M01PTH_SMD_3.25X0.85MM_NO_SILK")
      (footprint "eagle-import:1X01_SMD_3.25X0.85MM_NO_SILK")
      (libsource (lib "eagle-import") (part "M01PTH_SMD_3.25X0.85MM_NO_SILK"))
    )
    (comp (ref "JP1146")
      (value "M01PTH_SMD_3.25X0.85MM_NO_SILK")
      (footprint "eagle-import:1X01_SMD_3.25X0.85MM_NO_SILK")
      (libsource (lib "eagle-import") (part "M01PTH_SMD_3.25X0.85MM_NO_SILK"))
    )
    (comp (ref "JP1147")
      (value "M01PTH_SMD_3.25X0.85MM_NO_SILK")
      (footprint "eagle-import:1X01_SMD_3.25X0.85MM_NO_SILK")
      (libsource (lib "eagle-import") (part "M01PTH_SMD_3.25X0.85MM_NO_SILK"))
    )
    (comp (ref "JP1148")
      (value "M01PTH_SMD_3.25X0.85MM_NO_SILK")
      (footprint "eagle-import:1X01_SMD_3.25X0.85MM_NO_SILK")
      (libsource (lib "eagle-import") (part "M01PTH_SMD_3.25X0.85MM_NO_SILK"))
    )
    (comp (ref "JP1149")
      (value "M01PTH_SMD_3.25X0.85MM_NO_SILK")
      (footprint "eagle-import:1X01_SMD_3.25X0.85MM_NO_SILK")
      (libsource (lib "eagle-import") (part "M01PTH_SMD_3.25X0.85MM_NO_SILK"))
    )
    (comp (ref "JP1150")
      (value "M01PTH_SMD_3.25X0.85MM_NO_SILK")
      (footprint "eagle-import:1X01_SMD_3.25X0.85MM_NO_SILK")
      (libsource (lib "eagle-import") (part "M01PTH_SMD_3.25X0.85MM_NO_SILK"))
    )
    (comp (ref "JP1151")
      (value "M01PTH_SMD_3.25X0.85MM_NO_SILK")
      (footprint "eagle-import:1X01_SMD_3.25X0.85MM_NO_SILK")
      (libsource (lib "eagle-import") (part "M01PTH_SMD_3.25X0.85MM_NO_SILK"))
    )
    (comp (ref "JP1152")
      (value "M01PTH_SMD_3.25X0.85MM_NO_SILK")
      (footprint "eagle-import:1X01_SMD_3.25X0.85MM_NO_SILK")
      (libsource (lib "eagle-import") (part "M01PTH_SMD_3.25X0.85MM_NO_SILK"))
    )
    (comp (ref "JP1153")
      (value "M01PTH_SMD_3.25X0.85MM_NO_SILK")
      (footprint "eagle-import:1X01_SMD_3.25X0.85MM_NO_SILK")
      (libsource (lib "eagle-import") (part "M01PTH_SMD_3.25X0.85MM_NO_SILK"))
    )
    (comp (ref "JP1154")
      (value "M01PTH_SMD_3.25X0.85MM_NO_SILK")
      (footprint "eagle-import:1X01_SMD_3.25X0.85MM_NO_SILK")
      (libsource (lib "eagle-import") (part "M01PTH_SMD_3.25X0.85MM_NO_SILK"))
    )
    (comp (ref "JP1155")
      (value "M01PTH_SMD_3.25X0.85MM_NO_SILK")
      (footprint "eagle-import:1X01_SMD_3.25X0.85MM_NO_SILK")
      (libsource (lib "eagle-import") (part "M01PTH_SMD_3.25X0.85MM_NO_SILK"))
    )
    (comp (ref "JP1156")
      (value "M01PTH_SMD_3.25X0.85MM_NO_SILK")
      (footprint "eagle-import:1X01_SMD_3.25X0.85MM_NO_SILK")
      (libsource (lib "eagle-import") (part "M01PTH_SMD_3.25X0.85MM_NO_SILK"))
    )
    (comp (ref "JP1157")
      (value "M01PTH_SMD_3.25X0.85MM_NO_SILK")
      (footprint "eagle-import:1X01_SMD_3.25X0.85MM_NO_SILK")
      (libsource (lib "eagle-import") (part "M01PTH_SMD_3.25X0.85MM_NO_SILK"))
    )
    (comp (ref "JP1158")
      (value "M01PTH_SMD_3.25X0.85MM_NO_SILK")
      (footprint "eagle-import:1X01_SMD_3.25X0.85MM_NO_SILK")
      (libsource (lib "eagle-import") (part "M01PTH_SMD_3.25X0.85MM_NO_SILK"))
    )
    (comp (ref "JP1159")
      (value "M01PTH_SMD_3.25X0.85MM_NO_SILK")
      (footprint "eagle-import:1X01_SMD_3.25X0.85MM_NO_SILK")
      (libsource (lib "eagle-import") (part "M01PTH_SMD_3.25X0.85MM_NO_SILK"))
    )
    (comp (ref "JP1160")
      (value "M01PTH_SMD_3.25X0.85MM_NO_SILK")
      (footprint "eagle-import:1X01_SMD_3.25X0.85MM_NO_SILK")
      (libsource (lib "eagle-import") (part "M01PTH_SMD_3.25X0.85MM_NO_SILK"))
    )
    (comp (ref "JP1161")
      (value "M01PTH_SMD_3.25X0.85MM_NO_SILK")
      (footprint "eagle-import:1X01_SMD_3.25X0.85MM_NO_SILK")
      (libsource (lib "eagle-import") (part "M01PTH_SMD_3.25X0.85MM_NO_SILK"))
    )
    (comp (ref "JP1162")
      (value "M01PTH_SMD_3.25X0.85MM_NO_SILK")
      (footprint "eagle-import:1X01_SMD_3.25X0.85MM_NO_SILK")
      (libsource (lib "eagle-import") (part "M01PTH_SMD_3.25X0.85MM_NO_SILK"))
    )
    (comp (ref "JP1163")
      (value "M01PTH_SMD_3.25X0.85MM_NO_SILK")
      (footprint "eagle-import:1X01_SMD_3.25X0.85MM_NO_SILK")
      (libsource (lib "eagle-import") (part "M01PTH_SMD_3.25X0.85MM_NO_SILK"))
    )
    (comp (ref "JP1164")
      (value "M01PTH_SMD_3.25X0.85MM_NO_SILK")
      (footprint "eagle-import:1X01_SMD_3.25X0.85MM_NO_SILK")
      (libsource (lib "eagle-import") (part "M01PTH_SMD_3.25X0.85MM_NO_SILK"))
    )
    (comp (ref "JP1165")
      (value "M01PTH_SMD_3.25X0.85MM_NO_SILK")
      (footprint "eagle-import:1X01_SMD_3.25X0.85MM_NO_SILK")
      (libsource (lib "eagle-import") (part "M01PTH_SMD_3.25X0.85MM_NO_SILK"))
    )
    (comp (ref "JP1166")
      (value "M01PTH_SMD_3.25X0.85MM_NO_SILK")
      (footprint "eagle-import:1X01_SMD_3.25X0.85MM_NO_SILK")
      (libsource (lib "eagle-import") (part "M01PTH_SMD_3.25X0.85MM_NO_SILK"))
    )
    (comp (ref "JP1167")
      (value "M01PTH_SMD_3.25X0.85MM_NO_SILK")
      (footprint "eagle-import:1X01_SMD_3.25X0.85MM_NO_SILK")
      (libsource (lib "eagle-import") (part "M01PTH_SMD_3.25X0.85MM_NO_SILK"))
    )
    (comp (ref "JP1168")
      (value "M01PTH_SMD_3.25X0.85MM_NO_SILK")
      (footprint "eagle-import:1X01_SMD_3.25X0.85MM_NO_SILK")
      (libsource (lib "eagle-import") (part "M01PTH_SMD_3.25X0.85MM_NO_SILK"))
    )
    (comp (ref "JP1169")
      (value "M01PTH_SMD_3.25X0.85MM_NO_SILK")
      (footprint "eagle-import:1X01_SMD_3.25X0.85MM_NO_SILK")
      (libsource (lib "eagle-import") (part "M01PTH_SMD_3.25X0.85MM_NO_SILK"))
    )
    (comp (ref "JP1170")
      (value "M01PTH_SMD_3.25X0.85MM_NO_SILK")
      (footprint "eagle-import:1X01_SMD_3.25X0.85MM_NO_SILK")
      (libsource (lib "eagle-import") (part "M01PTH_SMD_3.25X0.85MM_NO_SILK"))
    )
    (comp (ref "JP1171")
      (value "M01PTH_SMD_3.25X0.85MM_NO_SILK")
      (footprint "eagle-import:1X01_SMD_3.25X0.85MM_NO_SILK")
      (libsource (lib "eagle-import") (part "M01PTH_SMD_3.25X0.85MM_NO_SILK"))
    )
    (comp (ref "JP1172")
      (value "M01PTH_SMD_3.25X0.85MM_NO_SILK")
      (footprint "eagle-import:1X01_SMD_3.25X0.85MM_NO_SILK")
      (libsource (lib "eagle-import") (part "M01PTH_SMD_3.25X0.85MM_NO_SILK"))
    )
    (comp (ref "JP1173")
      (value "M01PTH_SMD_3.25X0.85MM_NO_SILK")
      (footprint "eagle-import:1X01_SMD_3.25X0.85MM_NO_SILK")
      (libsource (lib "eagle-import") (part "M01PTH_SMD_3.25X0.85MM_NO_SILK"))
    )
    (comp (ref "JP1174")
      (value "M01PTH_SMD_3.25X0.85MM_NO_SILK")
      (footprint "eagle-import:1X01_SMD_3.25X0.85MM_NO_SILK")
      (libsource (lib "eagle-import") (part "M01PTH_SMD_3.25X0.85MM_NO_SILK"))
    )
    (comp (ref "JP1175")
      (value "M01PTH_SMD_3.25X0.85MM_NO_SILK")
      (footprint "eagle-import:1X01_SMD_3.25X0.85MM_NO_SILK")
      (libsource (lib "eagle-import") (part "M01PTH_SMD_3.25X0.85MM_NO_SILK"))
    )
    (comp (ref "JP1176")
      (value "M01PTH_SMD_3.25X0.85MM_NO_SILK")
      (footprint "eagle-import:1X01_SMD_3.25X0.85MM_NO_SILK")
      (libsource (lib "eagle-import") (part "M01PTH_SMD_3.25X0.85MM_NO_SILK"))
    )
    (comp (ref "JP1177")
      (value "M01PTH_SMD_3.25X0.85MM_NO_SILK")
      (footprint "eagle-import:1X01_SMD_3.25X0.85MM_NO_SILK")
      (libsource (lib "eagle-import") (part "M01PTH_SMD_3.25X0.85MM_NO_SILK"))
    )
    (comp (ref "JP1178")
      (value "M01PTH_SMD_3.25X0.85MM_NO_SILK")
      (footprint "eagle-import:1X01_SMD_3.25X0.85MM_NO_SILK")
      (libsource (lib "eagle-import") (part "M01PTH_SMD_3.25X0.85MM_NO_SILK"))
    )
    (comp (ref "JP1179")
      (value "M01PTH_SMD_3.25X0.85MM_NO_SILK")
      (footprint "eagle-import:1X01_SMD_3.25X0.85MM_NO_SILK")
      (libsource (lib "eagle-import") (part "M01PTH_SMD_3.25X0.85MM_NO_SILK"))
    )
    (comp (ref "JP1180")
      (value "M01PTH_SMD_3.25X0.85MM_NO_SILK")
      (footprint "eagle-import:1X01_SMD_3.25X0.85MM_NO_SILK")
      (libsource (lib "eagle-import") (part "M01PTH_SMD_3.25X0.85MM_NO_SILK"))
    )
    (comp (ref "JP1181")
      (value "M01PTH_SMD_3.25X0.85MM_NO_SILK")
      (footprint "eagle-import:1X01_SMD_3.25X0.85MM_NO_SILK")
      (libsource (lib "eagle-import") (part "M01PTH_SMD_3.25X0.85MM_NO_SILK"))
    )
    (comp (ref "JP1182")
      (value "M01PTH_SMD_3.25X0.85MM_NO_SILK")
      (footprint "eagle-import:1X01_SMD_3.25X0.85MM_NO_SILK")
      (libsource (lib "eagle-import") (part "M01PTH_SMD_3.25X0.85MM_NO_SILK"))
    )
    (comp (ref "JP1183")
      (value "M01PTH_SMD_3.25X0.85MM_NO_SILK")
      (footprint "eagle-import:1X01_SMD_3.25X0.85MM_NO_SILK")
      (libsource (lib "eagle-import") (part "M01PTH_SMD_3.25X0.85MM_NO_SILK"))
    )
    (comp (ref "JP1184")
      (value "M01PTH_SMD_3.25X0.85MM_NO_SILK")
      (footprint "eagle-import:1X01_SMD_3.25X0.85MM_NO_SILK")
      (libsource (lib "eagle-import") (part "M01PTH_SMD_3.25X0.85MM_NO_SILK"))
    )
    (comp (ref "JP1185")
      (value "M01PTH_SMD_3.25X0.85MM_NO_SILK")
      (footprint "eagle-import:1X01_SMD_3.25X0.85MM_NO_SILK")
      (libsource (lib "eagle-import") (part "M01PTH_SMD_3.25X0.85MM_NO_SILK"))
    )
    (comp (ref "JP1186")
      (value "M01PTH_SMD_3.25X0.85MM_NO_SILK")
      (footprint "eagle-import:1X01_SMD_3.25X0.85MM_NO_SILK")
      (libsource (lib "eagle-import") (part "M01PTH_SMD_3.25X0.85MM_NO_SILK"))
    )
    (comp (ref "JP1187")
      (value "M01PTH_SMD_3.25X0.85MM_NO_SILK")
      (footprint "eagle-import:1X01_SMD_3.25X0.85MM_NO_SILK")
      (libsource (lib "eagle-import") (part "M01PTH_SMD_3.25X0.85MM_NO_SILK"))
    )
    (comp (ref "JP1188")
      (value "M01PTH_SMD_3.25X0.85MM_NO_SILK")
      (footprint "eagle-import:1X01_SMD_3.25X0.85MM_NO_SILK")
      (libsource (lib "eagle-import") (part "M01PTH_SMD_3.25X0.85MM_NO_SILK"))
    )
    (comp (ref "JP1189")
      (value "M01PTH_SMD_3.25X0.85MM_NO_SILK")
      (footprint "eagle-import:1X01_SMD_3.25X0.85MM_NO_SILK")
      (libsource (lib "eagle-import") (part "M01PTH_SMD_3.25X0.85MM_NO_SILK"))
    )
    (comp (ref "JP1190")
      (value "M01PTH_SMD_3.25X0.85MM_NO_SILK")
      (footprint "eagle-import:1X01_SMD_3.25X0.85MM_NO_SILK")
      (libsource (lib "eagle-import") (part "M01PTH_SMD_3.25X0.85MM_NO_SILK"))
    )
    (comp (ref "JP1191")
      (value "M01PTH_SMD_3.25X0.85MM_NO_SILK")
      (footprint "eagle-import:1X01_SMD_3.25X0.85MM_NO_SILK")
      (libsource (lib "eagle-import") (part "M01PTH_SMD_3.25X0.85MM_NO_SILK"))
    )
    (comp (ref "JP1192")
      (value "M01PTH_SMD_3.25X0.85MM_NO_SILK")
      (footprint "eagle-import:1X01_SMD_3.25X0.85MM_NO_SILK")
      (libsource (lib "eagle-import") (part "M01PTH_SMD_3.25X0.85MM_NO_SILK"))
    )
    (comp (ref "JP1193")
      (value "M01PTH_SMD_3.25X0.85MM_NO_SILK")
      (footprint "eagle-import:1X01_SMD_3.25X0.85MM_NO_SILK")
      (libsource (lib "eagle-import") (part "M01PTH_SMD_3.25X0.85MM_NO_SILK"))
    )
    (comp (ref "JP1194")
      (value "M01PTH_SMD_3.25X0.85MM_NO_SILK")
      (footprint "eagle-import:1X01_SMD_3.25X0.85MM_NO_SILK")
      (libsource (lib "eagle-import") (part "M01PTH_SMD_3.25X0.85MM_NO_SILK"))
    )
    (comp (ref "JP1195")
      (value "M01PTH_SMD_3.25X0.85MM_NO_SILK")
      (footprint "eagle-import:1X01_SMD_3.25X0.85MM_NO_SILK")
      (libsource (lib "eagle-import") (part "M01PTH_SMD_3.25X0.85MM_NO_SILK"))
    )
    (comp (ref "JP1196")
      (value "M01PTH_SMD_3.25X0.85MM_NO_SILK")
      (footprint "eagle-import:1X01_SMD_3.25X0.85MM_NO_SILK")
      (libsource (lib "eagle-import") (part "M01PTH_SMD_3.25X0.85MM_NO_SILK"))
    )
    (comp (ref "JP1197")
      (value "M01PTH_SMD_3.25X0.85MM_NO_SILK")
      (footprint "eagle-import:1X01_SMD_3.25X0.85MM_NO_SILK")
      (libsource (lib "eagle-import") (part "M01PTH_SMD_3.25X0.85MM_NO_SILK"))
    )
    (comp (ref "JP1198")
      (value "M01PTH_SMD_3.25X0.85MM_NO_SILK")
      (footprint "eagle-import:1X01_SMD_3.25X0.85MM_NO_SILK")
      (libsource (lib "eagle-import") (part "M01PTH_SMD_3.25X0.85MM_NO_SILK"))
    )
    (comp (ref "JP1199")
      (value "M01PTH_SMD_3.25X0.85MM_NO_SILK")
      (footprint "eagle-import:1X01_SMD_3.25X0.85MM_NO_SILK")
      (libsource (lib "eagle-import") (part "M01PTH_SMD_3.25X0.85MM_NO_SILK"))
    )
    (comp (ref "JP1200")
      (value "M01PTH_SMD_3.25X0.85MM_NO_SILK")
      (footprint "eagle-import:1X01_SMD_3.25X0.85MM_NO_SILK")
      (libsource (lib "eagle-import") (part "M01PTH_SMD_3.25X0.85MM_NO_SILK"))
    )
  )
  (nets
    (net (code "1") (name "/0_1440337657") (class "Default")
      (node (ref "JP1") (pin "1") (pinfunction "1_1") (pintype "passive"))
      (node (ref "JP961") (pin "P$1") (pinfunction "1_P$1") (pintype "passive"))
    )
    (net (code "2") (name "/0_1440337842") (class "Default")
      (node (ref "JP1151") (pin "P$1") (pinfunction "1_P$1") (pintype "passive"))
      (node (ref "JP5") (pin "1") (pinfunction "1_1") (pintype "passive"))
    )
    (net (code "3") (name "/0_1440337868") (class "Default")
      (node (ref "JP1159") (pin "P$1") (pinfunction "1_P$1") (pintype "passive"))
      (node (ref "JP6") (pin "1") (pinfunction "1_1") (pintype "passive"))
    )
    (net (code "4") (name "/1_1440337657") (class "Default")
      (node (ref "JP11") (pin "1") (pinfunction "1_1") (pintype "passive"))
      (node (ref "JP963") (pin "P$1") (pinfunction "1_P$1") (pintype "passive"))
    )
    (net (code "5") (name "/1_1440337842") (class "Default")
      (node (ref "JP1152") (pin "P$1") (pinfunction "1_P$1") (pintype "passive"))
      (node (ref "JP15") (pin "1") (pinfunction "1_1") (pintype "passive"))
    )
    (net (code "6") (name "/1_1440337868") (class "Default")
      (node (ref "JP1160") (pin "P$1") (pinfunction "1_P$1") (pintype "passive"))
      (node (ref "JP16") (pin "1") (pinfunction "1_1") (pintype "passive"))
    )
    (net (code "7") (name "/2_1440337657") (class "Default")
      (node (ref "JP21") (pin "1") (pinfunction "1_1") (pintype "passive"))
      (node (ref "JP965") (pin "P$1") (pinfunction "1_P$1") (pintype "passive"))
    )
    (net (code "8") (name "/2_1440337842") (class "Default")
      (node (ref "JP1181") (pin "P$1") (pinfunction "1_P$1") (pintype "passive"))
      (node (ref "JP295") (pin "1") (pinfunction "1_1") (pintype "passive"))
    )
    (net (code "9") (name "/2_1440337868") (class "Default")
      (node (ref "JP1189") (pin "P$1") (pinfunction "1_P$1") (pintype "passive"))
      (node (ref "JP296") (pin "1") (pinfunction "1_1") (pintype "passive"))
    )
    (net (code "10") (name "/3_1440337657") (class "Default")
      (node (ref "JP31") (pin "1") (pinfunction "1_1") (pintype "passive"))
      (node (ref "JP967") (pin "P$1") (pinfunction "1_P$1") (pintype "passive"))
    )
    (net (code "11") (name "/3_1440337842") (class "Default")
      (node (ref "JP1182") (pin "P$1") (pinfunction "1_P$1") (pintype "passive"))
      (node (ref "JP285") (pin "1") (pinfunction "1_1") (pintype "passive"))
    )
    (net (code "12") (name "/3_1440337868") (class "Default")
      (node (ref "JP1190") (pin "P$1") (pinfunction "1_P$1") (pintype "passive"))
      (node (ref "JP286") (pin "1") (pinfunction "1_1") (pintype "passive"))
    )
    (net (code "13") (name "/4_1440337657") (class "Default")
      (node (ref "JP41") (pin "1") (pinfunction "1_1") (pintype "passive"))
      (node (ref "JP969") (pin "P$1") (pinfunction "1_P$1") (pintype "passive"))
    )
    (net (code "14") (name "/4_1440337842") (class "Default")
      (node (ref "JP1150") (pin "P$1") (pinfunction "1_P$1") (pintype "passive"))
      (node (ref "JP25") (pin "1") (pinfunction "1_1") (pintype "passive"))
    )
    (net (code "15") (name "/4_1440337868") (class "Default")
      (node (ref "JP1158") (pin "P$1") (pinfunction "1_P$1") (pintype "passive"))
      (node (ref "JP26") (pin "1") (pinfunction "1_1") (pintype "passive"))
    )
    (net (code "16") (name "/5_1440337657") (class "Default")
      (node (ref "JP51") (pin "1") (pinfunction "1_1") (pintype "passive"))
      (node (ref "JP971") (pin "P$1") (pinfunction "1_P$1") (pintype "passive"))
    )
    (net (code "17") (name "/5_1440337842") (class "Default")
      (node (ref "JP1153") (pin "P$1") (pinfunction "1_P$1") (pintype "passive"))
      (node (ref "JP35") (pin "1") (pinfunction "1_1") (pintype "passive"))
    )
    (net (code "18") (name "/5_1440337868") (class "Default")
      (node (ref "JP1161") (pin "P$1") (pinfunction "1_P$1") (pintype "passive"))
      (node (ref "JP36") (pin "1") (pinfunction "1_1") (pintype "passive"))
    )
    (net (code "19") (name "/6_1440337657") (class "Default")
      (node (ref "JP61") (pin "1") (pinfunction "1_1") (pintype "passive"))
      (node (ref "JP973") (pin "P$1") (pinfunction "1_P$1") (pintype "passive"))
    )
    (net (code "20") (name "/6_1440337842") (class "Default")
      (node (ref "JP1180") (pin "P$1") (pinfunction "1_P$1") (pintype "passive"))
      (node (ref "JP275") (pin "1") (pinfunction "1_1") (pintype "passive"))
    )
    (net (code "21") (name "/6_1440337868") (class "Default")
      (node (ref "JP1188") (pin "P$1") (pinfunction "1_P$1") (pintype "passive"))
      (node (ref "JP276") (pin "1") (pinfunction "1_1") (pintype "passive"))
    )
    (net (code "22") (name "/7_1440337657") (class "Default")
      (node (ref "JP71") (pin "1") (pinfunction "1_1") (pintype "passive"))
      (node (ref "JP975") (pin "P$1") (pinfunction "1_P$1") (pintype "passive"))
    )
    (net (code "23") (name "/7_1440337842") (class "Default")
      (node (ref "JP1183") (pin "P$1") (pinfunction "1_P$1") (pintype "passive"))
      (node (ref "JP265") (pin "1") (pinfunction "1_1") (pintype "passive"))
    )
    (net (code "24") (name "/7_1440337868") (class "Default")
      (node (ref "JP1191") (pin "P$1") (pinfunction "1_P$1") (pintype "passive"))
      (node (ref "JP266") (pin "1") (pinfunction "1_1") (pintype "passive"))
    )
    (net (code "25") (name "/8_1440337657") (class "Default")
      (node (ref "JP81") (pin "1") (pinfunction "1_1") (pintype "passive"))
      (node (ref "JP977") (pin "P$1") (pinfunction "1_P$1") (pintype "passive"))
    )
    (net (code "26") (name "/8_1440337842") (class "Default")
      (node (ref "JP1149") (pin "P$1") (pinfunction "1_P$1") (pintype "passive"))
      (node (ref "JP45") (pin "1") (pinfunction "1_1") (pintype "passive"))
    )
    (net (code "27") (name "/8_1440337868") (class "Default")
      (node (ref "JP1157") (pin "P$1") (pinfunction "1_P$1") (pintype "passive"))
      (node (ref "JP46") (pin "1") (pinfunction "1_1") (pintype "passive"))
    )
    (net (code "28") (name "/9_1440337657") (class "Default")
      (node (ref "JP91") (pin "1") (pinfunction "1_1") (pintype "passive"))
      (node (ref "JP979") (pin "P$1") (pinfunction "1_P$1") (pintype "passive"))
    )
    (net (code "29") (name "/9_1440337842") (class "Default")
      (node (ref "JP1154") (pin "P$1") (pinfunction "1_P$1") (pintype "passive"))
      (node (ref "JP55") (pin "1") (pinfunction "1_1") (pintype "passive"))
    )
    (net (code "30") (name "/9_1440337868") (class "Default")
      (node (ref "JP1162") (pin "P$1") (pinfunction "1_P$1") (pintype "passive"))
      (node (ref "JP56") (pin "1") (pinfunction "1_1") (pintype "passive"))
    )
    (net (code "31") (name "/10_1440337657") (class "Default")
      (node (ref "JP101") (pin "1") (pinfunction "1_1") (pintype "passive"))
      (node (ref "JP981") (pin "P$1") (pinfunction "1_P$1") (pintype "passive"))
    )
    (net (code "32") (name "/10_1440337842") (class "Default")
      (node (ref "JP1179") (pin "P$1") (pinfunction "1_P$1") (pintype "passive"))
      (node (ref "JP255") (pin "1") (pinfunction "1_1") (pintype "passive"))
    )
    (net (code "33") (name "/10_1440337868") (class "Default")
      (node (ref "JP1187") (pin "P$1") (pinfunction "1_P$1") (pintype "passive"))
      (node (ref "JP256") (pin "1") (pinfunction "1_1") (pintype "passive"))
    )
    (net (code "34") (name "/11_1440337657") (class "Default")
      (node (ref "JP111") (pin "1") (pinfunction "1_1") (pintype "passive"))
      (node (ref "JP983") (pin "P$1") (pinfunction "1_P$1") (pintype "passive"))
    )
    (net (code "35") (name "/11_1440337842") (class "Default")
      (node (ref "JP1184") (pin "P$1") (pinfunction "1_P$1") (pintype "passive"))
      (node (ref "JP245") (pin "1") (pinfunction "1_1") (pintype "passive"))
    )
    (net (code "36") (name "/11_1440337868") (class "Default")
      (node (ref "JP1192") (pin "P$1") (pinfunction "1_P$1") (pintype "passive"))
      (node (ref "JP246") (pin "1") (pinfunction "1_1") (pintype "passive"))
    )
    (net (code "37") (name "/12_1440337657") (class "Default")
      (node (ref "JP121") (pin "1") (pinfunction "1_1") (pintype "passive"))
      (node (ref "JP985") (pin "P$1") (pinfunction "1_P$1") (pintype "passive"))
    )
    (net (code "38") (name "/12_1440337842") (class "Default")
      (node (ref "JP1148") (pin "P$1") (pinfunction "1_P$1") (pintype "passive"))
      (node (ref "JP65") (pin "1") (pinfunction "1_1") (pintype "passive"))
    )
    (net (code "39") (name "/12_1440337868") (class "Default")
      (node (ref "JP1156") (pin "P$1") (pinfunction "1_P$1") (pintype "passive"))
      (node (ref "JP66") (pin "1") (pinfunction "1_1") (pintype "passive"))
    )
    (net (code "40") (name "/13_1440337657") (class "Default")
      (node (ref "JP131") (pin "1") (pinfunction "1_1") (pintype "passive"))
      (node (ref "JP987") (pin "P$1") (pinfunction "1_P$1") (pintype "passive"))
    )
    (net (code "41") (name "/13_1440337842") (class "Default")
      (node (ref "JP1155") (pin "P$1") (pinfunction "1_P$1") (pintype "passive"))
      (node (ref "JP75") (pin "1") (pinfunction "1_1") (pintype "passive"))
    )
    (net (code "42") (name "/13_1440337868") (class "Default")
      (node (ref "JP1163") (pin "P$1") (pinfunction "1_P$1") (pintype "passive"))
      (node (ref "JP76") (pin "1") (pinfunction "1_1") (pintype "passive"))
    )
    (net (code "43") (name "/14_1440337657") (class "Default")
      (node (ref "JP141") (pin "1") (pinfunction "1_1") (pintype "passive"))
      (node (ref "JP989") (pin "P$1") (pinfunction "1_P$1") (pintype "passive"))
    )
    (net (code "44") (name "/14_1440337842") (class "Default")
      (node (ref "JP1178") (pin "P$1") (pinfunction "1_P$1") (pintype "passive"))
      (node (ref "JP235") (pin "1") (pinfunction "1_1") (pintype "passive"))
    )
    (net (code "45") (name "/14_1440337868") (class "Default")
      (node (ref "JP1164") (pin "P$1") (pinfunction "1_P$1") (pintype "passive"))
      (node (ref "JP86") (pin "1") (pinfunction "1_1") (pintype "passive"))
    )
    (net (code "46") (name "/15_1440337657") (class "Default")
      (node (ref "JP151") (pin "1") (pinfunction "1_1") (pintype "passive"))
      (node (ref "JP991") (pin "P$1") (pinfunction "1_P$1") (pintype "passive"))
    )
    (net (code "47") (name "/15_1440337842") (class "Default")
      (node (ref "JP1185") (pin "P$1") (pinfunction "1_P$1") (pintype "passive"))
      (node (ref "JP225") (pin "1") (pinfunction "1_1") (pintype "passive"))
    )
    (net (code "48") (name "/15_1440337868") (class "Default")
      (node (ref "JP1165") (pin "P$1") (pinfunction "1_P$1") (pintype "passive"))
      (node (ref "JP96") (pin "1") (pinfunction "1_1") (pintype "passive"))
    )
    (net (code "49") (name "/16_1440337657") (class "Default")
      (node (ref "JP161") (pin "1") (pinfunction "1_1") (pintype "passive"))
      (node (ref "JP993") (pin "P$1") (pinfunction "1_P$1") (pintype "passive"))
    )
    (net (code "50") (name "/16_1440337842") (class "Default")
      (node (ref "JP1147") (pin "P$1") (pinfunction "1_P$1") (pintype "passive"))
      (node (ref "JP85") (pin "1") (pinfunction "1_1") (pintype "passive"))
    )
    (net (code "51") (name "/16_1440337868") (class "Default")
      (node (ref "JP106") (pin "1") (pinfunction "1_1") (pintype "passive"))
      (node (ref "JP1166") (pin "P$1") (pinfunction "1_P$1") (pintype "passive"))
    )
    (net (code "52") (name "/17_1440337657") (class "Default")
      (node (ref "JP171") (pin "1") (pinfunction "1_1") (pintype "passive"))
      (node (ref "JP995") (pin "P$1") (pinfunction "1_P$1") (pintype "passive"))
    )
    (net (code "53") (name "/17_1440337842") (class "Default")
      (node (ref "JP1177") (pin "P$1") (pinfunction "1_P$1") (pintype "passive"))
      (node (ref "JP215") (pin "1") (pinfunction "1_1") (pintype "passive"))
    )
    (net (code "54") (name "/17_1440337868") (class "Default")
      (node (ref "JP116") (pin "1") (pinfunction "1_1") (pintype "passive"))
      (node (ref "JP1167") (pin "P$1") (pinfunction "1_P$1") (pintype "passive"))
    )
    (net (code "55") (name "/18_1440337657") (class "Default")
      (node (ref "JP181") (pin "1") (pinfunction "1_1") (pintype "passive"))
      (node (ref "JP997") (pin "P$1") (pinfunction "1_P$1") (pintype "passive"))
    )
    (net (code "56") (name "/18_1440337842") (class "Default")
      (node (ref "JP1146") (pin "P$1") (pinfunction "1_P$1") (pintype "passive"))
      (node (ref "JP95") (pin "1") (pinfunction "1_1") (pintype "passive"))
    )
    (net (code "57") (name "/18_1440337868") (class "Default")
      (node (ref "JP1168") (pin "P$1") (pinfunction "1_P$1") (pintype "passive"))
      (node (ref "JP126") (pin "1") (pinfunction "1_1") (pintype "passive"))
    )
    (net (code "58") (name "/19_1440337657") (class "Default")
      (node (ref "JP191") (pin "1") (pinfunction "1_1") (pintype "passive"))
      (node (ref "JP999") (pin "P$1") (pinfunction "1_P$1") (pintype "passive"))
    )
    (net (code "59") (name "/19_1440337842") (class "Default")
      (node (ref "JP1176") (pin "P$1") (pinfunction "1_P$1") (pintype "passive"))
      (node (ref "JP205") (pin "1") (pinfunction "1_1") (pintype "passive"))
    )
    (net (code "60") (name "/19_1440337868") (class "Default")
      (node (ref "JP1169") (pin "P$1") (pinfunction "1_P$1") (pintype "passive"))
      (node (ref "JP136") (pin "1") (pinfunction "1_1") (pintype "passive"))
    )
    (net (code "61") (name "/20_1440337657") (class "Default")
      (node (ref "JP1001") (pin "P$1") (pinfunction "1_P$1") (pintype "passive"))
      (node (ref "JP201") (pin "1") (pinfunction "1_1") (pintype "passive"))
    )
    (net (code "62") (name "/20_1440337842") (class "Default")
      (node (ref "JP105") (pin "1") (pinfunction "1_1") (pintype "passive"))
      (node (ref "JP1145") (pin "P$1") (pinfunction "1_P$1") (pintype "passive"))
    )
    (net (code "63") (name "/20_1440337868") (class "Default")
      (node (ref "JP1170") (pin "P$1") (pinfunction "1_P$1") (pintype "passive"))
      (node (ref "JP146") (pin "1") (pinfunction "1_1") (pintype "passive"))
    )
    (net (code "64") (name "/21_1440337657") (class "Default")
      (node (ref "JP1003") (pin "P$1") (pinfunction "1_P$1") (pintype "passive"))
      (node (ref "JP211") (pin "1") (pinfunction "1_1") (pintype "passive"))
    )
    (net (code "65") (name "/21_1440337842") (class "Default")
      (node (ref "JP1175") (pin "P$1") (pinfunction "1_P$1") (pintype "passive"))
      (node (ref "JP195") (pin "1") (pinfunction "1_1") (pintype "passive"))
    )
    (net (code "66") (name "/21_1440337868") (class "Default")
      (node (ref "JP1186") (pin "P$1") (pinfunction "1_P$1") (pintype "passive"))
      (node (ref "JP236") (pin "1") (pinfunction "1_1") (pintype "passive"))
    )
    (net (code "67") (name "/22_1440337657") (class "Default")
      (node (ref "JP1005") (pin "P$1") (pinfunction "1_P$1") (pintype "passive"))
      (node (ref "JP221") (pin "1") (pinfunction "1_1") (pintype "passive"))
    )
    (net (code "68") (name "/22_1440337842") (class "Default")
      (node (ref "JP1144") (pin "P$1") (pinfunction "1_P$1") (pintype "passive"))
      (node (ref "JP115") (pin "1") (pinfunction "1_1") (pintype "passive"))
    )
    (net (code "69") (name "/22_1440337868") (class "Default")
      (node (ref "JP1193") (pin "P$1") (pinfunction "1_P$1") (pintype "passive"))
      (node (ref "JP226") (pin "1") (pinfunction "1_1") (pintype "passive"))
    )
    (net (code "70") (name "/23_1440337657") (class "Default")
      (node (ref "JP1007") (pin "P$1") (pinfunction "1_P$1") (pintype "passive"))
      (node (ref "JP231") (pin "1") (pinfunction "1_1") (pintype "passive"))
    )
    (net (code "71") (name "/23_1440337842") (class "Default")
      (node (ref "JP1174") (pin "P$1") (pinfunction "1_P$1") (pintype "passive"))
      (node (ref "JP185") (pin "1") (pinfunction "1_1") (pintype "passive"))
    )
    (net (code "72") (name "/23_1440337868") (class "Default")
      (node (ref "JP1194") (pin "P$1") (pinfunction "1_P$1") (pintype "passive"))
      (node (ref "JP216") (pin "1") (pinfunction "1_1") (pintype "passive"))
    )
    (net (code "73") (name "/24_1440337657") (class "Default")
      (node (ref "JP1009") (pin "P$1") (pinfunction "1_P$1") (pintype "passive"))
      (node (ref "JP241") (pin "1") (pinfunction "1_1") (pintype "passive"))
    )
    (net (code "74") (name "/24_1440337842") (class "Default")
      (node (ref "JP1143") (pin "P$1") (pinfunction "1_P$1") (pintype "passive"))
      (node (ref "JP125") (pin "1") (pinfunction "1_1") (pintype "passive"))
    )
    (net (code "75") (name "/24_1440337868") (class "Default")
      (node (ref "JP1195") (pin "P$1") (pinfunction "1_P$1") (pintype "passive"))
      (node (ref "JP206") (pin "1") (pinfunction "1_1") (pintype "passive"))
    )
    (net (code "76") (name "/25_1440337657") (class "Default")
      (node (ref "JP1011") (pin "P$1") (pinfunction "1_P$1") (pintype "passive"))
      (node (ref "JP251") (pin "1") (pinfunction "1_1") (pintype "passive"))
    )
    (net (code "77") (name "/25_1440337842") (class "Default")
      (node (ref "JP1173") (pin "P$1") (pinfunction "1_P$1") (pintype "passive"))
      (node (ref "JP175") (pin "1") (pinfunction "1_1") (pintype "passive"))
    )
    (net (code "78") (name "/25_1440337868") (class "Default")
      (node (ref "JP1196") (pin "P$1") (pinfunction "1_P$1") (pintype "passive"))
      (node (ref "JP196") (pin "1") (pinfunction "1_1") (pintype "passive"))
    )
    (net (code "79") (name "/26_1440337657") (class "Default")
      (node (ref "JP1013") (pin "P$1") (pinfunction "1_P$1") (pintype "passive"))
      (node (ref "JP261") (pin "1") (pinfunction "1_1") (pintype "passive"))
    )
    (net (code "80") (name "/26_1440337842") (class "Default")
      (node (ref "JP1142") (pin "P$1") (pinfunction "1_P$1") (pintype "passive"))
      (node (ref "JP135") (pin "1") (pinfunction "1_1") (pintype "passive"))
    )
    (net (code "81") (name "/26_1440337868") (class "Default")
      (node (ref "JP1197") (pin "P$1") (pinfunction "1_P$1") (pintype "passive"))
      (node (ref "JP186") (pin "1") (pinfunction "1_1") (pintype "passive"))
    )
    (net (code "82") (name "/27_1440337657") (class "Default")
      (node (ref "JP1015") (pin "P$1") (pinfunction "1_P$1") (pintype "passive"))
      (node (ref "JP271") (pin "1") (pinfunction "1_1") (pintype "passive"))
    )
    (net (code "83") (name "/27_1440337842") (class "Default")
      (node (ref "JP1172") (pin "P$1") (pinfunction "1_P$1") (pintype "passive"))
      (node (ref "JP165") (pin "1") (pinfunction "1_1") (pintype "passive"))
    )
    (net (code "84") (name "/27_1440337868") (class "Default")
      (node (ref "JP1198") (pin "P$1") (pinfunction "1_P$1") (pintype "passive"))
      (node (ref "JP176") (pin "1") (pinfunction "1_1") (pintype "passive"))
    )
    (net (code "85") (name "/28_1440337657") (class "Default")
      (node (ref "JP1017") (pin "P$1") (pinfunction "1_P$1") (pintype "passive"))
      (node (ref "JP281") (pin "1") (pinfunction "1_1") (pintype "passive"))
    )
    (net (code "86") (name "/28_1440337842") (class "Default")
      (node (ref "JP1141") (pin "P$1") (pinfunction "1_P$1") (pintype "passive"))
      (node (ref "JP145") (pin "1") (pinfunction "1_1") (pintype "passive"))
    )
    (net (code "87") (name "/28_1440337868") (class "Default")
      (node (ref "JP1199") (pin "P$1") (pinfunction "1_P$1") (pintype "passive"))
      (node (ref "JP166") (pin "1") (pinfunction "1_1") (pintype "passive"))
    )
    (net (code "88") (name "/29_1440337657") (class "Default")
      (node (ref "JP1019") (pin "P$1") (pinfunction "1_P$1") (pintype "passive"))
      (node (ref "JP291") (pin "1") (pinfunction "1_1") (pintype "passive"))
    )
    (net (code "89") (name "/29_1440337842") (class "Default")
      (node (ref "JP1171") (pin "P$1") (pinfunction "1_P$1") (pintype "passive"))
      (node (ref "JP155") (pin "1") (pinfunction "1_1") (pintype "passive"))
    )
    (net (code "90") (name "/29_1440337868") (class "Default")
      (node (ref "JP1200") (pin "P$1") (pinfunction "1_P$1") (pintype "passive"))
      (node (ref "JP156") (pin "1") (pinfunction "1_1") (pintype "passive"))
    )
    (net (code "91") (name "/30_1440337657") (class "Default")
      (node (ref "JP1020") (pin "P$1") (pinfunction "1_P$1") (pintype "passive"))
      (node (ref "JP292") (pin "1") (pinfunction "1_1") (pintype "passive"))
    )
    (net (code "92") (name "/31_1440337657") (class "Default")
      (node (ref "JP10") (pin "1") (pinfunction "1_1") (pintype "passive"))
      (node (ref "JP1021") (pin "P$1") (pinfunction "1_P$1") (pintype "passive"))
    )
    (net (code "93") (name "/32_1440337657") (class "Default")
      (node (ref "JP1023") (pin "P$1") (pinfunction "1_P$1") (pintype "passive"))
      (node (ref "JP20") (pin "1") (pinfunction "1_1") (pintype "passive"))
    )
    (net (code "94") (name "/33_1440337657") (class "Default")
      (node (ref "JP1025") (pin "P$1") (pinfunction "1_P$1") (pintype "passive"))
      (node (ref "JP30") (pin "1") (pinfunction "1_1") (pintype "passive"))
    )
    (net (code "95") (name "/34_1440337657") (class "Default")
      (node (ref "JP1027") (pin "P$1") (pinfunction "1_P$1") (pintype "passive"))
      (node (ref "JP40") (pin "1") (pinfunction "1_1") (pintype "passive"))
    )
    (net (code "96") (name "/35_1440337657") (class "Default")
      (node (ref "JP1029") (pin "P$1") (pinfunction "1_P$1") (pintype "passive"))
      (node (ref "JP50") (pin "1") (pinfunction "1_1") (pintype "passive"))
    )
    (net (code "97") (name "/36_1440337657") (class "Default")
      (node (ref "JP1031") (pin "P$1") (pinfunction "1_P$1") (pintype "passive"))
      (node (ref "JP60") (pin "1") (pinfunction "1_1") (pintype "passive"))
    )
    (net (code "98") (name "/37_1440337657") (class "Default")
      (node (ref "JP1033") (pin "P$1") (pinfunction "1_P$1") (pintype "passive"))
      (node (ref "JP70") (pin "1") (pinfunction "1_1") (pintype "passive"))
    )
    (net (code "99") (name "/38_1440337657") (class "Default")
      (node (ref "JP1035") (pin "P$1") (pinfunction "1_P$1") (pintype "passive"))
      (node (ref "JP80") (pin "1") (pinfunction "1_1") (pintype "passive"))
    )
    (net (code "100") (name "/39_1440337657") (class "Default")
      (node (ref "JP1037") (pin "P$1") (pinfunction "1_P$1") (pintype "passive"))
      (node (ref "JP90") (pin "1") (pinfunction "1_1") (pintype "passive"))
    )
    (net (code "101") (name "/40_1440337657") (class "Default")
      (node (ref "JP100") (pin "1") (pinfunction "1_1") (pintype "passive"))
      (node (ref "JP1039") (pin "P$1") (pinfunction "1_P$1") (pintype "passive"))
    )
    (net (code "102") (name "/41_1440337657") (class "Default")
      (node (ref "JP1041") (pin "P$1") (pinfunction "1_P$1") (pintype "passive"))
      (node (ref "JP110") (pin "1") (pinfunction "1_1") (pintype "passive"))
    )
    (net (code "103") (name "/42_1440337657") (class "Default")
      (node (ref "JP1043") (pin "P$1") (pinfunction "1_P$1") (pintype "passive"))
      (node (ref "JP120") (pin "1") (pinfunction "1_1") (pintype "passive"))
    )
    (net (code "104") (name "/43_1440337657") (class "Default")
      (node (ref "JP1045") (pin "P$1") (pinfunction "1_P$1") (pintype "passive"))
      (node (ref "JP130") (pin "1") (pinfunction "1_1") (pintype "passive"))
    )
    (net (code "105") (name "/44_1440337657") (class "Default")
      (node (ref "JP1047") (pin "P$1") (pinfunction "1_P$1") (pintype "passive"))
      (node (ref "JP140") (pin "1") (pinfunction "1_1") (pintype "passive"))
    )
    (net (code "106") (name "/45_1440337657") (class "Default")
      (node (ref "JP1049") (pin "P$1") (pinfunction "1_P$1") (pintype "passive"))
      (node (ref "JP150") (pin "1") (pinfunction "1_1") (pintype "passive"))
    )
    (net (code "107") (name "/46_1440337657") (class "Default")
      (node (ref "JP1051") (pin "P$1") (pinfunction "1_P$1") (pintype "passive"))
      (node (ref "JP160") (pin "1") (pinfunction "1_1") (pintype "passive"))
    )
    (net (code "108") (name "/47_1440337657") (class "Default")
      (node (ref "JP1053") (pin "P$1") (pinfunction "1_P$1") (pintype "passive"))
      (node (ref "JP170") (pin "1") (pinfunction "1_1") (pintype "passive"))
    )
    (net (code "109") (name "/48_1440337657") (class "Default")
      (node (ref "JP1055") (pin "P$1") (pinfunction "1_P$1") (pintype "passive"))
      (node (ref "JP180") (pin "1") (pinfunction "1_1") (pintype "passive"))
    )
    (net (code "110") (name "/49_1440337657") (class "Default")
      (node (ref "JP1057") (pin "P$1") (pinfunction "1_P$1") (pintype "passive"))
      (node (ref "JP190") (pin "1") (pinfunction "1_1") (pintype "passive"))
    )
    (net (code "111") (name "/50_1440337657") (class "Default")
      (node (ref "JP1059") (pin "P$1") (pinfunction "1_P$1") (pintype "passive"))
      (node (ref "JP200") (pin "1") (pinfunction "1_1") (pintype "passive"))
    )
    (net (code "112") (name "/51_1440337657") (class "Default")
      (node (ref "JP1061") (pin "P$1") (pinfunction "1_P$1") (pintype "passive"))
      (node (ref "JP210") (pin "1") (pinfunction "1_1") (pintype "passive"))
    )
    (net (code "113") (name "/52_1440337657") (class "Default")
      (node (ref "JP1063") (pin "P$1") (pinfunction "1_P$1") (pintype "passive"))
      (node (ref "JP220") (pin "1") (pinfunction "1_1") (pintype "passive"))
    )
    (net (code "114") (name "/53_1440337657") (class "Default")
      (node (ref "JP1065") (pin "P$1") (pinfunction "1_P$1") (pintype "passive"))
      (node (ref "JP230") (pin "1") (pinfunction "1_1") (pintype "passive"))
    )
    (net (code "115") (name "/54_1440337657") (class "Default")
      (node (ref "JP1067") (pin "P$1") (pinfunction "1_P$1") (pintype "passive"))
      (node (ref "JP240") (pin "1") (pinfunction "1_1") (pintype "passive"))
    )
    (net (code "116") (name "/55_1440337657") (class "Default")
      (node (ref "JP1069") (pin "P$1") (pinfunction "1_P$1") (pintype "passive"))
      (node (ref "JP250") (pin "1") (pinfunction "1_1") (pintype "passive"))
    )
    (net (code "117") (name "/56_1440337657") (class "Default")
      (node (ref "JP1071") (pin "P$1") (pinfunction "1_P$1") (pintype "passive"))
      (node (ref "JP260") (pin "1") (pinfunction "1_1") (pintype "passive"))
    )
    (net (code "118") (name "/57_1440337657") (class "Default")
      (node (ref "JP1073") (pin "P$1") (pinfunction "1_P$1") (pintype "passive"))
      (node (ref "JP270") (pin "1") (pinfunction "1_1") (pintype "passive"))
    )
    (net (code "119") (name "/58_1440337657") (class "Default")
      (node (ref "JP1075") (pin "P$1") (pinfunction "1_P$1") (pintype "passive"))
      (node (ref "JP280") (pin "1") (pinfunction "1_1") (pintype "passive"))
    )
    (net (code "120") (name "/59_1440337657") (class "Default")
      (node (ref "JP1077") (pin "P$1") (pinfunction "1_P$1") (pintype "passive"))
      (node (ref "JP290") (pin "1") (pinfunction "1_1") (pintype "passive"))
    )
    (net (code "121") (name "/60_1440337657") (class "Default")
      (node (ref "JP1079") (pin "P$1") (pinfunction "1_P$1") (pintype "passive"))
      (node (ref "JP300") (pin "1") (pinfunction "1_1") (pintype "passive"))
    )
    (net (code "122") (name "/61_1440337657") (class "Default")
      (node (ref "JP1080") (pin "P$1") (pinfunction "1_P$1") (pintype "passive"))
      (node (ref "JP299") (pin "1") (pinfunction "1_1") (pintype "passive"))
    )
    (net (code "123") (name "/62_1440337657") (class "Default")
      (node (ref "JP2") (pin "1") (pinfunction "1_1") (pintype "passive"))
      (node (ref "JP962") (pin "P$1") (pinfunction "1_P$1") (pintype "passive"))
    )
    (net (code "124") (name "/63_1440337657") (class "Default")
      (node (ref "JP12") (pin "1") (pinfunction "1_1") (pintype "passive"))
      (node (ref "JP964") (pin "P$1") (pinfunction "1_P$1") (pintype "passive"))
    )
    (net (code "125") (name "/64_1440337657") (class "Default")
      (node (ref "JP22") (pin "1") (pinfunction "1_1") (pintype "passive"))
      (node (ref "JP966") (pin "P$1") (pinfunction "1_P$1") (pintype "passive"))
    )
    (net (code "126") (name "/65_1440337657") (class "Default")
      (node (ref "JP32") (pin "1") (pinfunction "1_1") (pintype "passive"))
      (node (ref "JP968") (pin "P$1") (pinfunction "1_P$1") (pintype "passive"))
    )
    (net (code "127") (name "/66_1440337657") (class "Default")
      (node (ref "JP42") (pin "1") (pinfunction "1_1") (pintype "passive"))
      (node (ref "JP970") (pin "P$1") (pinfunction "1_P$1") (pintype "passive"))
    )
    (net (code "128") (name "/67_1440337657") (class "Default")
      (node (ref "JP52") (pin "1") (pinfunction "1_1") (pintype "passive"))
      (node (ref "JP972") (pin "P$1") (pinfunction "1_P$1") (pintype "passive"))
    )
    (net (code "129") (name "/68_1440337657") (class "Default")
      (node (ref "JP62") (pin "1") (pinfunction "1_1") (pintype "passive"))
      (node (ref "JP974") (pin "P$1") (pinfunction "1_P$1") (pintype "passive"))
    )
    (net (code "130") (name "/69_1440337657") (class "Default")
      (node (ref "JP72") (pin "1") (pinfunction "1_1") (pintype "passive"))
      (node (ref "JP976") (pin "P$1") (pinfunction "1_P$1") (pintype "passive"))
    )
    (net (code "131") (name "/70_1440337657") (class "Default")
      (node (ref "JP82") (pin "1") (pinfunction "1_1") (pintype "passive"))
      (node (ref "JP978") (pin "P$1") (pinfunction "1_P$1") (pintype "passive"))
    )
    (net (code "132") (name "/71_1440337657") (class "Default")
      (node (ref "JP92") (pin "1") (pinfunction "1_1") (pintype "passive"))
      (node (ref "JP980") (pin "P$1") (pinfunction "1_P$1") (pintype "passive"))
    )
    (net (code "133") (name "/72_1440337657") (class "Default")
      (node (ref "JP102") (pin "1") (pinfunction "1_1") (pintype "passive"))
      (node (ref "JP982") (pin "P$1") (pinfunction "1_P$1") (pintype "passive"))
    )
    (net (code "134") (name "/73_1440337657") (class "Default")
      (node (ref "JP112") (pin "1") (pinfunction "1_1") (pintype "passive"))
      (node (ref "JP984") (pin "P$1") (pinfunction "1_P$1") (pintype "passive"))
    )
    (net (code "135") (name "/74_1440337657") (class "Default")
      (node (ref "JP122") (pin "1") (pinfunction "1_1") (pintype "passive"))
      (node (ref "JP986") (pin "P$1") (pinfunction "1_P$1") (pintype "passive"))
    )
    (net (code "136") (name "/75_1440337657") (class "Default")
      (node (ref "JP132") (pin "1") (pinfunction "1_1") (pintype "passive"))
      (node (ref "JP988") (pin "P$1") (pinfunction "1_P$1") (pintype "passive"))
    )
    (net (code "137") (name "/76_1440337657") (class "Default")
      (node (ref "JP142") (pin "1") (pinfunction "1_1") (pintype "passive"))
      (node (ref "JP990") (pin "P$1") (pinfunction "1_P$1") (pintype "passive"))
    )
    (net (code "138") (name "/77_1440337657") (class "Default")
      (node (ref "JP152") (pin "1") (pinfunction "1_1") (pintype "passive"))
      (node (ref "JP992") (pin "P$1") (pinfunction "1_P$1") (pintype "passive"))
    )
    (net (code "139") (name "/78_1440337657") (class "Default")
      (node (ref "JP162") (pin "1") (pinfunction "1_1") (pintype "passive"))
      (node (ref "JP994") (pin "P$1") (pinfunction "1_P$1") (pintype "passive"))
    )
    (net (code "140") (name "/79_1440337657") (class "Default")
      (node (ref "JP172") (pin "1") (pinfunction "1_1") (pintype "passive"))
      (node (ref "JP996") (pin "P$1") (pinfunction "1_P$1") (pintype "passive"))
    )
    (net (code "141") (name "/80_1440337657") (class "Default")
      (node (ref "JP182") (pin "1") (pinfunction "1_1") (pintype "passive"))
      (node (ref "JP998") (pin "P$1") (pinfunction "1_P$1") (pintype "passive"))
    )
    (net (code "142") (name "/81_1440337657") (class "Default")
      (node (ref "JP1000") (pin "P$1") (pinfunction "1_P$1") (pintype "passive"))
      (node (ref "JP192") (pin "1") (pinfunction "1_1") (pintype "passive"))
    )
    (net (code "143") (name "/82_1440337657") (class "Default")
      (node (ref "JP1002") (pin "P$1") (pinfunction "1_P$1") (pintype "passive"))
      (node (ref "JP202") (pin "1") (pinfunction "1_1") (pintype "passive"))
    )
    (net (code "144") (name "/83_1440337657") (class "Default")
      (node (ref "JP1004") (pin "P$1") (pinfunction "1_P$1") (pintype "passive"))
      (node (ref "JP212") (pin "1") (pinfunction "1_1") (pintype "passive"))
    )
    (net (code "145") (name "/84_1440337657") (class "Default")
      (node (ref "JP1006") (pin "P$1") (pinfunction "1_P$1") (pintype "passive"))
      (node (ref "JP222") (pin "1") (pinfunction "1_1") (pintype "passive"))
    )
    (net (code "146") (name "/85_1440337657") (class "Default")
      (node (ref "JP1008") (pin "P$1") (pinfunction "1_P$1") (pintype "passive"))
      (node (ref "JP232") (pin "1") (pinfunction "1_1") (pintype "passive"))
    )
    (net (code "147") (name "/86_1440337657") (class "Default")
      (node (ref "JP1010") (pin "P$1") (pinfunction "1_P$1") (pintype "passive"))
      (node (ref "JP242") (pin "1") (pinfunction "1_1") (pintype "passive"))
    )
    (net (code "148") (name "/87_1440337657") (class "Default")
      (node (ref "JP1012") (pin "P$1") (pinfunction "1_P$1") (pintype "passive"))
      (node (ref "JP252") (pin "1") (pinfunction "1_1") (pintype "passive"))
    )
    (net (code "149") (name "/88_1440337657") (class "Default")
      (node (ref "JP1014") (pin "P$1") (pinfunction "1_P$1") (pintype "passive"))
      (node (ref "JP262") (pin "1") (pinfunction "1_1") (pintype "passive"))
    )
    (net (code "150") (name "/89_1440337657") (class "Default")
      (node (ref "JP1016") (pin "P$1") (pinfunction "1_P$1") (pintype "passive"))
      (node (ref "JP272") (pin "1") (pinfunction "1_1") (pintype "passive"))
    )
    (net (code "151") (name "/90_1440337657") (class "Default")
      (node (ref "JP1018") (pin "P$1") (pinfunction "1_P$1") (pintype "passive"))
      (node (ref "JP282") (pin "1") (pinfunction "1_1") (pintype "passive"))
    )
    (net (code "152") (name "/91_1440337657") (class "Default")
      (node (ref "JP1022") (pin "P$1") (pinfunction "1_P$1") (pintype "passive"))
      (node (ref "JP9") (pin "1") (pinfunction "1_1") (pintype "passive"))
    )
    (net (code "153") (name "/92_1440337657") (class "Default")
      (node (ref "JP1024") (pin "P$1") (pinfunction "1_P$1") (pintype "passive"))
      (node (ref "JP19") (pin "1") (pinfunction "1_1") (pintype "passive"))
    )
    (net (code "154") (name "/93_1440337657") (class "Default")
      (node (ref "JP1026") (pin "P$1") (pinfunction "1_P$1") (pintype "passive"))
      (node (ref "JP29") (pin "1") (pinfunction "1_1") (pintype "passive"))
    )
    (net (code "155") (name "/94_1440337657") (class "Default")
      (node (ref "JP1028") (pin "P$1") (pinfunction "1_P$1") (pintype "passive"))
      (node (ref "JP39") (pin "1") (pinfunction "1_1") (pintype "passive"))
    )
    (net (code "156") (name "/95_1440337657") (class "Default")
      (node (ref "JP1030") (pin "P$1") (pinfunction "1_P$1") (pintype "passive"))
      (node (ref "JP49") (pin "1") (pinfunction "1_1") (pintype "passive"))
    )
    (net (code "157") (name "/96_1440337657") (class "Default")
      (node (ref "JP1032") (pin "P$1") (pinfunction "1_P$1") (pintype "passive"))
      (node (ref "JP59") (pin "1") (pinfunction "1_1") (pintype "passive"))
    )
    (net (code "158") (name "/97_1440337657") (class "Default")
      (node (ref "JP1034") (pin "P$1") (pinfunction "1_P$1") (pintype "passive"))
      (node (ref "JP69") (pin "1") (pinfunction "1_1") (pintype "passive"))
    )
    (net (code "159") (name "/98_1440337657") (class "Default")
      (node (ref "JP1036") (pin "P$1") (pinfunction "1_P$1") (pintype "passive"))
      (node (ref "JP79") (pin "1") (pinfunction "1_1") (pintype "passive"))
    )
    (net (code "160") (name "/99_1440337657") (class "Default")
      (node (ref "JP1038") (pin "P$1") (pinfunction "1_P$1") (pintype "passive"))
      (node (ref "JP89") (pin "1") (pinfunction "1_1") (pintype "passive"))
    )
    (net (code "161") (name "/100_1440337657") (class "Default")
      (node (ref "JP1040") (pin "P$1") (pinfunction "1_P$1") (pintype "passive"))
      (node (ref "JP99") (pin "1") (pinfunction "1_1") (pintype "passive"))
    )
    (net (code "162") (name "/101_1440337657") (class "Default")
      (node (ref "JP1042") (pin "P$1") (pinfunction "1_P$1") (pintype "passive"))
      (node (ref "JP109") (pin "1") (pinfunction "1_1") (pintype "passive"))
    )
    (net (code "163") (name "/102_1440337657") (class "Default")
      (node (ref "JP1044") (pin "P$1") (pinfunction "1_P$1") (pintype "passive"))
      (node (ref "JP119") (pin "1") (pinfunction "1_1") (pintype "passive"))
    )
    (net (code "164") (name "/103_1440337657") (class "Default")
      (node (ref "JP1046") (pin "P$1") (pinfunction "1_P$1") (pintype "passive"))
      (node (ref "JP129") (pin "1") (pinfunction "1_1") (pintype "passive"))
    )
    (net (code "165") (name "/104_1440337657") (class "Default")
      (node (ref "JP1048") (pin "P$1") (pinfunction "1_P$1") (pintype "passive"))
      (node (ref "JP139") (pin "1") (pinfunction "1_1") (pintype "passive"))
    )
    (net (code "166") (name "/105_1440337657") (class "Default")
      (node (ref "JP1050") (pin "P$1") (pinfunction "1_P$1") (pintype "passive"))
      (node (ref "JP149") (pin "1") (pinfunction "1_1") (pintype "passive"))
    )
    (net (code "167") (name "/106_1440337657") (class "Default")
      (node (ref "JP1052") (pin "P$1") (pinfunction "1_P$1") (pintype "passive"))
      (node (ref "JP159") (pin "1") (pinfunction "1_1") (pintype "passive"))
    )
    (net (code "168") (name "/107_1440337657") (class "Default")
      (node (ref "JP1054") (pin "P$1") (pinfunction "1_P$1") (pintype "passive"))
      (node (ref "JP169") (pin "1") (pinfunction "1_1") (pintype "passive"))
    )
    (net (code "169") (name "/108_1440337657") (class "Default")
      (node (ref "JP1056") (pin "P$1") (pinfunction "1_P$1") (pintype "passive"))
      (node (ref "JP179") (pin "1") (pinfunction "1_1") (pintype "passive"))
    )
    (net (code "170") (name "/109_1440337657") (class "Default")
      (node (ref "JP1058") (pin "P$1") (pinfunction "1_P$1") (pintype "passive"))
      (node (ref "JP189") (pin "1") (pinfunction "1_1") (pintype "passive"))
    )
    (net (code "171") (name "/110_1440337657") (class "Default")
      (node (ref "JP1060") (pin "P$1") (pinfunction "1_P$1") (pintype "passive"))
      (node (ref "JP199") (pin "1") (pinfunction "1_1") (pintype "passive"))
    )
    (net (code "172") (name "/111_1440337657") (class "Default")
      (node (ref "JP1062") (pin "P$1") (pinfunction "1_P$1") (pintype "passive"))
      (node (ref "JP209") (pin "1") (pinfunction "1_1") (pintype "passive"))
    )
    (net (code "173") (name "/112_1440337657") (class "Default")
      (node (ref "JP1064") (pin "P$1") (pinfunction "1_P$1") (pintype "passive"))
      (node (ref "JP219") (pin "1") (pinfunction "1_1") (pintype "passive"))
    )
    (net (code "174") (name "/113_1440337657") (class "Default")
      (node (ref "JP1066") (pin "P$1") (pinfunction "1_P$1") (pintype "passive"))
      (node (ref "JP229") (pin "1") (pinfunction "1_1") (pintype "passive"))
    )
    (net (code "175") (name "/114_1440337657") (class "Default")
      (node (ref "JP1068") (pin "P$1") (pinfunction "1_P$1") (pintype "passive"))
      (node (ref "JP239") (pin "1") (pinfunction "1_1") (pintype "passive"))
    )
    (net (code "176") (name "/115_1440337657") (class "Default")
      (node (ref "JP1070") (pin "P$1") (pinfunction "1_P$1") (pintype "passive"))
      (node (ref "JP249") (pin "1") (pinfunction "1_1") (pintype "passive"))
    )
    (net (code "177") (name "/116_1440337657") (class "Default")
      (node (ref "JP1072") (pin "P$1") (pinfunction "1_P$1") (pintype "passive"))
      (node (ref "JP259") (pin "1") (pinfunction "1_1") (pintype "passive"))
    )
    (net (code "178") (name "/117_1440337657") (class "Default")
      (node (ref "JP1074") (pin "P$1") (pinfunction "1_P$1") (pintype "passive"))
      (node (ref "JP269") (pin "1") (pinfunction "1_1") (pintype "passive"))
    )
    (net (code "179") (name "/118_1440337657") (class "Default")
      (node (ref "JP1076") (pin "P$1") (pinfunction "1_P$1") (pintype "passive"))
      (node (ref "JP279") (pin "1") (pinfunction "1_1") (pintype "passive"))
    )
    (net (code "180") (name "/119_1440337657") (class "Default")
      (node (ref "JP1078") (pin "P$1") (pinfunction "1_P$1") (pintype "passive"))
      (node (ref "JP289") (pin "1") (pinfunction "1_1") (pintype "passive"))
    )
    (net (code "181") (name "/120_1440337657") (class "Default")
      (node (ref "JP1081") (pin "P$1") (pinfunction "1_P$1") (pintype "passive"))
      (node (ref "JP8") (pin "1") (pinfunction "1_1") (pintype "passive"))
    )
    (net (code "182") (name "/121_1440337657") (class "Default")
      (node (ref "JP1083") (pin "P$1") (pinfunction "1_P$1") (pintype "passive"))
      (node (ref "JP18") (pin "1") (pinfunction "1_1") (pintype "passive"))
    )
    (net (code "183") (name "/122_1440337657") (class "Default")
      (node (ref "JP1085") (pin "P$1") (pinfunction "1_P$1") (pintype "passive"))
      (node (ref "JP28") (pin "1") (pinfunction "1_1") (pintype "passive"))
    )
    (net (code "184") (name "/123_1440337657") (class "Default")
      (node (ref "JP1087") (pin "P$1") (pinfunction "1_P$1") (pintype "passive"))
      (node (ref "JP38") (pin "1") (pinfunction "1_1") (pintype "passive"))
    )
    (net (code "185") (name "/124_1440337657") (class "Default")
      (node (ref "JP1089") (pin "P$1") (pinfunction "1_P$1") (pintype "passive"))
      (node (ref "JP48") (pin "1") (pinfunction "1_1") (pintype "passive"))
    )
    (net (code "186") (name "/125_1440337657") (class "Default")
      (node (ref "JP1091") (pin "P$1") (pinfunction "1_P$1") (pintype "passive"))
      (node (ref "JP58") (pin "1") (pinfunction "1_1") (pintype "passive"))
    )
    (net (code "187") (name "/126_1440337657") (class "Default")
      (node (ref "JP1093") (pin "P$1") (pinfunction "1_P$1") (pintype "passive"))
      (node (ref "JP68") (pin "1") (pinfunction "1_1") (pintype "passive"))
    )
    (net (code "188") (name "/127_1440337657") (class "Default")
      (node (ref "JP1095") (pin "P$1") (pinfunction "1_P$1") (pintype "passive"))
      (node (ref "JP78") (pin "1") (pinfunction "1_1") (pintype "passive"))
    )
    (net (code "189") (name "/128_1440337657") (class "Default")
      (node (ref "JP1097") (pin "P$1") (pinfunction "1_P$1") (pintype "passive"))
      (node (ref "JP88") (pin "1") (pinfunction "1_1") (pintype "passive"))
    )
    (net (code "190") (name "/129_1440337657") (class "Default")
      (node (ref "JP1099") (pin "P$1") (pinfunction "1_P$1") (pintype "passive"))
      (node (ref "JP98") (pin "1") (pinfunction "1_1") (pintype "passive"))
    )
    (net (code "191") (name "/130_1440337657") (class "Default")
      (node (ref "JP108") (pin "1") (pinfunction "1_1") (pintype "passive"))
      (node (ref "JP1101") (pin "P$1") (pinfunction "1_P$1") (pintype "passive"))
    )
    (net (code "192") (name "/131_1440337657") (class "Default")
      (node (ref "JP1103") (pin "P$1") (pinfunction "1_P$1") (pintype "passive"))
      (node (ref "JP118") (pin "1") (pinfunction "1_1") (pintype "passive"))
    )
    (net (code "193") (name "/132_1440337657") (class "Default")
      (node (ref "JP1105") (pin "P$1") (pinfunction "1_P$1") (pintype "passive"))
      (node (ref "JP128") (pin "1") (pinfunction "1_1") (pintype "passive"))
    )
    (net (code "194") (name "/133_1440337657") (class "Default")
      (node (ref "JP1107") (pin "P$1") (pinfunction "1_P$1") (pintype "passive"))
      (node (ref "JP138") (pin "1") (pinfunction "1_1") (pintype "passive"))
    )
    (net (code "195") (name "/134_1440337657") (class "Default")
      (node (ref "JP1109") (pin "P$1") (pinfunction "1_P$1") (pintype "passive"))
      (node (ref "JP148") (pin "1") (pinfunction "1_1") (pintype "passive"))
    )
    (net (code "196") (name "/135_1440337657") (class "Default")
      (node (ref "JP1111") (pin "P$1") (pinfunction "1_P$1") (pintype "passive"))
      (node (ref "JP158") (pin "1") (pinfunction "1_1") (pintype "passive"))
    )
    (net (code "197") (name "/136_1440337657") (class "Default")
      (node (ref "JP1113") (pin "P$1") (pinfunction "1_P$1") (pintype "passive"))
      (node (ref "JP168") (pin "1") (pinfunction "1_1") (pintype "passive"))
    )
    (net (code "198") (name "/137_1440337657") (class "Default")
      (node (ref "JP1115") (pin "P$1") (pinfunction "1_P$1") (pintype "passive"))
      (node (ref "JP178") (pin "1") (pinfunction "1_1") (pintype "passive"))
    )
    (net (code "199") (name "/138_1440337657") (class "Default")
      (node (ref "JP1117") (pin "P$1") (pinfunction "1_P$1") (pintype "passive"))
      (node (ref "JP188") (pin "1") (pinfunction "1_1") (pintype "passive"))
    )
    (net (code "200") (name "/139_1440337657") (class "Default")
      (node (ref "JP1119") (pin "P$1") (pinfunction "1_P$1") (pintype "passive"))
      (node (ref "JP198") (pin "1") (pinfunction "1_1") (pintype "passive"))
    )
    (net (code "201") (name "/140_1440337657") (class "Default")
      (node (ref "JP1121") (pin "P$1") (pinfunction "1_P$1") (pintype "passive"))
      (node (ref "JP208") (pin "1") (pinfunction "1_1") (pintype "passive"))
    )
    (net (code "202") (name "/141_1440337657") (class "Default")
      (node (ref "JP1123") (pin "P$1") (pinfunction "1_P$1") (pintype "passive"))
      (node (ref "JP218") (pin "1") (pinfunction "1_1") (pintype "passive"))
    )
    (net (code "203") (name "/142_1440337657") (class "Default")
      (node (ref "JP1125") (pin "P$1") (pinfunction "1_P$1") (pintype "passive"))
      (node (ref "JP228") (pin "1") (pinfunction "1_1") (pintype "passive"))
    )
    (net (code "204") (name "/143_1440337657") (class "Default")
      (node (ref "JP1127") (pin "P$1") (pinfunction "1_P$1") (pintype "passive"))
      (node (ref "JP238") (pin "1") (pinfunction "1_1") (pintype "passive"))
    )
    (net (code "205") (name "/144_1440337657") (class "Default")
      (node (ref "JP1129") (pin "P$1") (pinfunction "1_P$1") (pintype "passive"))
      (node (ref "JP248") (pin "1") (pinfunction "1_1") (pintype "passive"))
    )
    (net (code "206") (name "/145_1440337657") (class "Default")
      (node (ref "JP1131") (pin "P$1") (pinfunction "1_P$1") (pintype "passive"))
      (node (ref "JP258") (pin "1") (pinfunction "1_1") (pintype "passive"))
    )
    (net (code "207") (name "/146_1440337657") (class "Default")
      (node (ref "JP1133") (pin "P$1") (pinfunction "1_P$1") (pintype "passive"))
      (node (ref "JP268") (pin "1") (pinfunction "1_1") (pintype "passive"))
    )
    (net (code "208") (name "/147_1440337657") (class "Default")
      (node (ref "JP1135") (pin "P$1") (pinfunction "1_P$1") (pintype "passive"))
      (node (ref "JP278") (pin "1") (pinfunction "1_1") (pintype "passive"))
    )
    (net (code "209") (name "/148_1440337657") (class "Default")
      (node (ref "JP1137") (pin "P$1") (pinfunction "1_P$1") (pintype "passive"))
      (node (ref "JP288") (pin "1") (pinfunction "1_1") (pintype "passive"))
    )
    (net (code "210") (name "/149_1440337657") (class "Default")
      (node (ref "JP1139") (pin "P$1") (pinfunction "1_P$1") (pintype "passive"))
      (node (ref "JP298") (pin "1") (pinfunction "1_1") (pintype "passive"))
    )
    (net (code "211") (name "/150_1440337657") (class "Default")
      (node (ref "JP1140") (pin "P$1") (pinfunction "1_P$1") (pintype "passive"))
      (node (ref "JP297") (pin "1") (pinfunction "1_1") (pintype "passive"))
    )
    (net (code "212") (name "/151_1440337657") (class "Default")
      (node (ref "JP3") (pin "1") (pinfunction "1_1") (pintype "passive"))
      (node (ref "JP901") (pin "P$1") (pinfunction "1_P$1") (pintype "passive"))
    )
    (net (code "213") (name "/152_1440337657") (class "Default")
      (node (ref "JP13") (pin "1") (pinfunction "1_1") (pintype "passive"))
      (node (ref "JP903") (pin "P$1") (pinfunction "1_P$1") (pintype "passive"))
    )
    (net (code "214") (name "/153_1440337657") (class "Default")
      (node (ref "JP23") (pin "1") (pinfunction "1_1") (pintype "passive"))
      (node (ref "JP905") (pin "P$1") (pinfunction "1_P$1") (pintype "passive"))
    )
    (net (code "215") (name "/154_1440337657") (class "Default")
      (node (ref "JP33") (pin "1") (pinfunction "1_1") (pintype "passive"))
      (node (ref "JP907") (pin "P$1") (pinfunction "1_P$1") (pintype "passive"))
    )
    (net (code "216") (name "/155_1440337657") (class "Default")
      (node (ref "JP43") (pin "1") (pinfunction "1_1") (pintype "passive"))
      (node (ref "JP909") (pin "P$1") (pinfunction "1_P$1") (pintype "passive"))
    )
    (net (code "217") (name "/156_1440337657") (class "Default")
      (node (ref "JP53") (pin "1") (pinfunction "1_1") (pintype "passive"))
      (node (ref "JP911") (pin "P$1") (pinfunction "1_P$1") (pintype "passive"))
    )
    (net (code "218") (name "/157_1440337657") (class "Default")
      (node (ref "JP63") (pin "1") (pinfunction "1_1") (pintype "passive"))
      (node (ref "JP913") (pin "P$1") (pinfunction "1_P$1") (pintype "passive"))
    )
    (net (code "219") (name "/158_1440337657") (class "Default")
      (node (ref "JP73") (pin "1") (pinfunction "1_1") (pintype "passive"))
      (node (ref "JP915") (pin "P$1") (pinfunction "1_P$1") (pintype "passive"))
    )
    (net (code "220") (name "/159_1440337657") (class "Default")
      (node (ref "JP83") (pin "1") (pinfunction "1_1") (pintype "passive"))
      (node (ref "JP917") (pin "P$1") (pinfunction "1_P$1") (pintype "passive"))
    )
    (net (code "221") (name "/160_1440337657") (class "Default")
      (node (ref "JP919") (pin "P$1") (pinfunction "1_P$1") (pintype "passive"))
      (node (ref "JP93") (pin "1") (pinfunction "1_1") (pintype "passive"))
    )
    (net (code "222") (name "/161_1440337657") (class "Default")
      (node (ref "JP103") (pin "1") (pinfunction "1_1") (pintype "passive"))
      (node (ref "JP921") (pin "P$1") (pinfunction "1_P$1") (pintype "passive"))
    )
    (net (code "223") (name "/162_1440337657") (class "Default")
      (node (ref "JP113") (pin "1") (pinfunction "1_1") (pintype "passive"))
      (node (ref "JP923") (pin "P$1") (pinfunction "1_P$1") (pintype "passive"))
    )
    (net (code "224") (name "/163_1440337657") (class "Default")
      (node (ref "JP123") (pin "1") (pinfunction "1_1") (pintype "passive"))
      (node (ref "JP925") (pin "P$1") (pinfunction "1_P$1") (pintype "passive"))
    )
    (net (code "225") (name "/164_1440337657") (class "Default")
      (node (ref "JP133") (pin "1") (pinfunction "1_1") (pintype "passive"))
      (node (ref "JP927") (pin "P$1") (pinfunction "1_P$1") (pintype "passive"))
    )
    (net (code "226") (name "/165_1440337657") (class "Default")
      (node (ref "JP143") (pin "1") (pinfunction "1_1") (pintype "passive"))
      (node (ref "JP929") (pin "P$1") (pinfunction "1_P$1") (pintype "passive"))
    )
    (net (code "227") (name "/166_1440337657") (class "Default")
      (node (ref "JP153") (pin "1") (pinfunction "1_1") (pintype "passive"))
      (node (ref "JP931") (pin "P$1") (pinfunction "1_P$1") (pintype "passive"))
    )
    (net (code "228") (name "/167_1440337657") (class "Default")
      (node (ref "JP163") (pin "1") (pinfunction "1_1") (pintype "passive"))
      (node (ref "JP933") (pin "P$1") (pinfunction "1_P$1") (pintype "passive"))
    )
    (net (code "229") (name "/168_1440337657") (class "Default")
      (node (ref "JP173") (pin "1") (pinfunction "1_1") (pintype "passive"))
      (node (ref "JP935") (pin "P$1") (pinfunction "1_P$1") (pintype "passive"))
    )
    (net (code "230") (name "/169_1440337657") (class "Default")
      (node (ref "JP183") (pin "1") (pinfunction "1_1") (pintype "passive"))
      (node (ref "JP937") (pin "P$1") (pinfunction "1_P$1") (pintype "passive"))
    )
    (net (code "231") (name "/170_1440337657") (class "Default")
      (node (ref "JP193") (pin "1") (pinfunction "1_1") (pintype "passive"))
      (node (ref "JP939") (pin "P$1") (pinfunction "1_P$1") (pintype "passive"))
    )
    (net (code "232") (name "/171_1440337657") (class "Default")
      (node (ref "JP203") (pin "1") (pinfunction "1_1") (pintype "passive"))
      (node (ref "JP941") (pin "P$1") (pinfunction "1_P$1") (pintype "passive"))
    )
    (net (code "233") (name "/172_1440337657") (class "Default")
      (node (ref "JP213") (pin "1") (pinfunction "1_1") (pintype "passive"))
      (node (ref "JP943") (pin "P$1") (pinfunction "1_P$1") (pintype "passive"))
    )
    (net (code "234") (name "/173_1440337657") (class "Default")
      (node (ref "JP223") (pin "1") (pinfunction "1_1") (pintype "passive"))
      (node (ref "JP945") (pin "P$1") (pinfunction "1_P$1") (pintype "passive"))
    )
    (net (code "235") (name "/174_1440337657") (class "Default")
      (node (ref "JP233") (pin "1") (pinfunction "1_1") (pintype "passive"))
      (node (ref "JP947") (pin "P$1") (pinfunction "1_P$1") (pintype "passive"))
    )
    (net (code "236") (name "/175_1440337657") (class "Default")
      (node (ref "JP243") (pin "1") (pinfunction "1_1") (pintype "passive"))
      (node (ref "JP949") (pin "P$1") (pinfunction "1_P$1") (pintype "passive"))
    )
    (net (code "237") (name "/176_1440337657") (class "Default")
      (node (ref "JP253") (pin "1") (pinfunction "1_1") (pintype "passive"))
      (node (ref "JP951") (pin "P$1") (pinfunction "1_P$1") (pintype "passive"))
    )
    (net (code "238") (name "/177_1440337657") (class "Default")
      (node (ref "JP263") (pin "1") (pinfunction "1_1") (pintype "passive"))
      (node (ref "JP953") (pin "P$1") (pinfunction "1_P$1") (pintype "passive"))
    )
    (net (code "239") (name "/178_1440337657") (class "Default")
      (node (ref "JP273") (pin "1") (pinfunction "1_1") (pintype "passive"))
      (node (ref "JP955") (pin "P$1") (pinfunction "1_P$1") (pintype "passive"))
    )
    (net (code "240") (name "/179_1440337657") (class "Default")
      (node (ref "JP283") (pin "1") (pinfunction "1_1") (pintype "passive"))
      (node (ref "JP957") (pin "P$1") (pinfunction "1_P$1") (pintype "passive"))
    )
    (net (code "241") (name "/180_1440337657") (class "Default")
      (node (ref "JP293") (pin "1") (pinfunction "1_1") (pintype "passive"))
      (node (ref "JP959") (pin "P$1") (pinfunction "1_P$1") (pintype "passive"))
    )
    (net (code "242") (name "/181_1440337657") (class "Default")
      (node (ref "JP294") (pin "1") (pinfunction "1_1") (pintype "passive"))
      (node (ref "JP960") (pin "P$1") (pinfunction "1_P$1") (pintype "passive"))
    )
    (net (code "243") (name "/182_1440337657") (class "Default")
      (node (ref "JP1082") (pin "P$1") (pinfunction "1_P$1") (pintype "passive"))
      (node (ref "JP7") (pin "1") (pinfunction "1_1") (pintype "passive"))
    )
    (net (code "244") (name "/183_1440337657") (class "Default")
      (node (ref "JP1084") (pin "P$1") (pinfunction "1_P$1") (pintype "passive"))
      (node (ref "JP17") (pin "1") (pinfunction "1_1") (pintype "passive"))
    )
    (net (code "245") (name "/184_1440337657") (class "Default")
      (node (ref "JP1086") (pin "P$1") (pinfunction "1_P$1") (pintype "passive"))
      (node (ref "JP27") (pin "1") (pinfunction "1_1") (pintype "passive"))
    )
    (net (code "246") (name "/185_1440337657") (class "Default")
      (node (ref "JP1088") (pin "P$1") (pinfunction "1_P$1") (pintype "passive"))
      (node (ref "JP37") (pin "1") (pinfunction "1_1") (pintype "passive"))
    )
    (net (code "247") (name "/186_1440337657") (class "Default")
      (node (ref "JP1090") (pin "P$1") (pinfunction "1_P$1") (pintype "passive"))
      (node (ref "JP47") (pin "1") (pinfunction "1_1") (pintype "passive"))
    )
    (net (code "248") (name "/187_1440337657") (class "Default")
      (node (ref "JP1092") (pin "P$1") (pinfunction "1_P$1") (pintype "passive"))
      (node (ref "JP57") (pin "1") (pinfunction "1_1") (pintype "passive"))
    )
    (net (code "249") (name "/188_1440337657") (class "Default")
      (node (ref "JP1094") (pin "P$1") (pinfunction "1_P$1") (pintype "passive"))
      (node (ref "JP67") (pin "1") (pinfunction "1_1") (pintype "passive"))
    )
    (net (code "250") (name "/189_1440337657") (class "Default")
      (node (ref "JP1096") (pin "P$1") (pinfunction "1_P$1") (pintype "passive"))
      (node (ref "JP77") (pin "1") (pinfunction "1_1") (pintype "passive"))
    )
    (net (code "251") (name "/190_1440337657") (class "Default")
      (node (ref "JP1098") (pin "P$1") (pinfunction "1_P$1") (pintype "passive"))
      (node (ref "JP87") (pin "1") (pinfunction "1_1") (pintype "passive"))
    )
    (net (code "252") (name "/191_1440337657") (class "Default")
      (node (ref "JP1100") (pin "P$1") (pinfunction "1_P$1") (pintype "passive"))
      (node (ref "JP97") (pin "1") (pinfunction "1_1") (pintype "passive"))
    )
    (net (code "253") (name "/192_1440337657") (class "Default")
      (node (ref "JP107") (pin "1") (pinfunction "1_1") (pintype "passive"))
      (node (ref "JP1102") (pin "P$1") (pinfunction "1_P$1") (pintype "passive"))
    )
    (net (code "254") (name "/193_1440337657") (class "Default")
      (node (ref "JP1104") (pin "P$1") (pinfunction "1_P$1") (pintype "passive"))
      (node (ref "JP117") (pin "1") (pinfunction "1_1") (pintype "passive"))
    )
    (net (code "255") (name "/194_1440337657") (class "Default")
      (node (ref "JP1106") (pin "P$1") (pinfunction "1_P$1") (pintype "passive"))
      (node (ref "JP127") (pin "1") (pinfunction "1_1") (pintype "passive"))
    )
    (net (code "256") (name "/195_1440337657") (class "Default")
      (node (ref "JP1108") (pin "P$1") (pinfunction "1_P$1") (pintype "passive"))
      (node (ref "JP137") (pin "1") (pinfunction "1_1") (pintype "passive"))
    )
    (net (code "257") (name "/196_1440337657") (class "Default")
      (node (ref "JP1110") (pin "P$1") (pinfunction "1_P$1") (pintype "passive"))
      (node (ref "JP147") (pin "1") (pinfunction "1_1") (pintype "passive"))
    )
    (net (code "258") (name "/197_1440337657") (class "Default")
      (node (ref "JP1112") (pin "P$1") (pinfunction "1_P$1") (pintype "passive"))
      (node (ref "JP157") (pin "1") (pinfunction "1_1") (pintype "passive"))
    )
    (net (code "259") (name "/198_1440337657") (class "Default")
      (node (ref "JP1114") (pin "P$1") (pinfunction "1_P$1") (pintype "passive"))
      (node (ref "JP167") (pin "1") (pinfunction "1_1") (pintype "passive"))
    )
    (net (code "260") (name "/199_1440337657") (class "Default")
      (node (ref "JP1116") (pin "P$1") (pinfunction "1_P$1") (pintype "passive"))
      (node (ref "JP177") (pin "1") (pinfunction "1_1") (pintype "passive"))
    )
    (net (code "261") (name "/200_1440337657") (class "Default")
      (node (ref "JP1118") (pin "P$1") (pinfunction "1_P$1") (pintype "passive"))
      (node (ref "JP187") (pin "1") (pinfunction "1_1") (pintype "passive"))
    )
    (net (code "262") (name "/201_1440337657") (class "Default")
      (node (ref "JP1120") (pin "P$1") (pinfunction "1_P$1") (pintype "passive"))
      (node (ref "JP197") (pin "1") (pinfunction "1_1") (pintype "passive"))
    )
    (net (code "263") (name "/202_1440337657") (class "Default")
      (node (ref "JP1122") (pin "P$1") (pinfunction "1_P$1") (pintype "passive"))
      (node (ref "JP207") (pin "1") (pinfunction "1_1") (pintype "passive"))
    )
    (net (code "264") (name "/203_1440337657") (class "Default")
      (node (ref "JP1124") (pin "P$1") (pinfunction "1_P$1") (pintype "passive"))
      (node (ref "JP217") (pin "1") (pinfunction "1_1") (pintype "passive"))
    )
    (net (code "265") (name "/204_1440337657") (class "Default")
      (node (ref "JP1126") (pin "P$1") (pinfunction "1_P$1") (pintype "passive"))
      (node (ref "JP227") (pin "1") (pinfunction "1_1") (pintype "passive"))
    )
    (net (code "266") (name "/205_1440337657") (class "Default")
      (node (ref "JP1128") (pin "P$1") (pinfunction "1_P$1") (pintype "passive"))
      (node (ref "JP237") (pin "1") (pinfunction "1_1") (pintype "passive"))
    )
    (net (code "267") (name "/206_1440337657") (class "Default")
      (node (ref "JP1130") (pin "P$1") (pinfunction "1_P$1") (pintype "passive"))
      (node (ref "JP247") (pin "1") (pinfunction "1_1") (pintype "passive"))
    )
    (net (code "268") (name "/207_1440337657") (class "Default")
      (node (ref "JP1132") (pin "P$1") (pinfunction "1_P$1") (pintype "passive"))
      (node (ref "JP257") (pin "1") (pinfunction "1_1") (pintype "passive"))
    )
    (net (code "269") (name "/208_1440337657") (class "Default")
      (node (ref "JP1134") (pin "P$1") (pinfunction "1_P$1") (pintype "passive"))
      (node (ref "JP267") (pin "1") (pinfunction "1_1") (pintype "passive"))
    )
    (net (code "270") (name "/209_1440337657") (class "Default")
      (node (ref "JP1136") (pin "P$1") (pinfunction "1_P$1") (pintype "passive"))
      (node (ref "JP277") (pin "1") (pinfunction "1_1") (pintype "passive"))
    )
    (net (code "271") (name "/210_1440337657") (class "Default")
      (node (ref "JP1138") (pin "P$1") (pinfunction "1_P$1") (pintype "passive"))
      (node (ref "JP287") (pin "1") (pinfunction "1_1") (pintype "passive"))
    )
    (net (code "272") (name "/211_1440337657") (class "Default")
      (node (ref "JP4") (pin "1") (pinfunction "1_1") (pintype "passive"))
      (node (ref "JP902") (pin "P$1") (pinfunction "1_P$1") (pintype "passive"))
    )
    (net (code "273") (name "/212_1440337657") (class "Default")
      (node (ref "JP14") (pin "1") (pinfunction "1_1") (pintype "passive"))
      (node (ref "JP904") (pin "P$1") (pinfunction "1_P$1") (pintype "passive"))
    )
    (net (code "274") (name "/213_1440337657") (class "Default")
      (node (ref "JP24") (pin "1") (pinfunction "1_1") (pintype "passive"))
      (node (ref "JP906") (pin "P$1") (pinfunction "1_P$1") (pintype "passive"))
    )
    (net (code "275") (name "/214_1440337657") (class "Default")
      (node (ref "JP34") (pin "1") (pinfunction "1_1") (pintype "passive"))
      (node (ref "JP908") (pin "P$1") (pinfunction "1_P$1") (pintype "passive"))
    )
    (net (code "276") (name "/215_1440337657") (class "Default")
      (node (ref "JP44") (pin "1") (pinfunction "1_1") (pintype "passive"))
      (node (ref "JP910") (pin "P$1") (pinfunction "1_P$1") (pintype "passive"))
    )
    (net (code "277") (name "/216_1440337657") (class "Default")
      (node (ref "JP54") (pin "1") (pinfunction "1_1") (pintype "passive"))
      (node (ref "JP912") (pin "P$1") (pinfunction "1_P$1") (pintype "passive"))
    )
    (net (code "278") (name "/217_1440337657") (class "Default")
      (node (ref "JP64") (pin "1") (pinfunction "1_1") (pintype "passive"))
      (node (ref "JP914") (pin "P$1") (pinfunction "1_P$1") (pintype "passive"))
    )
    (net (code "279") (name "/218_1440337657") (class "Default")
      (node (ref "JP74") (pin "1") (pinfunction "1_1") (pintype "passive"))
      (node (ref "JP916") (pin "P$1") (pinfunction "1_P$1") (pintype "passive"))
    )
    (net (code "280") (name "/219_1440337657") (class "Default")
      (node (ref "JP84") (pin "1") (pinfunction "1_1") (pintype "passive"))
      (node (ref "JP918") (pin "P$1") (pinfunction "1_P$1") (pintype "passive"))
    )
    (net (code "281") (name "/220_1440337657") (class "Default")
      (node (ref "JP920") (pin "P$1") (pinfunction "1_P$1") (pintype "passive"))
      (node (ref "JP94") (pin "1") (pinfunction "1_1") (pintype "passive"))
    )
    (net (code "282") (name "/221_1440337657") (class "Default")
      (node (ref "JP104") (pin "1") (pinfunction "1_1") (pintype "passive"))
      (node (ref "JP922") (pin "P$1") (pinfunction "1_P$1") (pintype "passive"))
    )
    (net (code "283") (name "/222_1440337657") (class "Default")
      (node (ref "JP114") (pin "1") (pinfunction "1_1") (pintype "passive"))
      (node (ref "JP924") (pin "P$1") (pinfunction "1_P$1") (pintype "passive"))
    )
    (net (code "284") (name "/223_1440337657") (class "Default")
      (node (ref "JP124") (pin "1") (pinfunction "1_1") (pintype "passive"))
      (node (ref "JP926") (pin "P$1") (pinfunction "1_P$1") (pintype "passive"))
    )
    (net (code "285") (name "/224_1440337657") (class "Default")
      (node (ref "JP134") (pin "1") (pinfunction "1_1") (pintype "passive"))
      (node (ref "JP928") (pin "P$1") (pinfunction "1_P$1") (pintype "passive"))
    )
    (net (code "286") (name "/225_1440337657") (class "Default")
      (node (ref "JP144") (pin "1") (pinfunction "1_1") (pintype "passive"))
      (node (ref "JP930") (pin "P$1") (pinfunction "1_P$1") (pintype "passive"))
    )
    (net (code "287") (name "/226_1440337657") (class "Default")
      (node (ref "JP154") (pin "1") (pinfunction "1_1") (pintype "passive"))
      (node (ref "JP932") (pin "P$1") (pinfunction "1_P$1") (pintype "passive"))
    )
    (net (code "288") (name "/227_1440337657") (class "Default")
      (node (ref "JP164") (pin "1") (pinfunction "1_1") (pintype "passive"))
      (node (ref "JP934") (pin "P$1") (pinfunction "1_P$1") (pintype "passive"))
    )
    (net (code "289") (name "/228_1440337657") (class "Default")
      (node (ref "JP174") (pin "1") (pinfunction "1_1") (pintype "passive"))
      (node (ref "JP936") (pin "P$1") (pinfunction "1_P$1") (pintype "passive"))
    )
    (net (code "290") (name "/229_1440337657") (class "Default")
      (node (ref "JP184") (pin "1") (pinfunction "1_1") (pintype "passive"))
      (node (ref "JP938") (pin "P$1") (pinfunction "1_P$1") (pintype "passive"))
    )
    (net (code "291") (name "/230_1440337657") (class "Default")
      (node (ref "JP194") (pin "1") (pinfunction "1_1") (pintype "passive"))
      (node (ref "JP940") (pin "P$1") (pinfunction "1_P$1") (pintype "passive"))
    )
    (net (code "292") (name "/231_1440337657") (class "Default")
      (node (ref "JP204") (pin "1") (pinfunction "1_1") (pintype "passive"))
      (node (ref "JP942") (pin "P$1") (pinfunction "1_P$1") (pintype "passive"))
    )
    (net (code "293") (name "/232_1440337657") (class "Default")
      (node (ref "JP214") (pin "1") (pinfunction "1_1") (pintype "passive"))
      (node (ref "JP944") (pin "P$1") (pinfunction "1_P$1") (pintype "passive"))
    )
    (net (code "294") (name "/233_1440337657") (class "Default")
      (node (ref "JP224") (pin "1") (pinfunction "1_1") (pintype "passive"))
      (node (ref "JP946") (pin "P$1") (pinfunction "1_P$1") (pintype "passive"))
    )
    (net (code "295") (name "/234_1440337657") (class "Default")
      (node (ref "JP234") (pin "1") (pinfunction "1_1") (pintype "passive"))
      (node (ref "JP948") (pin "P$1") (pinfunction "1_P$1") (pintype "passive"))
    )
    (net (code "296") (name "/235_1440337657") (class "Default")
      (node (ref "JP244") (pin "1") (pinfunction "1_1") (pintype "passive"))
      (node (ref "JP950") (pin "P$1") (pinfunction "1_P$1") (pintype "passive"))
    )
    (net (code "297") (name "/236_1440337657") (class "Default")
      (node (ref "JP254") (pin "1") (pinfunction "1_1") (pintype "passive"))
      (node (ref "JP952") (pin "P$1") (pinfunction "1_P$1") (pintype "passive"))
    )
    (net (code "298") (name "/237_1440337657") (class "Default")
      (node (ref "JP264") (pin "1") (pinfunction "1_1") (pintype "passive"))
      (node (ref "JP954") (pin "P$1") (pinfunction "1_P$1") (pintype "passive"))
    )
    (net (code "299") (name "/238_1440337657") (class "Default")
      (node (ref "JP274") (pin "1") (pinfunction "1_1") (pintype "passive"))
      (node (ref "JP956") (pin "P$1") (pinfunction "1_P$1") (pintype "passive"))
    )
    (net (code "300") (name "/239_1440337657") (class "Default")
      (node (ref "JP284") (pin "1") (pinfunction "1_1") (pintype "passive"))
      (node (ref "JP958") (pin "P$1") (pinfunction "1_P$1") (pintype "passive"))
    )
  )
)
